# star-tracker-card.net
KiCad netlist of a schematic drawn in EAGLE
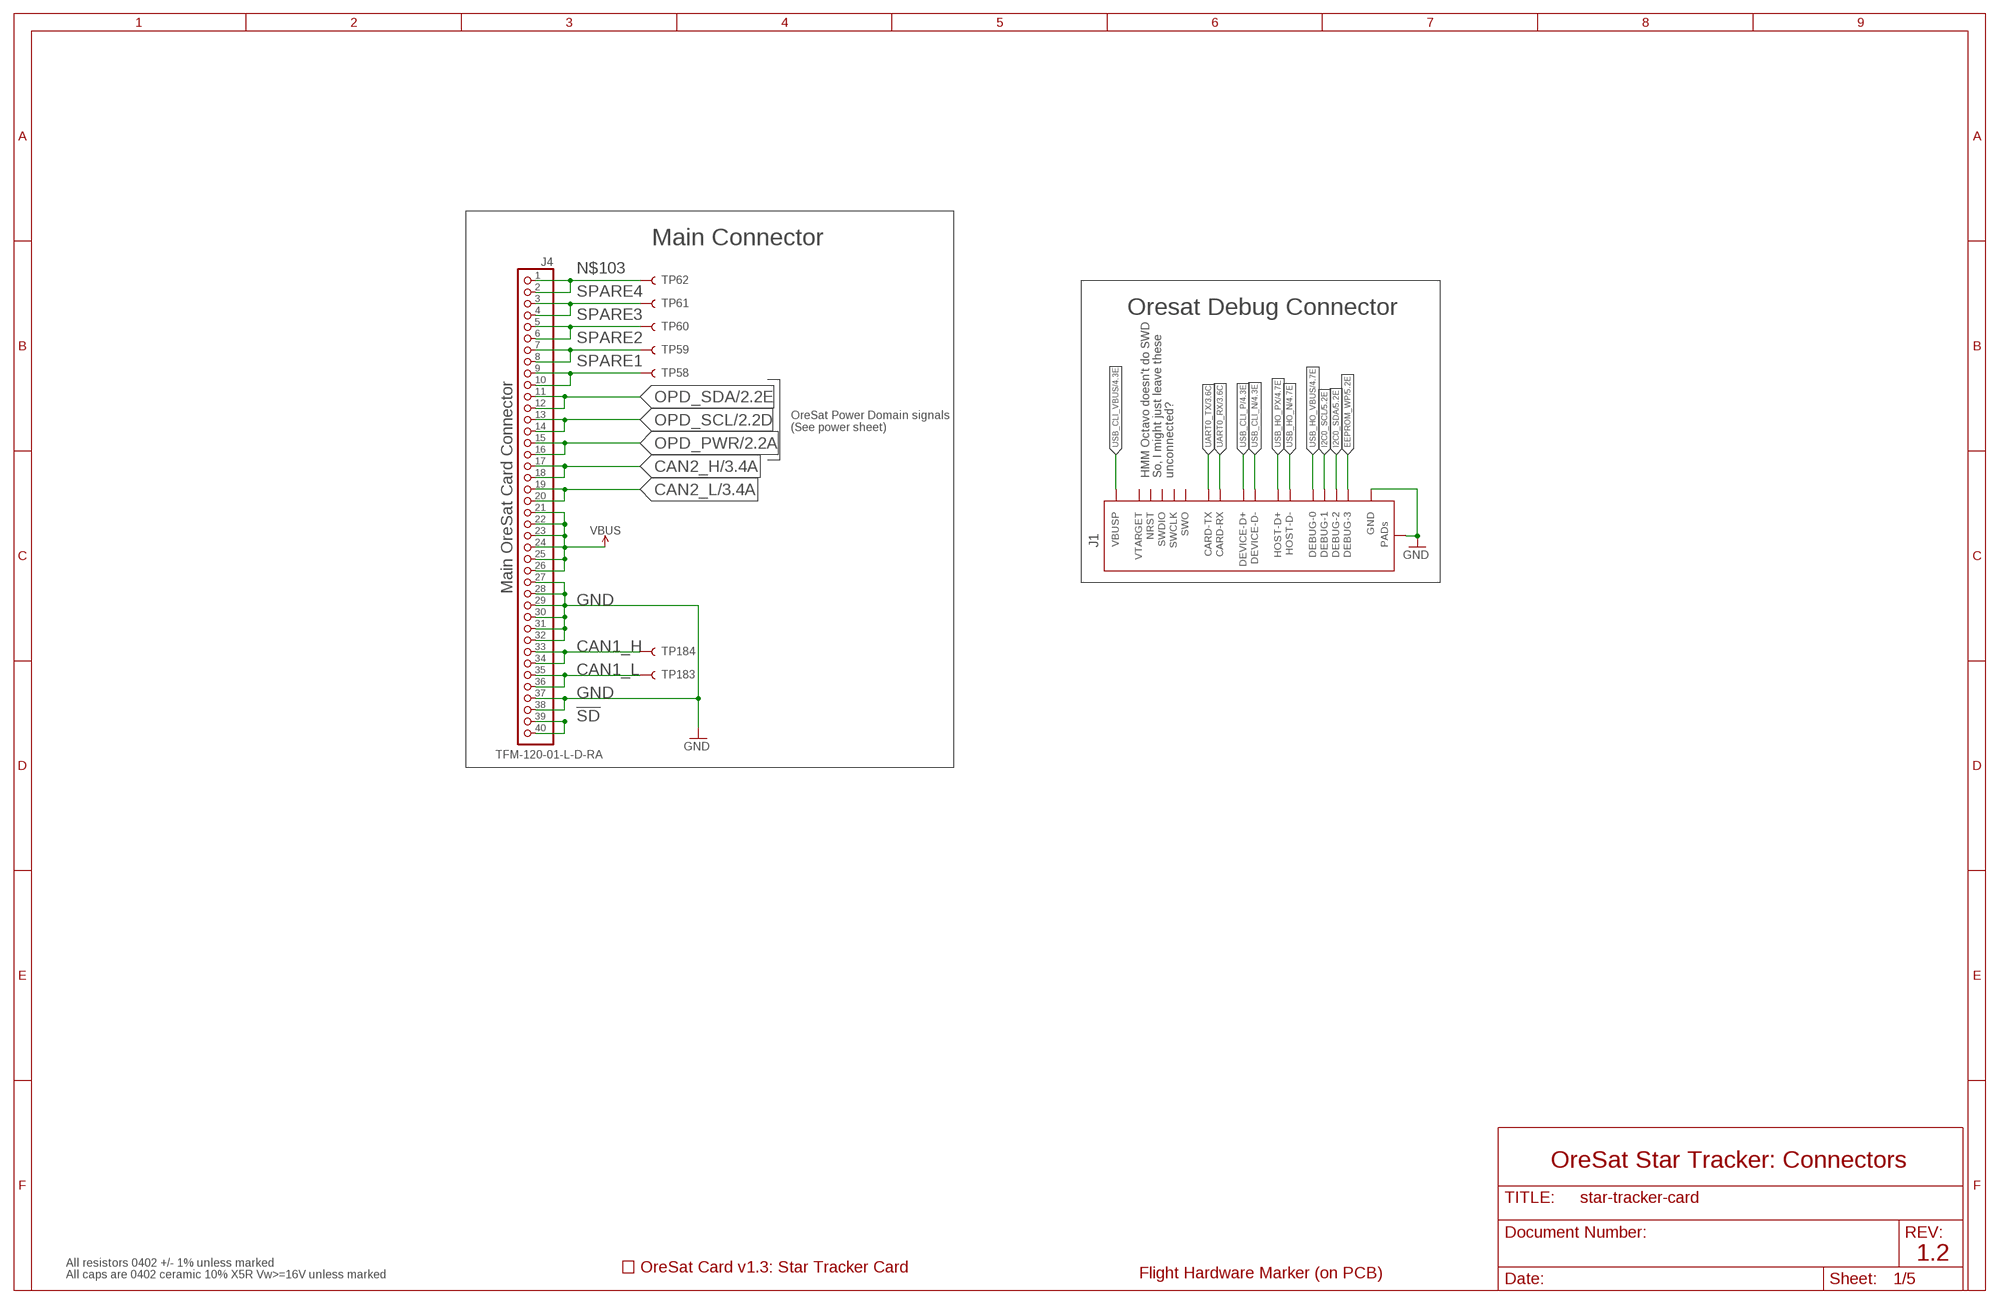
[diagram p0: schematic, sheet 1]
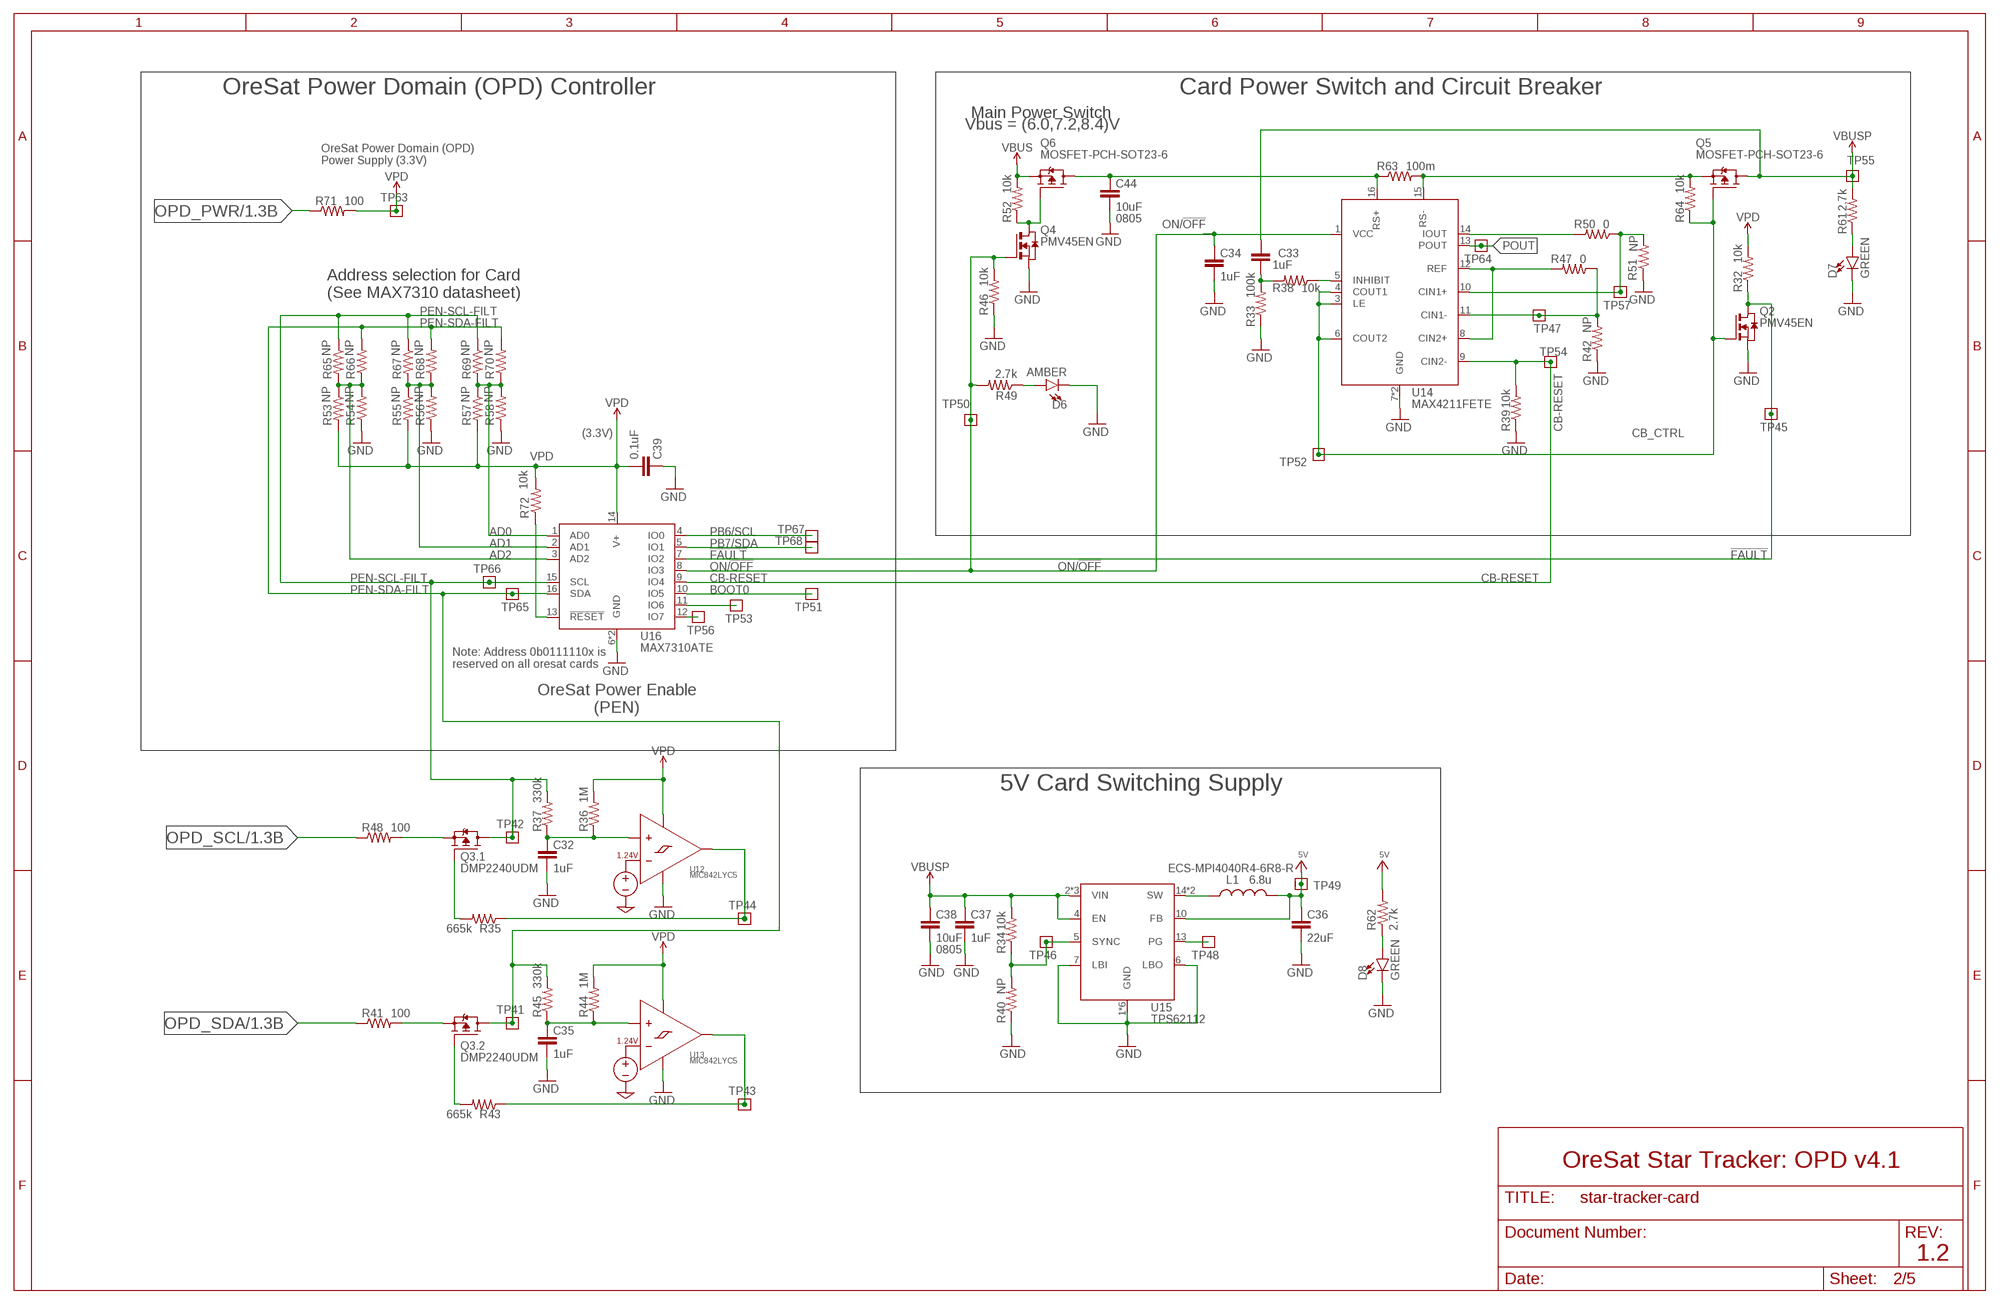
[diagram p1: schematic, sheet 2]
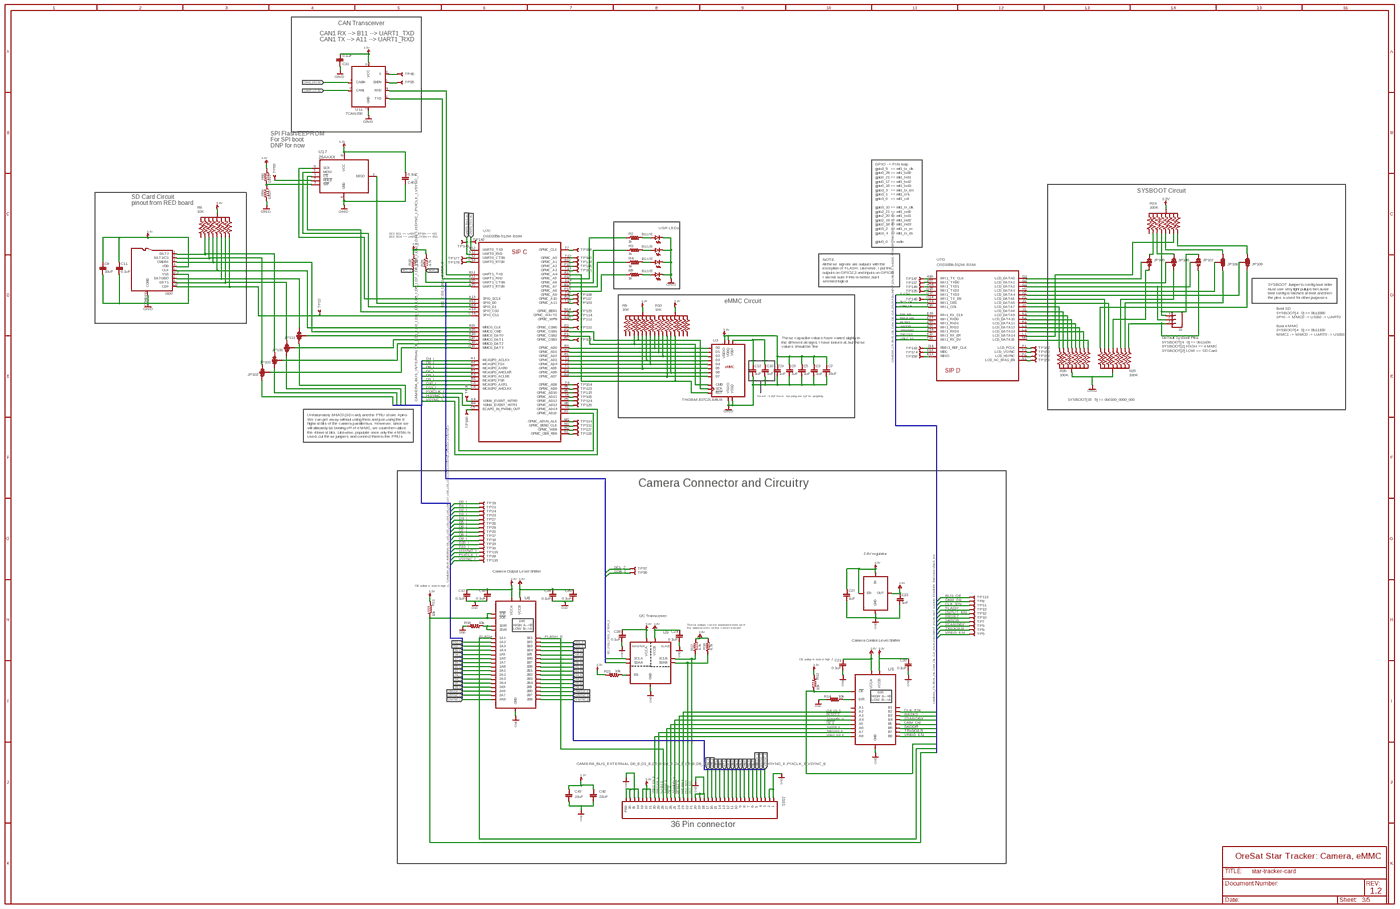
[diagram p2: schematic, sheet 3, overview]
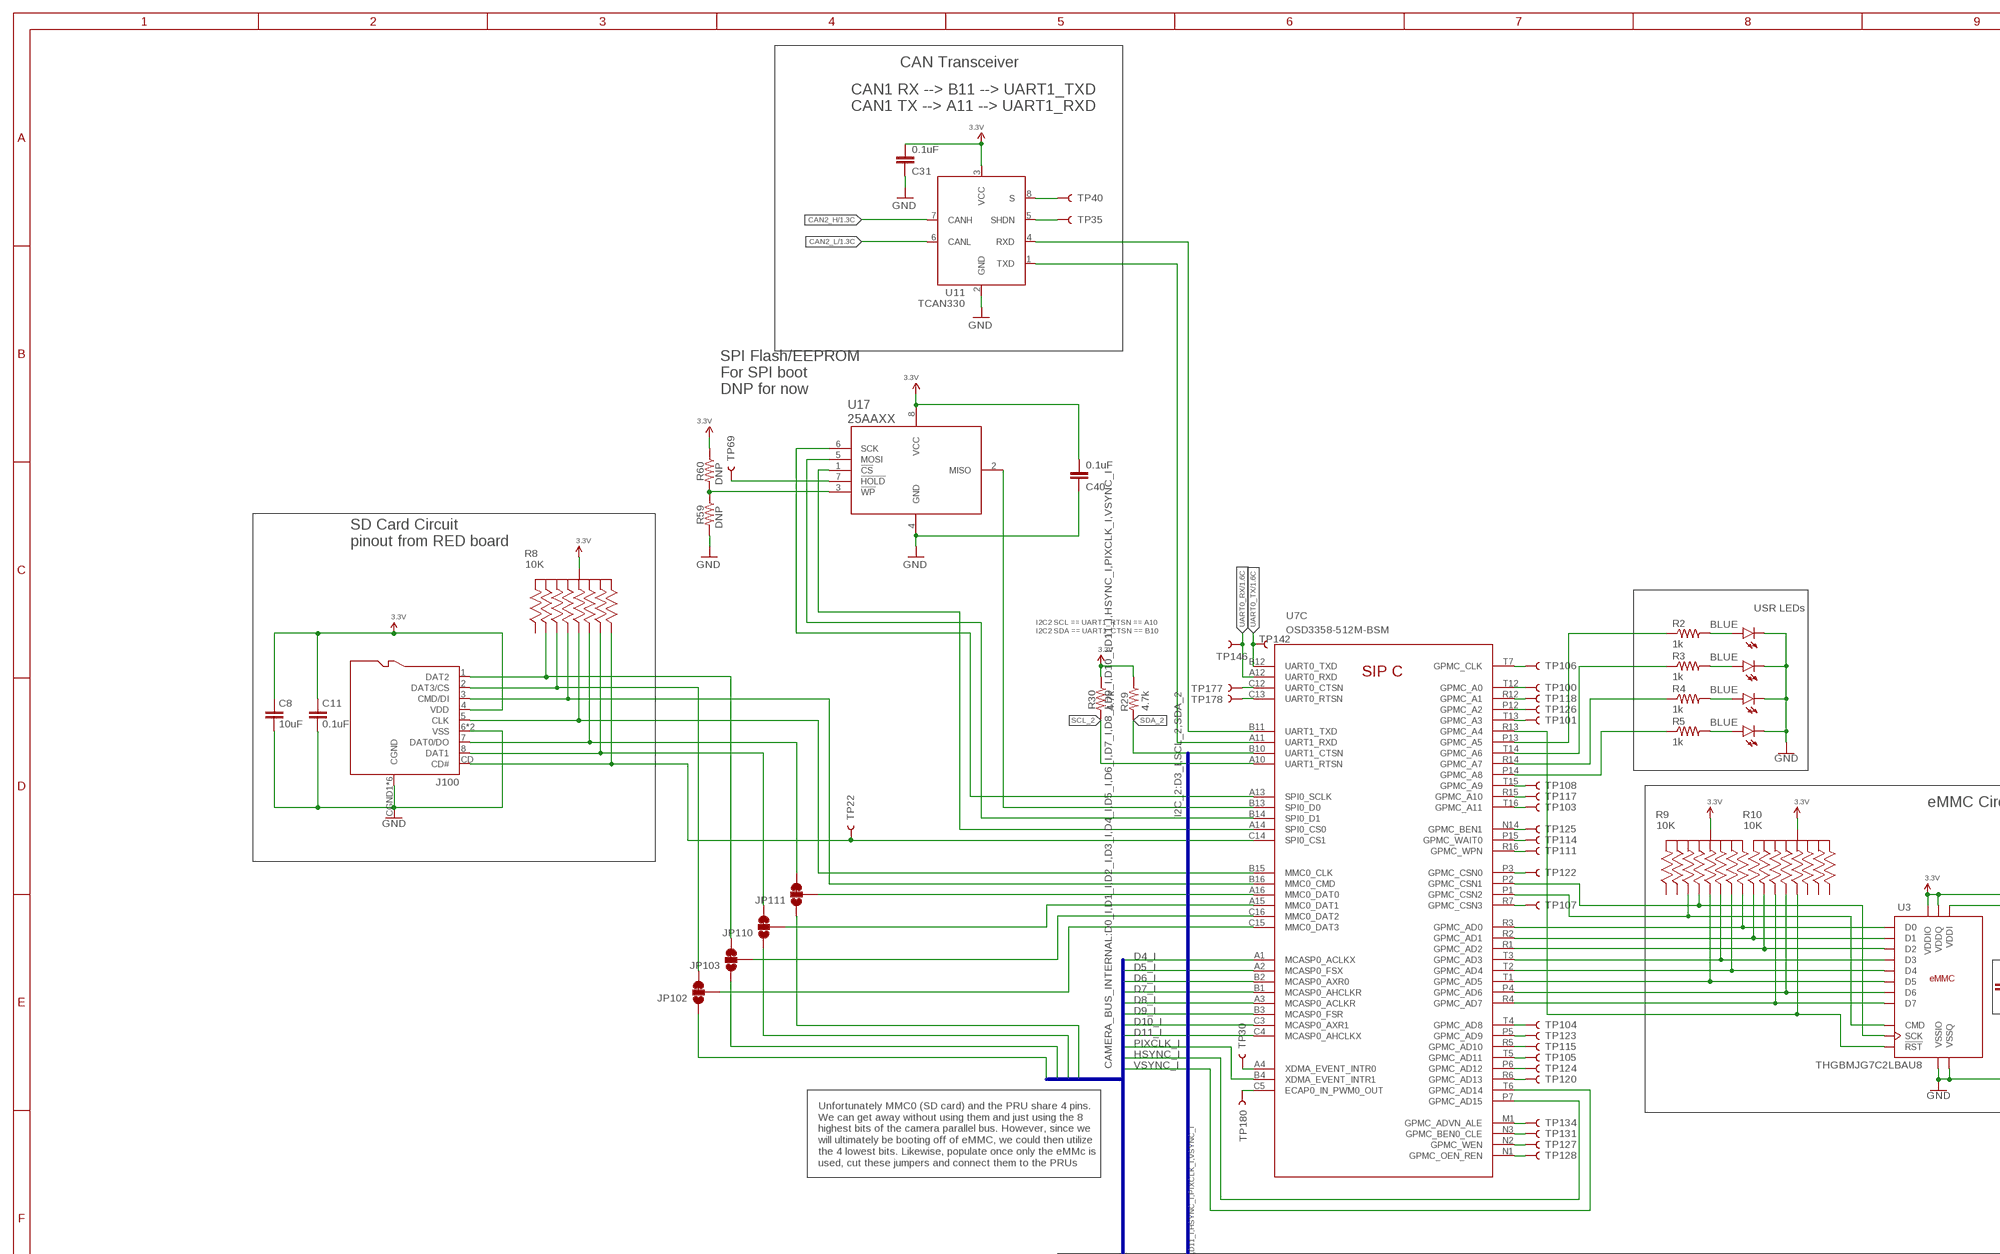
[diagram p3: schematic, sheet 3, part 1 of 4]
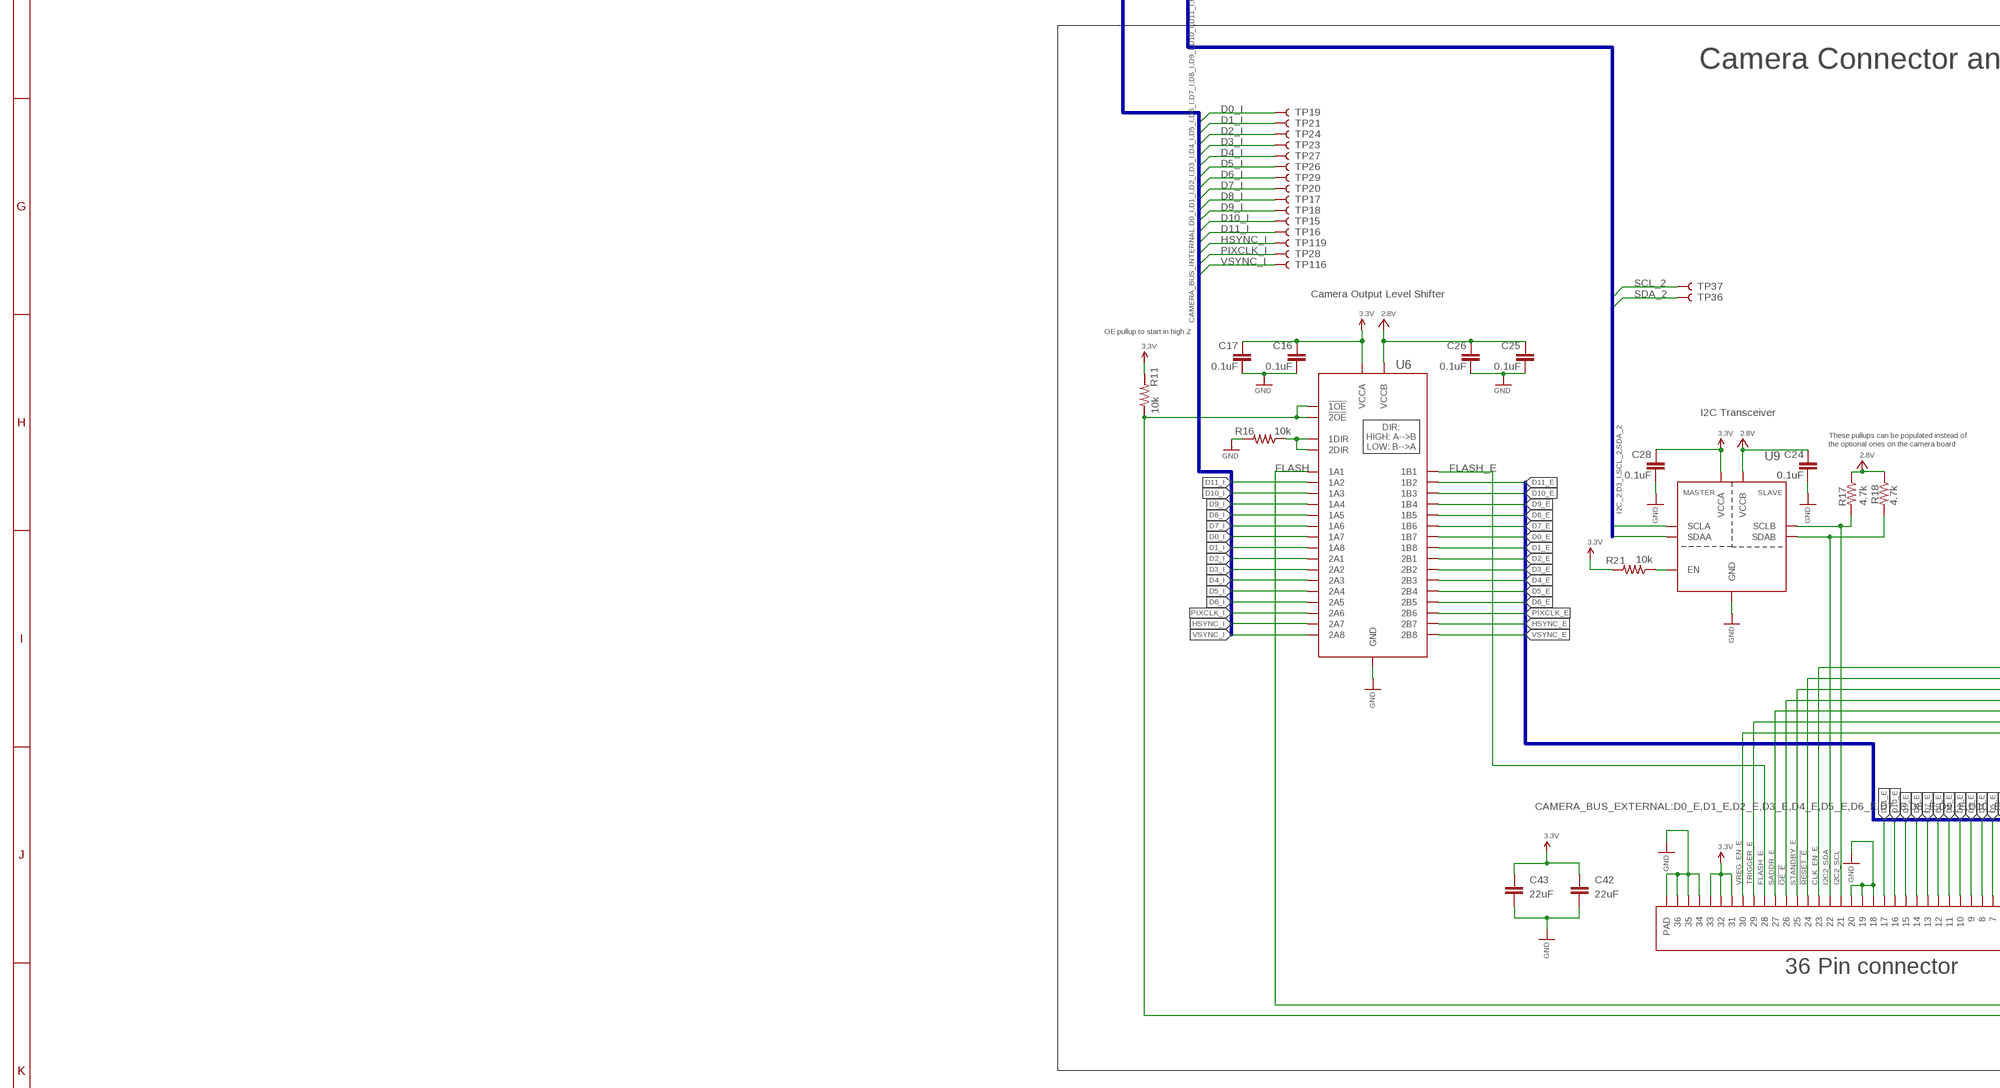
[diagram p4: schematic, sheet 3, part 2 of 4]
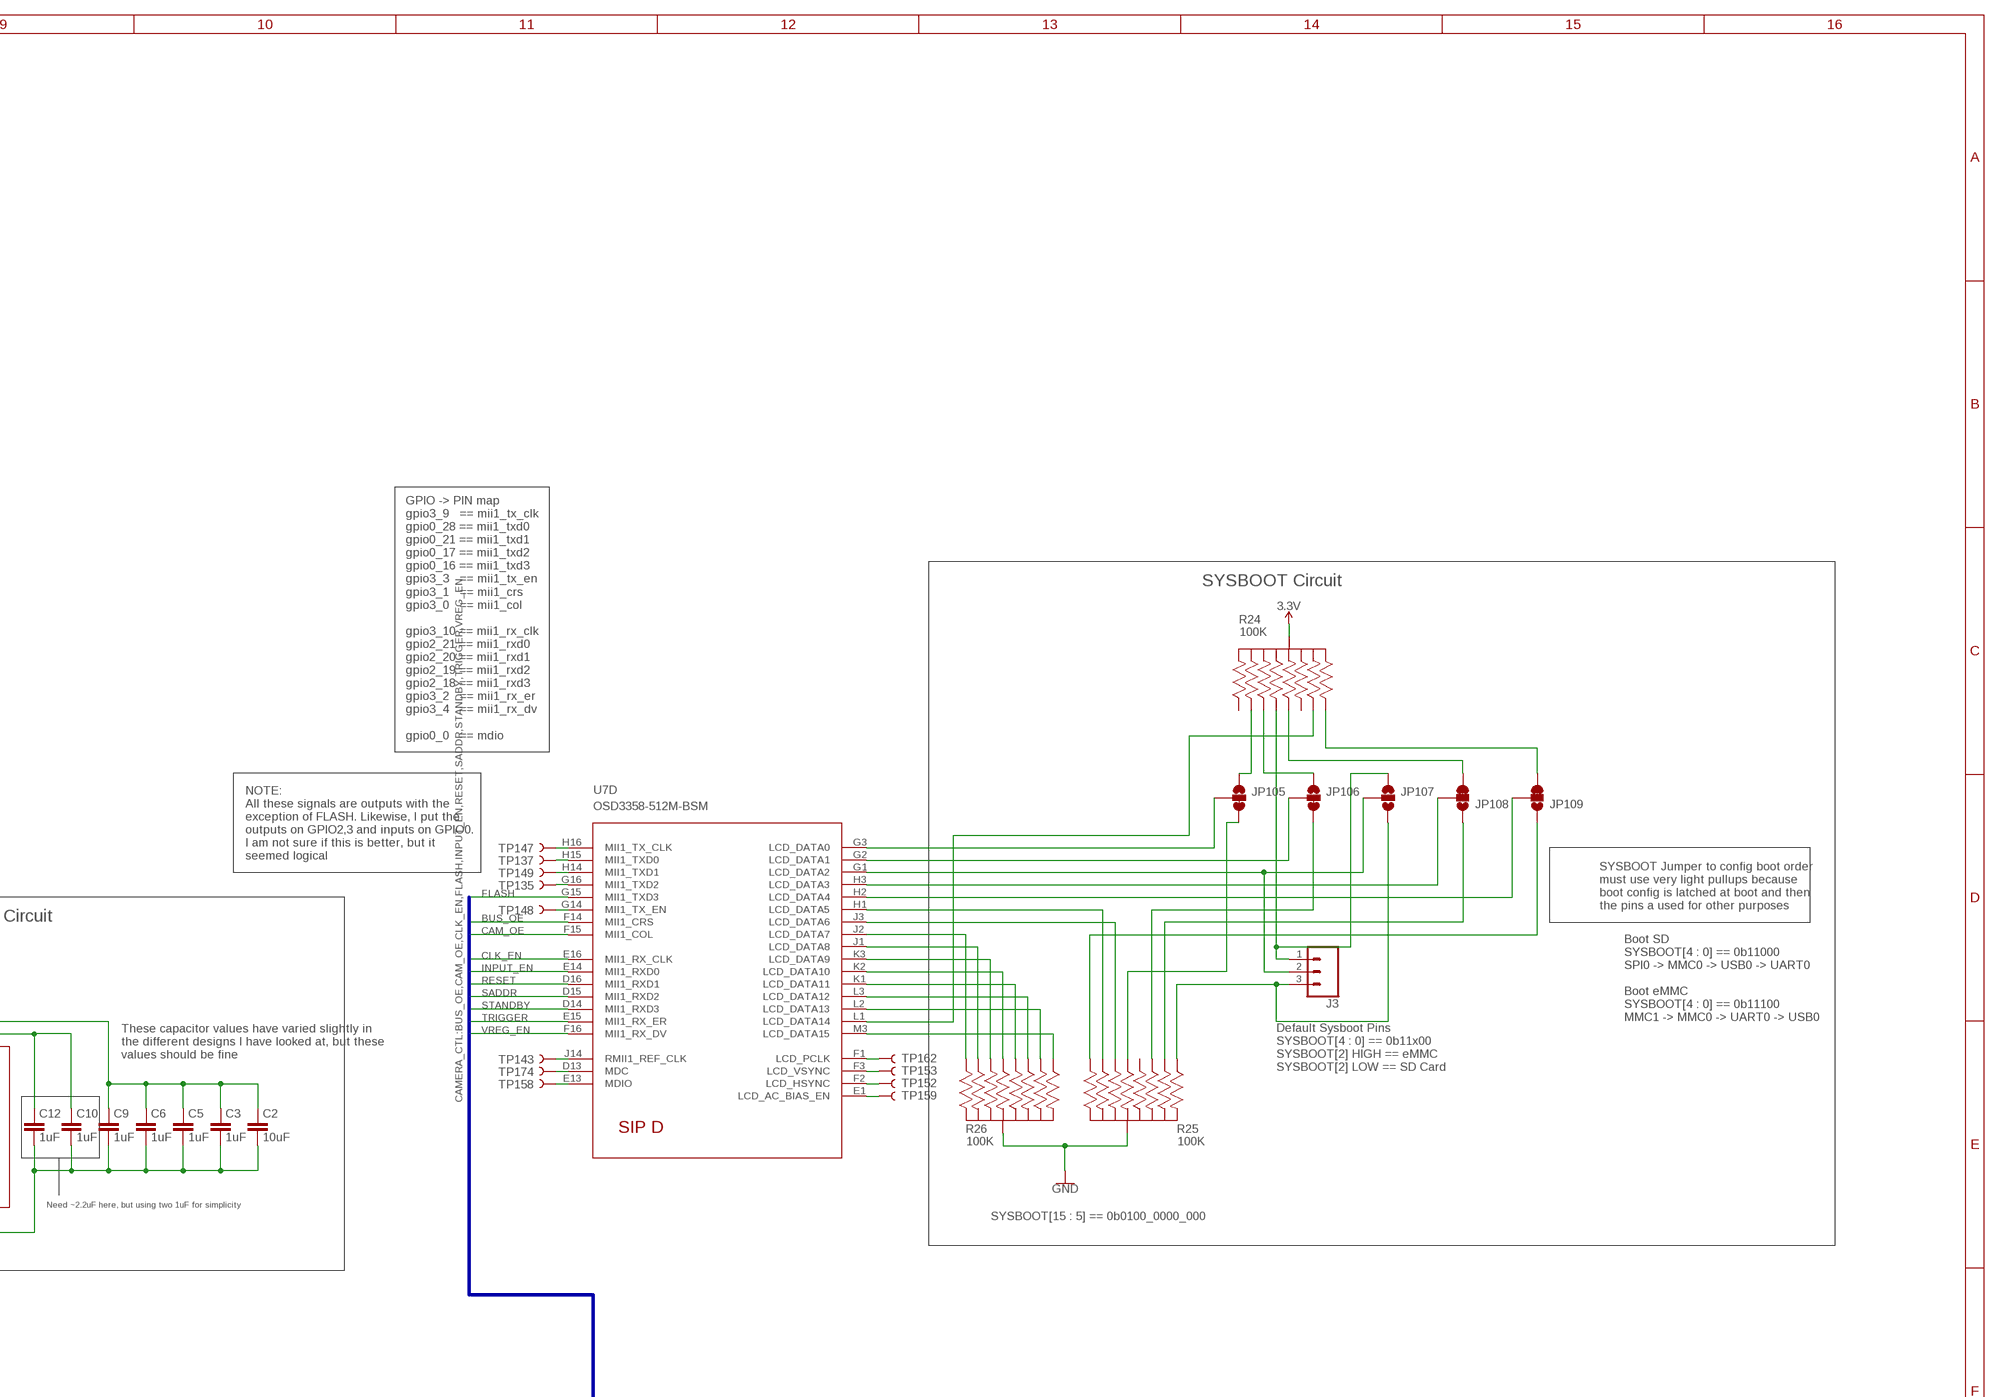
[diagram p5: schematic, sheet 3, part 3 of 4]
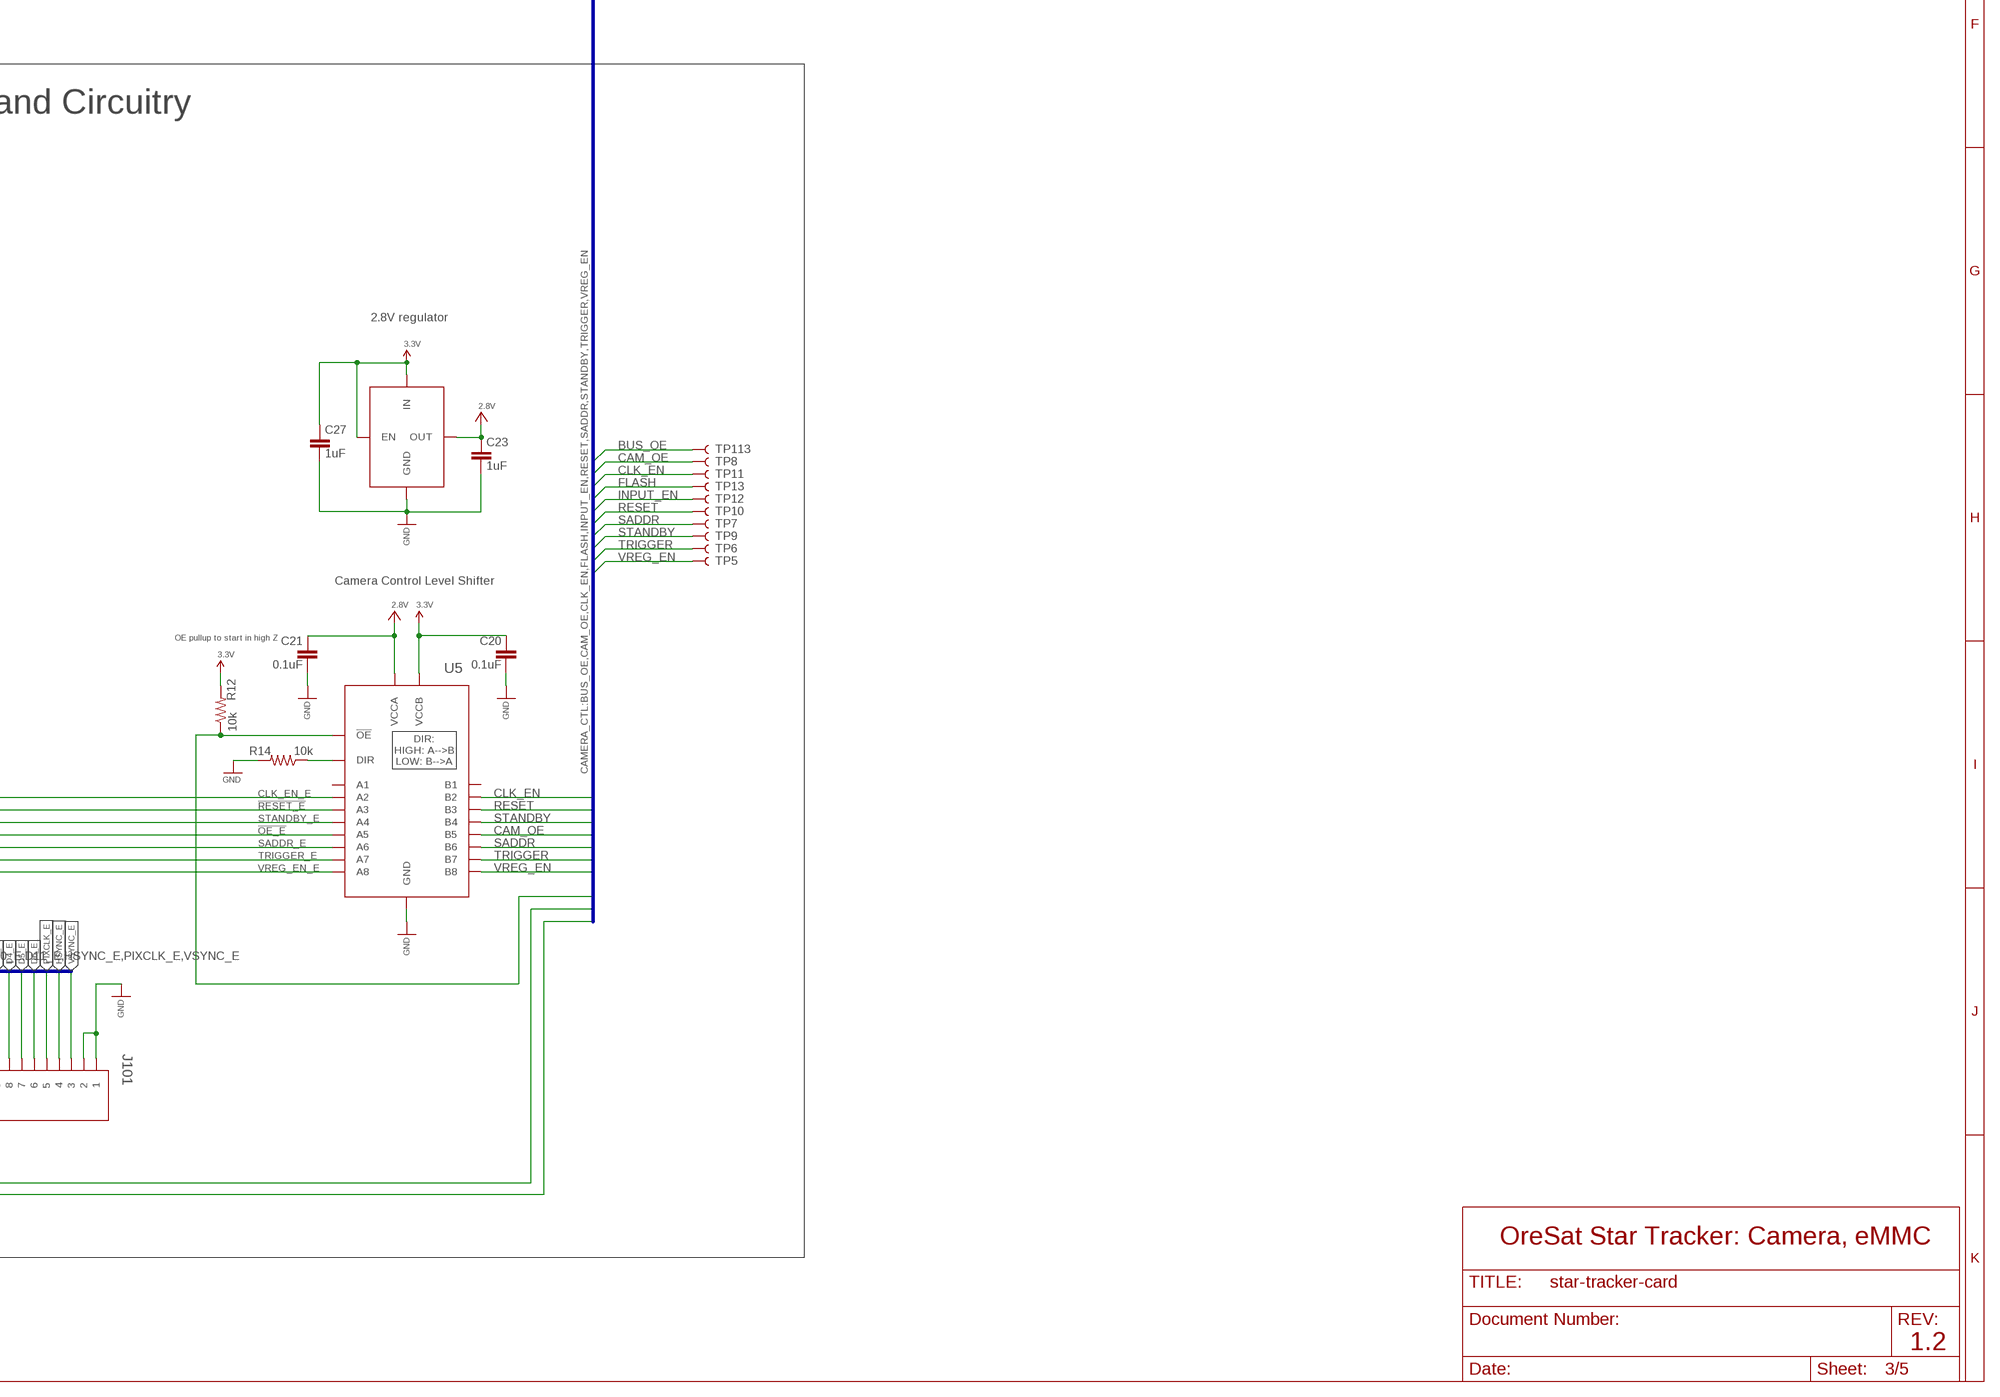
[diagram p6: schematic, sheet 3, part 4 of 4]
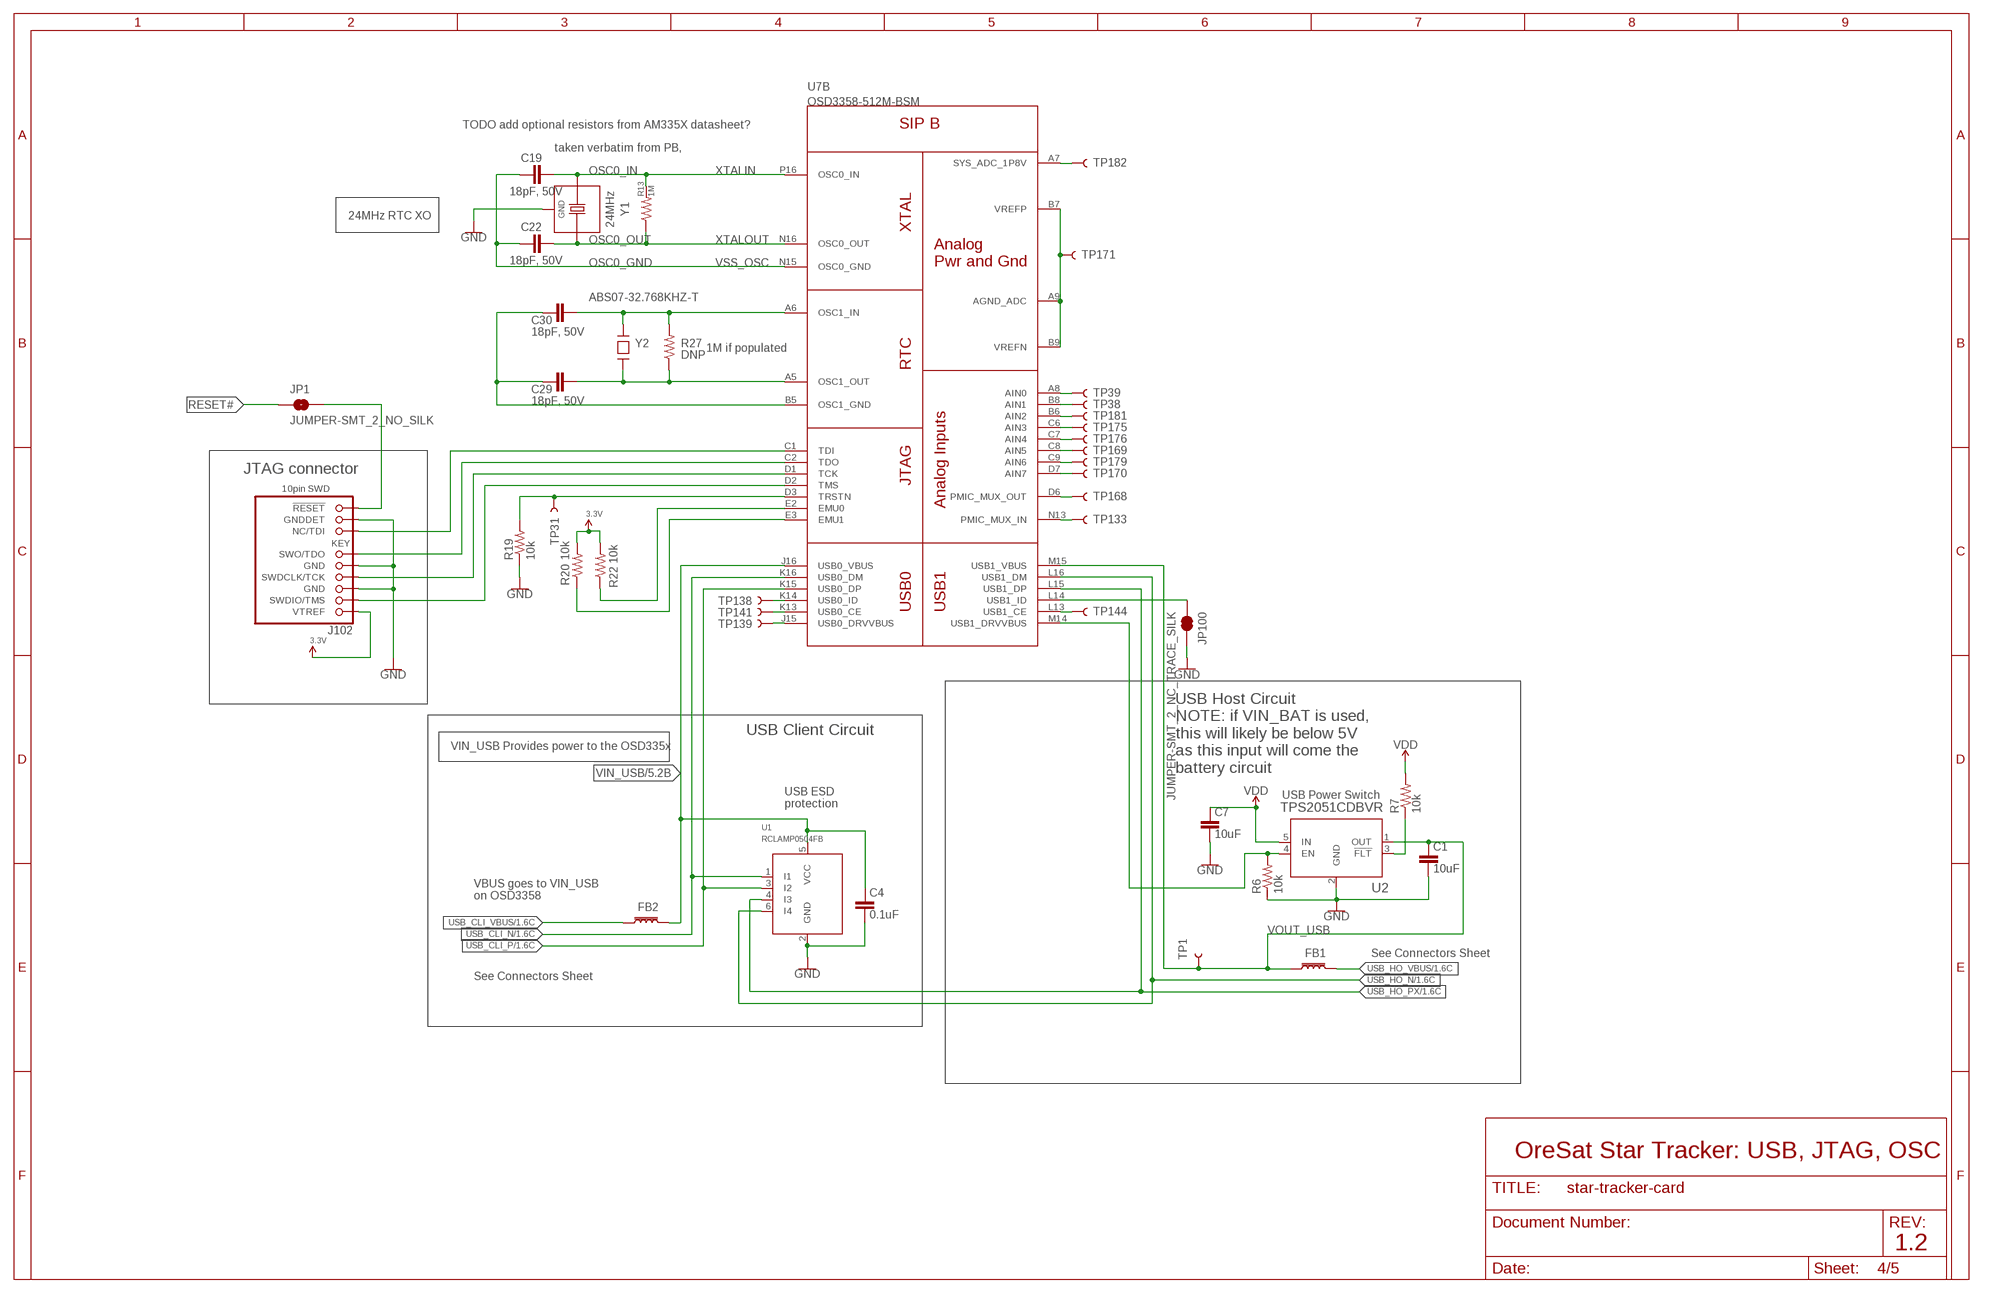
[diagram p7: schematic, sheet 4]
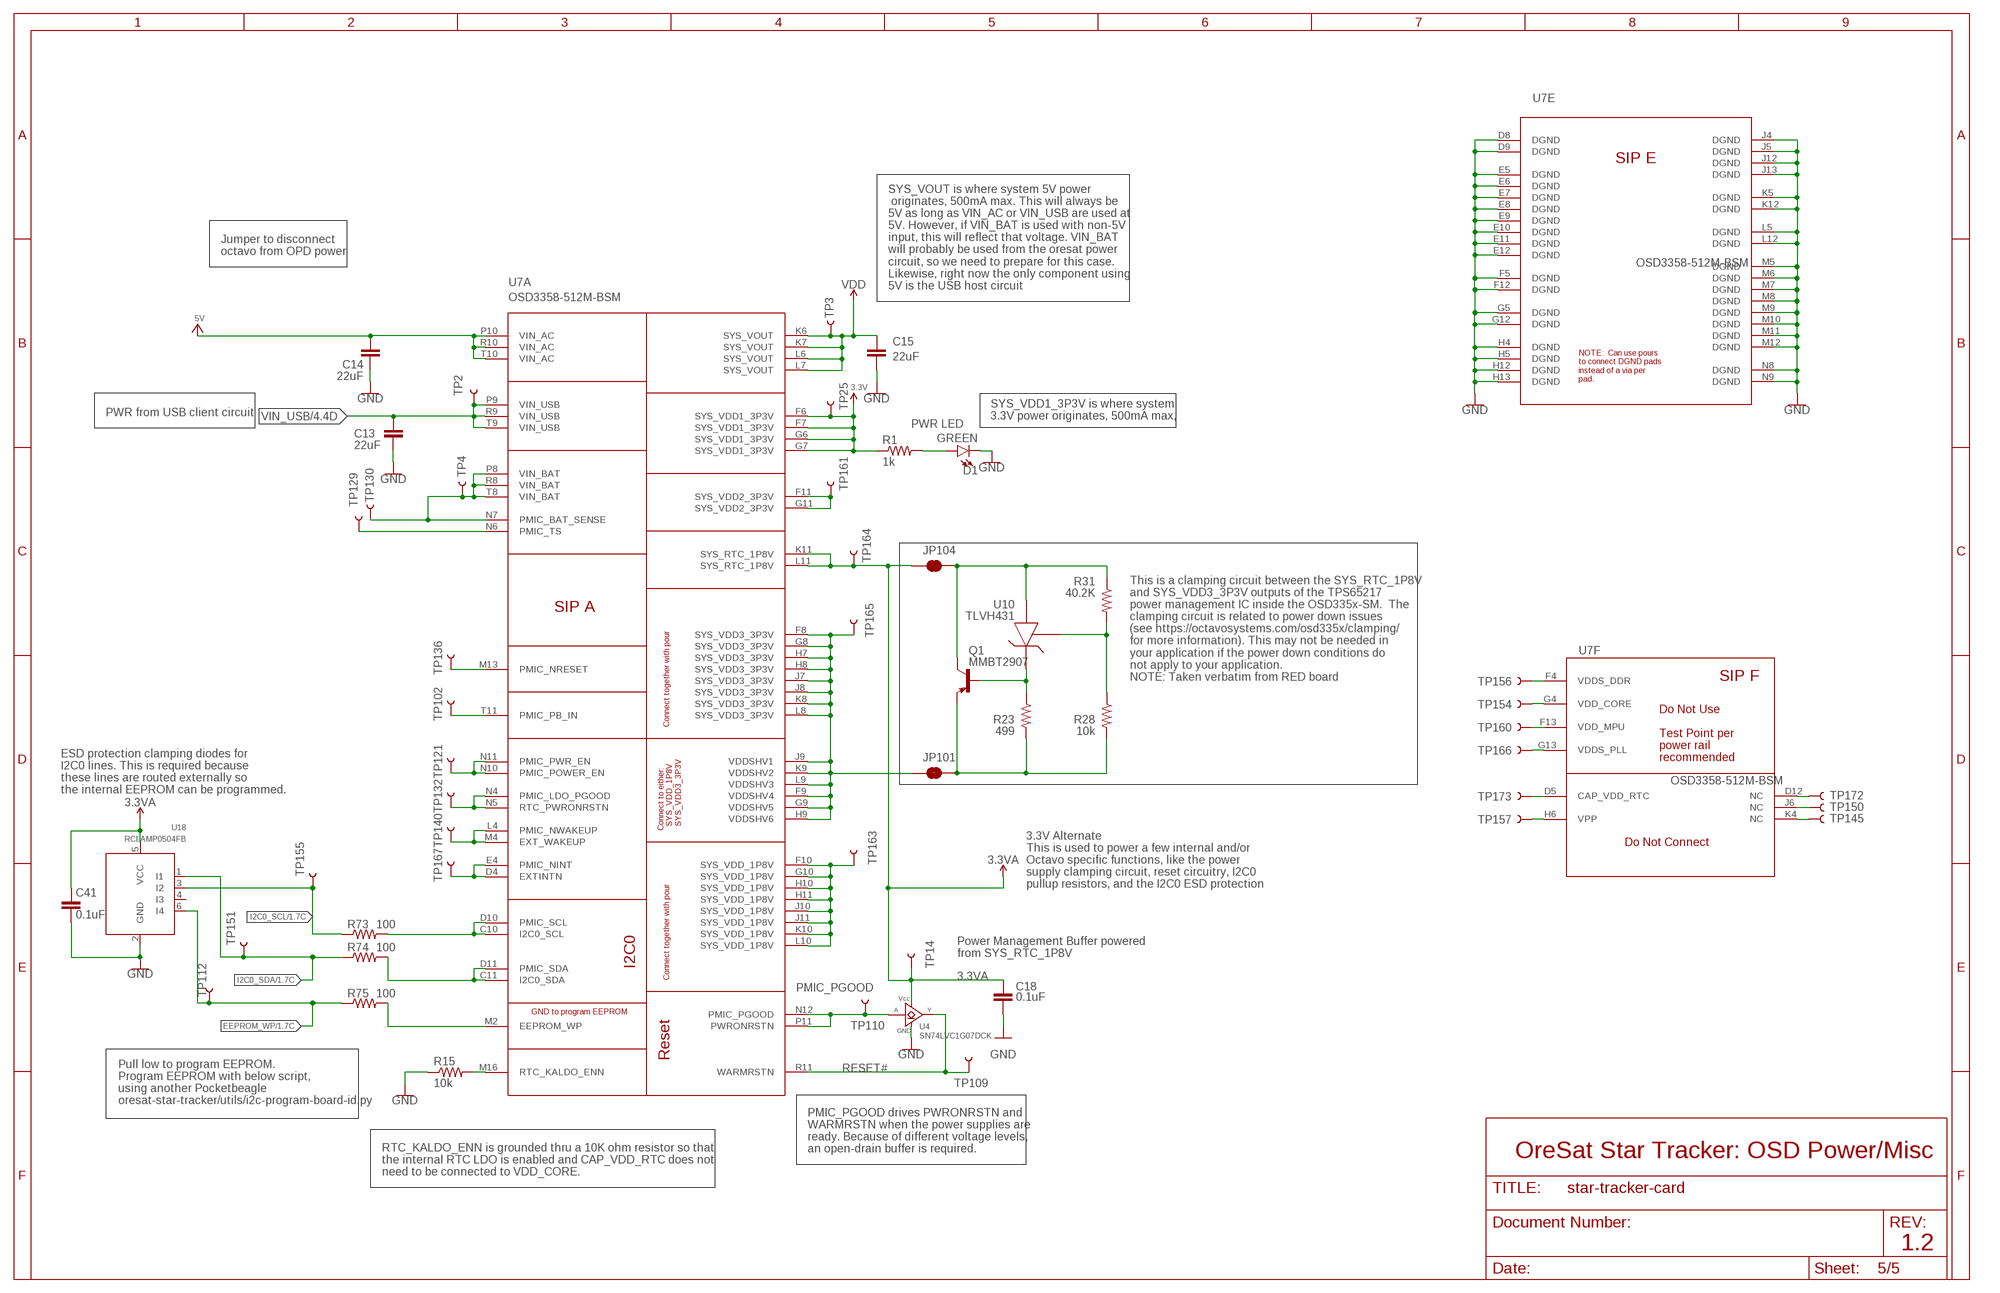
[diagram p8: schematic, sheet 5]

(export (version "E")
  (design (tool "Eeschema 10.0.6"))
  (components
    (comp (ref "C1")
      (value "10uF")
      (footprint "eagle-import:.0805-B")
      (libsource (lib "eagle-import") (part "C-EU0805-B"))
    )
    (comp (ref "C4")
      (value "0.1uF")
      (footprint "eagle-import:.0603-A")
      (libsource (lib "eagle-import") (part "C-EU0603-A"))
    )
    (comp (ref "C7")
      (value "10uF")
      (footprint "eagle-import:.0805-B")
      (libsource (lib "eagle-import") (part "C-EU0805-B"))
    )
    (comp (ref "C19")
      (value "18pF, 50V")
      (footprint "eagle-import:.0603-A")
      (libsource (lib "eagle-import") (part "C-EU0603-A"))
    )
    (comp (ref "C22")
      (value "18pF, 50V")
      (footprint "eagle-import:.0603-A")
      (libsource (lib "eagle-import") (part "C-EU0603-A"))
    )
    (comp (ref "C29")
      (value "18pF, 50V")
      (footprint "eagle-import:.0603-A")
      (libsource (lib "eagle-import") (part "C-EU0603-A"))
    )
    (comp (ref "C30")
      (value "18pF, 50V")
      (footprint "eagle-import:.0603-A")
      (libsource (lib "eagle-import") (part "C-EU0603-A"))
    )
    (comp (ref "FB1")
      (value "30Ω/1.8A")
      (footprint "eagle-import:0603")
      (fields (field (name "MPN") "BLM18KG300JH1D"))
      (libsource (lib "eagle-import") (part "FERRITE_BEAD-0603"))
    )
    (comp (ref "FB2")
      (value "30Ω/1.8A")
      (footprint "eagle-import:0603")
      (fields (field (name "MPN") "BLM18KG300JH1D"))
      (libsource (lib "eagle-import") (part "FERRITE_BEAD-0603"))
    )
    (comp (ref "J102")
      (value "FTSH-105-XX-X-DV-K")
      (footprint "eagle-import:CON10_2X5_DUK_FTSH")
      (libsource (lib "eagle-import") (part "FTSH-105-XX-X-DV-K"))
    )
    (comp (ref "JP1")
      (value "JUMPER-SMT_2_NO_SILK")
      (footprint "eagle-import:SMT-JUMPER_2_NO_SILK")
      (libsource (lib "eagle-import") (part "JUMPER-SMT_2_NO_SILK"))
    )
    (comp (ref "JP100")
      (value "JUMPER-SMT_2_NC_TRACE_SILK")
      (footprint "eagle-import:SMT-JUMPER_2_NC_TRACE_SILK")
      (libsource (lib "eagle-import") (part "JUMPER-SMT_2_NC_TRACE_SILK"))
    )
    (comp (ref "R6")
      (value "10k")
      (footprint "eagle-import:.0603-A")
      (libsource (lib "eagle-import") (part "R-US_0603-A"))
    )
    (comp (ref "R7")
      (value "10k")
      (footprint "eagle-import:.0603-A")
      (libsource (lib "eagle-import") (part "R-US_0603-A"))
    )
    (comp (ref "R13")
      (value "1M")
      (footprint "eagle-import:.0603-A")
      (libsource (lib "eagle-import") (part "R-US_0603-A"))
    )
    (comp (ref "R19")
      (value "10k")
      (footprint "eagle-import:.0603-A")
      (libsource (lib "eagle-import") (part "R-US_0603-A"))
    )
    (comp (ref "R20")
      (value "10k")
      (footprint "eagle-import:.0603-A")
      (libsource (lib "eagle-import") (part "R-US_0603-A"))
    )
    (comp (ref "R22")
      (value "10k")
      (footprint "eagle-import:.0603-A")
      (libsource (lib "eagle-import") (part "R-US_0603-A"))
    )
    (comp (ref "R27")
      (value "DNP")
      (footprint "eagle-import:.0603-A")
      (libsource (lib "eagle-import") (part "R-US_0603-A"))
    )
    (comp (ref "TP1")
      (value "TEST-POINT3X4")
      (footprint "eagle-import:PAD.03X.04")
      (libsource (lib "eagle-import") (part "TEST-POINT3X4"))
    )
    (comp (ref "TP31")
      (value "TEST-POINT3X4")
      (footprint "eagle-import:PAD.03X.04")
      (libsource (lib "eagle-import") (part "TEST-POINT3X4"))
    )
    (comp (ref "TP38")
      (value "TEST-POINT3X4")
      (footprint "eagle-import:PAD.03X.04")
      (libsource (lib "eagle-import") (part "TEST-POINT3X4"))
    )
    (comp (ref "TP39")
      (value "TEST-POINT3X4")
      (footprint "eagle-import:PAD.03X.04")
      (libsource (lib "eagle-import") (part "TEST-POINT3X4"))
    )
    (comp (ref "TP133")
      (value "TEST-POINT3X4")
      (footprint "eagle-import:PAD.03X.04")
      (libsource (lib "eagle-import") (part "TEST-POINT3X4"))
    )
    (comp (ref "TP138")
      (value "TEST-POINT3X4")
      (footprint "eagle-import:PAD.03X.04")
      (libsource (lib "eagle-import") (part "TEST-POINT3X4"))
    )
    (comp (ref "TP139")
      (value "TEST-POINT3X4")
      (footprint "eagle-import:PAD.03X.04")
      (libsource (lib "eagle-import") (part "TEST-POINT3X4"))
    )
    (comp (ref "TP141")
      (value "TEST-POINT3X4")
      (footprint "eagle-import:PAD.03X.04")
      (libsource (lib "eagle-import") (part "TEST-POINT3X4"))
    )
    (comp (ref "TP144")
      (value "TEST-POINT3X4")
      (footprint "eagle-import:PAD.03X.04")
      (libsource (lib "eagle-import") (part "TEST-POINT3X4"))
    )
    (comp (ref "TP168")
      (value "TEST-POINT3X4")
      (footprint "eagle-import:PAD.03X.04")
      (libsource (lib "eagle-import") (part "TEST-POINT3X4"))
    )
    (comp (ref "TP169")
      (value "TEST-POINT3X4")
      (footprint "eagle-import:PAD.03X.04")
      (libsource (lib "eagle-import") (part "TEST-POINT3X4"))
    )
    (comp (ref "TP170")
      (value "TEST-POINT3X4")
      (footprint "eagle-import:PAD.03X.04")
      (libsource (lib "eagle-import") (part "TEST-POINT3X4"))
    )
    (comp (ref "TP171")
      (value "TEST-POINT3X4")
      (footprint "eagle-import:PAD.03X.04")
      (libsource (lib "eagle-import") (part "TEST-POINT3X4"))
    )
    (comp (ref "TP175")
      (value "TEST-POINT3X4")
      (footprint "eagle-import:PAD.03X.04")
      (libsource (lib "eagle-import") (part "TEST-POINT3X4"))
    )
    (comp (ref "TP176")
      (value "TEST-POINT3X4")
      (footprint "eagle-import:PAD.03X.04")
      (libsource (lib "eagle-import") (part "TEST-POINT3X4"))
    )
    (comp (ref "TP179")
      (value "TEST-POINT3X4")
      (footprint "eagle-import:PAD.03X.04")
      (libsource (lib "eagle-import") (part "TEST-POINT3X4"))
    )
    (comp (ref "TP181")
      (value "TEST-POINT3X4")
      (footprint "eagle-import:PAD.03X.04")
      (libsource (lib "eagle-import") (part "TEST-POINT3X4"))
    )
    (comp (ref "TP182")
      (value "TEST-POINT3X4")
      (footprint "eagle-import:PAD.03X.04")
      (libsource (lib "eagle-import") (part "TEST-POINT3X4"))
    )
    (comp (ref "U1")
      (value "RCLAMP0504FB")
      (footprint "eagle-import:SC70-6")
      (fields (field (name "MPN") "RCLAMP0504FBTCT"))
      (libsource (lib "eagle-import") (part "RCLAMP0504FB"))
    )
    (comp (ref "U2")
      (value "TPS2051CDBVR")
      (footprint "eagle-import:DBV5")
      (fields (field (name "MFR") "Texas Instruments"))
      (libsource (lib "eagle-import") (part "TPS2051CDBVR"))
    )
    (comp (ref "U7")
      (value "OSD3358-512M-BSM")
      (footprint "eagle-import:OSD335X-BGA-256")
      (fields (field (name "MFR") "Octavo Systems"))
      (libsource (lib "eagle-import") (part "OSD3358-512M-BSM"))
    )
    (comp (ref "Y1")
      (value "24MHz")
      (footprint "eagle-import:5X3.2-4SMD")
      (fields (field (name "MPN") "ECS-240-12-30BQ-AEN-TR"))
      (libsource (lib "eagle-import") (part "ECS-240-12-30BQ-AEN-TR"))
    )
    (comp (ref "Y2")
      (value "ABS07-32.768KHZ-T")
      (footprint "eagle-import:CRYSTAL_3.2X1.5")
      (libsource (lib "eagle-import") (part "ABS07-32.768KHZ-T"))
    )
    (comp (ref "C13")
      (value "22uF")
      (footprint "eagle-import:C1210")
      (libsource (lib "eagle-import") (part "C-EUC1210"))
    )
    (comp (ref "C14")
      (value "22uF")
      (footprint "eagle-import:C1210")
      (libsource (lib "eagle-import") (part "C-EUC1210"))
    )
    (comp (ref "C15")
      (value "22uF")
      (footprint "eagle-import:C1210")
      (libsource (lib "eagle-import") (part "C-EUC1210"))
    )
    (comp (ref "C18")
      (value "0.1uF")
      (footprint "eagle-import:.0603-A")
      (libsource (lib "eagle-import") (part "C-EU0603-A"))
    )
    (comp (ref "C41")
      (value "0.1uF")
      (footprint "eagle-import:.0603-A")
      (libsource (lib "eagle-import") (part "C-EU0603-A"))
    )
    (comp (ref "D1")
      (value "GREEN")
      (footprint "eagle-import:LED-0603")
      (libsource (lib "eagle-import") (part "LED-GREEN0603"))
    )
    (comp (ref "JP101")
      (value "JUMPER-SMT_2_NC_TRACE_SILK")
      (footprint "eagle-import:SMT-JUMPER_2_NC_TRACE_SILK")
      (libsource (lib "eagle-import") (part "JUMPER-SMT_2_NC_TRACE_SILK"))
    )
    (comp (ref "JP104")
      (value "JUMPER-SMT_2_NC_TRACE_SILK")
      (footprint "eagle-import:SMT-JUMPER_2_NC_TRACE_SILK")
      (libsource (lib "eagle-import") (part "JUMPER-SMT_2_NC_TRACE_SILK"))
    )
    (comp (ref "Q1")
      (value "MMBT2907")
      (footprint "eagle-import:SOT23-BEC")
      (fields (field (name "MPN") "MMBT2907A-7-F"))
      (libsource (lib "eagle-import") (part "MMBT2907SMD"))
    )
    (comp (ref "R1")
      (value "1k")
      (footprint "eagle-import:.0603-A")
      (libsource (lib "eagle-import") (part "R-US_0603-A"))
    )
    (comp (ref "R15")
      (value "10k")
      (footprint "eagle-import:.0603-A")
      (libsource (lib "eagle-import") (part "R-US_0603-A"))
    )
    (comp (ref "R23")
      (value "499")
      (footprint "eagle-import:.0603-A")
      (libsource (lib "eagle-import") (part "R-US_0603-A"))
    )
    (comp (ref "R28")
      (value "10k")
      (footprint "eagle-import:.0603-A")
      (libsource (lib "eagle-import") (part "R-US_0603-A"))
    )
    (comp (ref "R31")
      (value "40.2K")
      (footprint "eagle-import:.0603-A")
      (libsource (lib "eagle-import") (part "R-US_0603-A"))
    )
    (comp (ref "R73")
      (value "100")
      (footprint "eagle-import:.0603-A")
      (libsource (lib "eagle-import") (part "R-US_0603-A"))
    )
    (comp (ref "R74")
      (value "100")
      (footprint "eagle-import:.0603-A")
      (libsource (lib "eagle-import") (part "R-US_0603-A"))
    )
    (comp (ref "R75")
      (value "100")
      (footprint "eagle-import:.0603-A")
      (libsource (lib "eagle-import") (part "R-US_0603-A"))
    )
    (comp (ref "TP2")
      (value "TEST-POINT3X4")
      (footprint "eagle-import:PAD.03X.04")
      (libsource (lib "eagle-import") (part "TEST-POINT3X4"))
    )
    (comp (ref "TP3")
      (value "TEST-POINT3X4")
      (footprint "eagle-import:PAD.03X.04")
      (libsource (lib "eagle-import") (part "TEST-POINT3X4"))
    )
    (comp (ref "TP4")
      (value "TEST-POINT3X4")
      (footprint "eagle-import:PAD.03X.04")
      (libsource (lib "eagle-import") (part "TEST-POINT3X4"))
    )
    (comp (ref "TP14")
      (value "TEST-POINT3X4")
      (footprint "eagle-import:PAD.03X.04")
      (libsource (lib "eagle-import") (part "TEST-POINT3X4"))
    )
    (comp (ref "TP25")
      (value "TEST-POINT3X4")
      (footprint "eagle-import:PAD.03X.04")
      (libsource (lib "eagle-import") (part "TEST-POINT3X4"))
    )
    (comp (ref "TP102")
      (value "TEST-POINT3X4")
      (footprint "eagle-import:PAD.03X.04")
      (libsource (lib "eagle-import") (part "TEST-POINT3X4"))
    )
    (comp (ref "TP109")
      (value "TEST-POINT3X4")
      (footprint "eagle-import:PAD.03X.04")
      (libsource (lib "eagle-import") (part "TEST-POINT3X4"))
    )
    (comp (ref "TP110")
      (value "TEST-POINT3X4")
      (footprint "eagle-import:PAD.03X.04")
      (libsource (lib "eagle-import") (part "TEST-POINT3X4"))
    )
    (comp (ref "TP112")
      (value "TEST-POINT3X4")
      (footprint "eagle-import:PAD.03X.04")
      (libsource (lib "eagle-import") (part "TEST-POINT3X4"))
    )
    (comp (ref "TP121")
      (value "TEST-POINT3X4")
      (footprint "eagle-import:PAD.03X.04")
      (libsource (lib "eagle-import") (part "TEST-POINT3X4"))
    )
    (comp (ref "TP129")
      (value "TEST-POINT3X4")
      (footprint "eagle-import:PAD.03X.04")
      (libsource (lib "eagle-import") (part "TEST-POINT3X4"))
    )
    (comp (ref "TP130")
      (value "TEST-POINT3X4")
      (footprint "eagle-import:PAD.03X.04")
      (libsource (lib "eagle-import") (part "TEST-POINT3X4"))
    )
    (comp (ref "TP132")
      (value "TEST-POINT3X4")
      (footprint "eagle-import:PAD.03X.04")
      (libsource (lib "eagle-import") (part "TEST-POINT3X4"))
    )
    (comp (ref "TP136")
      (value "TEST-POINT3X4")
      (footprint "eagle-import:PAD.03X.04")
      (libsource (lib "eagle-import") (part "TEST-POINT3X4"))
    )
    (comp (ref "TP140")
      (value "TEST-POINT3X4")
      (footprint "eagle-import:PAD.03X.04")
      (libsource (lib "eagle-import") (part "TEST-POINT3X4"))
    )
    (comp (ref "TP145")
      (value "TEST-POINT3X4")
      (footprint "eagle-import:PAD.03X.04")
      (libsource (lib "eagle-import") (part "TEST-POINT3X4"))
    )
    (comp (ref "TP150")
      (value "TEST-POINT3X4")
      (footprint "eagle-import:PAD.03X.04")
      (libsource (lib "eagle-import") (part "TEST-POINT3X4"))
    )
    (comp (ref "TP151")
      (value "TEST-POINT3X4")
      (footprint "eagle-import:PAD.03X.04")
      (libsource (lib "eagle-import") (part "TEST-POINT3X4"))
    )
    (comp (ref "TP154")
      (value "TEST-POINT3X4")
      (footprint "eagle-import:PAD.03X.04")
      (libsource (lib "eagle-import") (part "TEST-POINT3X4"))
    )
    (comp (ref "TP155")
      (value "TEST-POINT3X4")
      (footprint "eagle-import:PAD.03X.04")
      (libsource (lib "eagle-import") (part "TEST-POINT3X4"))
    )
    (comp (ref "TP156")
      (value "TEST-POINT3X4")
      (footprint "eagle-import:PAD.03X.04")
      (libsource (lib "eagle-import") (part "TEST-POINT3X4"))
    )
    (comp (ref "TP157")
      (value "TEST-POINT3X4")
      (footprint "eagle-import:PAD.03X.04")
      (libsource (lib "eagle-import") (part "TEST-POINT3X4"))
    )
    (comp (ref "TP160")
      (value "TEST-POINT3X4")
      (footprint "eagle-import:PAD.03X.04")
      (libsource (lib "eagle-import") (part "TEST-POINT3X4"))
    )
    (comp (ref "TP161")
      (value "TEST-POINT3X4")
      (footprint "eagle-import:PAD.03X.04")
      (libsource (lib "eagle-import") (part "TEST-POINT3X4"))
    )
    (comp (ref "TP163")
      (value "TEST-POINT3X4")
      (footprint "eagle-import:PAD.03X.04")
      (libsource (lib "eagle-import") (part "TEST-POINT3X4"))
    )
    (comp (ref "TP164")
      (value "TEST-POINT3X4")
      (footprint "eagle-import:PAD.03X.04")
      (libsource (lib "eagle-import") (part "TEST-POINT3X4"))
    )
    (comp (ref "TP165")
      (value "TEST-POINT3X4")
      (footprint "eagle-import:PAD.03X.04")
      (libsource (lib "eagle-import") (part "TEST-POINT3X4"))
    )
    (comp (ref "TP166")
      (value "TEST-POINT3X4")
      (footprint "eagle-import:PAD.03X.04")
      (libsource (lib "eagle-import") (part "TEST-POINT3X4"))
    )
    (comp (ref "TP167")
      (value "TEST-POINT3X4")
      (footprint "eagle-import:PAD.03X.04")
      (libsource (lib "eagle-import") (part "TEST-POINT3X4"))
    )
    (comp (ref "TP172")
      (value "TEST-POINT3X4")
      (footprint "eagle-import:PAD.03X.04")
      (libsource (lib "eagle-import") (part "TEST-POINT3X4"))
    )
    (comp (ref "TP173")
      (value "TEST-POINT3X4")
      (footprint "eagle-import:PAD.03X.04")
      (libsource (lib "eagle-import") (part "TEST-POINT3X4"))
    )
    (comp (ref "U4")
      (value "SN74LVC1G07DCK")
      (footprint "eagle-import:C70(TI-DCK)")
      (fields (field (name "MPN") "SN74LVC1G07DCKR"))
      (libsource (lib "eagle-import") (part "SN74LVC1G07DCK"))
    )
    (comp (ref "U10")
      (value "TLVH431")
      (footprint "eagle-import:SOT23-3")
      (fields (field (name "MPN") "TLVH431BQDBZRQ1"))
      (libsource (lib "eagle-import") (part "TLVH431"))
    )
    (comp (ref "U18")
      (value "RCLAMP0504FB")
      (footprint "eagle-import:SC70-6")
      (fields (field (name "MPN") "RCLAMP0504FBTCT"))
      (libsource (lib "eagle-import") (part "RCLAMP0504FB"))
    )
    (comp (ref "C2")
      (value "10uF")
      (footprint "eagle-import:.0805-B")
      (libsource (lib "eagle-import") (part "C-EU0805-B"))
    )
    (comp (ref "C3")
      (value "1uF")
      (footprint "eagle-import:.0603-A")
      (libsource (lib "eagle-import") (part "C-EU0603-A"))
    )
    (comp (ref "C5")
      (value "1uF")
      (footprint "eagle-import:.0603-A")
      (libsource (lib "eagle-import") (part "C-EU0603-A"))
    )
    (comp (ref "C6")
      (value "1uF")
      (footprint "eagle-import:.0603-A")
      (libsource (lib "eagle-import") (part "C-EU0603-A"))
    )
    (comp (ref "C8")
      (value "10uF")
      (footprint "eagle-import:.0805-B")
      (libsource (lib "eagle-import") (part "C-EU0805-B"))
    )
    (comp (ref "C9")
      (value "1uF")
      (footprint "eagle-import:.0603-A")
      (libsource (lib "eagle-import") (part "C-EU0603-A"))
    )
    (comp (ref "C10")
      (value "1uF")
      (footprint "eagle-import:.0603-A")
      (libsource (lib "eagle-import") (part "C-EU0603-A"))
    )
    (comp (ref "C11")
      (value "0.1uF")
      (footprint "eagle-import:.0603-A")
      (libsource (lib "eagle-import") (part "C-EU0603-A"))
    )
    (comp (ref "C12")
      (value "1uF")
      (footprint "eagle-import:.0603-A")
      (libsource (lib "eagle-import") (part "C-EU0603-A"))
    )
    (comp (ref "C16")
      (value "0.1uF")
      (footprint "eagle-import:.0603-A")
      (libsource (lib "eagle-import") (part "C-EU0603-A"))
    )
    (comp (ref "C17")
      (value "0.1uF")
      (footprint "eagle-import:.0603-A")
      (libsource (lib "eagle-import") (part "C-EU0603-A"))
    )
    (comp (ref "C20")
      (value "0.1uF")
      (footprint "eagle-import:.0603-A")
      (libsource (lib "eagle-import") (part "C-EU0603-A"))
    )
    (comp (ref "C21")
      (value "0.1uF")
      (footprint "eagle-import:.0603-A")
      (libsource (lib "eagle-import") (part "C-EU0603-A"))
    )
    (comp (ref "C23")
      (value "1uF")
      (footprint "eagle-import:.0603-A")
      (libsource (lib "eagle-import") (part "C-EU0603-A"))
    )
    (comp (ref "C24")
      (value "0.1uF")
      (footprint "eagle-import:.0603-A")
      (libsource (lib "eagle-import") (part "C-EU0603-A"))
    )
    (comp (ref "C25")
      (value "0.1uF")
      (footprint "eagle-import:.0603-A")
      (libsource (lib "eagle-import") (part "C-EU0603-A"))
    )
    (comp (ref "C26")
      (value "0.1uF")
      (footprint "eagle-import:.0603-A")
      (libsource (lib "eagle-import") (part "C-EU0603-A"))
    )
    (comp (ref "C27")
      (value "1uF")
      (footprint "eagle-import:.0603-A")
      (libsource (lib "eagle-import") (part "C-EU0603-A"))
    )
    (comp (ref "C28")
      (value "0.1uF")
      (footprint "eagle-import:.0603-A")
      (libsource (lib "eagle-import") (part "C-EU0603-A"))
    )
    (comp (ref "C31")
      (value "0.1uF")
      (footprint "eagle-import:.0603-A")
      (libsource (lib "eagle-import") (part "C-EU0603-A"))
    )
    (comp (ref "C40")
      (value "0.1uF")
      (footprint "eagle-import:.0603-A")
      (libsource (lib "eagle-import") (part "C-EU0603-A"))
    )
    (comp (ref "C42")
      (value "22uF")
      (footprint "eagle-import:C1210")
      (libsource (lib "eagle-import") (part "C-EUC1210"))
    )
    (comp (ref "C43")
      (value "22uF")
      (footprint "eagle-import:C1210")
      (libsource (lib "eagle-import") (part "C-EUC1210"))
    )
    (comp (ref "D2")
      (value "BLUE")
      (footprint "eagle-import:LED-0603")
      (libsource (lib "eagle-import") (part "LED-BLUE0603"))
    )
    (comp (ref "D3")
      (value "BLUE")
      (footprint "eagle-import:LED-0603")
      (libsource (lib "eagle-import") (part "LED-BLUE0603"))
    )
    (comp (ref "D4")
      (value "BLUE")
      (footprint "eagle-import:LED-0603")
      (libsource (lib "eagle-import") (part "LED-BLUE0603"))
    )
    (comp (ref "D5")
      (value "BLUE")
      (footprint "eagle-import:LED-0603")
      (libsource (lib "eagle-import") (part "LED-BLUE0603"))
    )
    (comp (ref "J3")
      (value "CONN_03LONGPADS")
      (footprint "eagle-import:1X03_LONGPADS")
      (libsource (lib "eagle-import") (part "CONN_03LONGPADS"))
    )
    (comp (ref "J100")
      (value "DM3BT-DSF-PEJS")
      (footprint "eagle-import:DM3BT-DSF-PEJS")
      (libsource (lib "eagle-import") (part "DM3BT-DSF-PEJS"))
    )
    (comp (ref "J101")
      (value "3-1734592-64-1734592-0")
      (footprint "eagle-import:TE_3-1734592-6")
      (fields (field (name "MPN") "3-1734592-6"))
      (libsource (lib "eagle-import") (part "3-1734592-64-1734592-0"))
    )
    (comp (ref "JP102")
      (value "JUMPER-SMT_3_1-NC_TRACE_SILK")
      (footprint "eagle-import:SMT-JUMPER_3_1-NC_TRACE_SILK")
      (libsource (lib "eagle-import") (part "JUMPER-SMT_3_1-NC_TRACE_SILK"))
    )
    (comp (ref "JP103")
      (value "JUMPER-SMT_3_1-NC_TRACE_SILK")
      (footprint "eagle-import:SMT-JUMPER_3_1-NC_TRACE_SILK")
      (libsource (lib "eagle-import") (part "JUMPER-SMT_3_1-NC_TRACE_SILK"))
    )
    (comp (ref "JP105")
      (value "JUMPER-SMT_3_1-NC_TRACE_SILK")
      (footprint "eagle-import:SMT-JUMPER_3_1-NC_TRACE_SILK")
      (libsource (lib "eagle-import") (part "JUMPER-SMT_3_1-NC_TRACE_SILK"))
    )
    (comp (ref "JP106")
      (value "JUMPER-SMT_3_1-NC_TRACE_SILK")
      (footprint "eagle-import:SMT-JUMPER_3_1-NC_TRACE_SILK")
      (libsource (lib "eagle-import") (part "JUMPER-SMT_3_1-NC_TRACE_SILK"))
    )
    (comp (ref "JP107")
      (value "JUMPER-SMT_3_NO_SILK")
      (footprint "eagle-import:SMT-JUMPER_3_NO_SILK")
      (libsource (lib "eagle-import") (part "JUMPER-SMT_3_NO_SILK"))
    )
    (comp (ref "JP108")
      (value "JUMPER-SMT_3_1-NC_TRACE_SILK")
      (footprint "eagle-import:SMT-JUMPER_3_1-NC_TRACE_SILK")
      (libsource (lib "eagle-import") (part "JUMPER-SMT_3_1-NC_TRACE_SILK"))
    )
    (comp (ref "JP109")
      (value "JUMPER-SMT_3_1-NC_TRACE_SILK")
      (footprint "eagle-import:SMT-JUMPER_3_1-NC_TRACE_SILK")
      (libsource (lib "eagle-import") (part "JUMPER-SMT_3_1-NC_TRACE_SILK"))
    )
    (comp (ref "JP110")
      (value "JUMPER-SMT_3_1-NC_TRACE_SILK")
      (footprint "eagle-import:SMT-JUMPER_3_1-NC_TRACE_SILK")
      (libsource (lib "eagle-import") (part "JUMPER-SMT_3_1-NC_TRACE_SILK"))
    )
    (comp (ref "JP111")
      (value "JUMPER-SMT_3_1-NC_TRACE_SILK")
      (footprint "eagle-import:SMT-JUMPER_3_1-NC_TRACE_SILK")
      (libsource (lib "eagle-import") (part "JUMPER-SMT_3_1-NC_TRACE_SILK"))
    )
    (comp (ref "R2")
      (value "1k")
      (footprint "eagle-import:.0603-A")
      (libsource (lib "eagle-import") (part "R-US_0603-A"))
    )
    (comp (ref "R3")
      (value "1k")
      (footprint "eagle-import:.0603-A")
      (libsource (lib "eagle-import") (part "R-US_0603-A"))
    )
    (comp (ref "R4")
      (value "1k")
      (footprint "eagle-import:.0603-A")
      (libsource (lib "eagle-import") (part "R-US_0603-A"))
    )
    (comp (ref "R5")
      (value "1k")
      (footprint "eagle-import:.0603-A")
      (libsource (lib "eagle-import") (part "R-US_0603-A"))
    )
    (comp (ref "R8")
      (value "10K")
      (footprint "eagle-import:ARRAY_EXBA-M")
      (fields
        (field (name "MFR") "Panasonic Electronic Components")
        (field (name "MPN") "EXB-A10PXXXJ")
        (field (name "MPN_1") "EXB-A10P103J")
      )
      (libsource (lib "eagle-import") (part "EXB-A10P391JC_ARRAY_EXBA-M"))
    )
    (comp (ref "R9")
      (value "10K")
      (footprint "eagle-import:ARRAY_EXBA-M")
      (fields
        (field (name "MFR") "Panasonic Electronic Components")
        (field (name "MPN") "EXB-A10PXXXJ")
        (field (name "MPN_1") "EXB-A10P103J")
      )
      (libsource (lib "eagle-import") (part "EXB-A10P391JC_ARRAY_EXBA-M"))
    )
    (comp (ref "R10")
      (value "10K")
      (footprint "eagle-import:ARRAY_EXBA-M")
      (fields
        (field (name "MFR") "Panasonic Electronic Components")
        (field (name "MPN") "EXB-A10PXXXJ")
        (field (name "DPN") "U7103CT-ND")
        (field (name "MPN_1") "EXB-A10P103J")
      )
      (libsource (lib "eagle-import") (part "EXB-A10P391JC_ARRAY_EXBA-M"))
    )
    (comp (ref "R11")
      (value "10k")
      (footprint "eagle-import:.0603-A")
      (libsource (lib "eagle-import") (part "R-US_0603-A"))
    )
    (comp (ref "R12")
      (value "10k")
      (footprint "eagle-import:.0603-A")
      (libsource (lib "eagle-import") (part "R-US_0603-A"))
    )
    (comp (ref "R14")
      (value "10k")
      (footprint "eagle-import:.0603-A")
      (libsource (lib "eagle-import") (part "R-US_0603-A"))
    )
    (comp (ref "R16")
      (value "10k")
      (footprint "eagle-import:.0603-A")
      (libsource (lib "eagle-import") (part "R-US_0603-A"))
    )
    (comp (ref "R17")
      (value "4.7k")
      (footprint "eagle-import:.0603-A")
      (libsource (lib "eagle-import") (part "R-US_0603-A"))
    )
    (comp (ref "R18")
      (value "4.7k")
      (footprint "eagle-import:.0603-A")
      (libsource (lib "eagle-import") (part "R-US_0603-A"))
    )
    (comp (ref "R21")
      (value "10k")
      (footprint "eagle-import:.0603-A")
      (libsource (lib "eagle-import") (part "R-US_0603-A"))
    )
    (comp (ref "R24")
      (value "100K")
      (footprint "eagle-import:ARRAY_EXBA-M")
      (fields
        (field (name "MFR") "Panasonic Electronic Components")
        (field (name "MPN") "EXB-A10PXXXJ")
        (field (name "MPN_1") "EXB-A10P104J")
      )
      (libsource (lib "eagle-import") (part "EXB-A10P391JC_ARRAY_EXBA-M"))
    )
    (comp (ref "R25")
      (value "100K")
      (footprint "eagle-import:ARRAY_EXBA-M")
      (fields
        (field (name "MFR") "Panasonic Electronic Components")
        (field (name "MPN") "EXB-A10PXXXJ")
        (field (name "MPN_1") "EXB-A10P104J")
      )
      (libsource (lib "eagle-import") (part "EXB-A10P391JC_ARRAY_EXBA-M"))
    )
    (comp (ref "R26")
      (value "100K")
      (footprint "eagle-import:ARRAY_EXBA-M")
      (fields
        (field (name "MFR") "Panasonic Electronic Components")
        (field (name "MPN") "EXB-A10PXXXJ")
        (field (name "MPN_1") "EXB-A10P104J")
      )
      (libsource (lib "eagle-import") (part "EXB-A10P391JC_ARRAY_EXBA-M"))
    )
    (comp (ref "R29")
      (value "4.7k")
      (footprint "eagle-import:.0603-A")
      (libsource (lib "eagle-import") (part "R-US_0603-A"))
    )
    (comp (ref "R30")
      (value "4.7k")
      (footprint "eagle-import:.0603-A")
      (libsource (lib "eagle-import") (part "R-US_0603-A"))
    )
    (comp (ref "R59")
      (value "DNP")
      (footprint "eagle-import:.0603-A")
      (libsource (lib "eagle-import") (part "R-US_0603-A"))
    )
    (comp (ref "R60")
      (value "DNP")
      (footprint "eagle-import:.0603-A")
      (libsource (lib "eagle-import") (part "R-US_0603-A"))
    )
    (comp (ref "TP5")
      (value "TEST-POINT3X4")
      (footprint "eagle-import:PAD.03X.04")
      (libsource (lib "eagle-import") (part "TEST-POINT3X4"))
    )
    (comp (ref "TP6")
      (value "TEST-POINT3X4")
      (footprint "eagle-import:PAD.03X.04")
      (libsource (lib "eagle-import") (part "TEST-POINT3X4"))
    )
    (comp (ref "TP7")
      (value "TEST-POINT3X4")
      (footprint "eagle-import:PAD.03X.04")
      (libsource (lib "eagle-import") (part "TEST-POINT3X4"))
    )
    (comp (ref "TP8")
      (value "TEST-POINT3X4")
      (footprint "eagle-import:PAD.03X.04")
      (libsource (lib "eagle-import") (part "TEST-POINT3X4"))
    )
    (comp (ref "TP9")
      (value "TEST-POINT3X4")
      (footprint "eagle-import:PAD.03X.04")
      (libsource (lib "eagle-import") (part "TEST-POINT3X4"))
    )
    (comp (ref "TP10")
      (value "TEST-POINT3X4")
      (footprint "eagle-import:PAD.03X.04")
      (libsource (lib "eagle-import") (part "TEST-POINT3X4"))
    )
    (comp (ref "TP11")
      (value "TEST-POINT3X4")
      (footprint "eagle-import:PAD.03X.04")
      (libsource (lib "eagle-import") (part "TEST-POINT3X4"))
    )
    (comp (ref "TP12")
      (value "TEST-POINT3X4")
      (footprint "eagle-import:PAD.03X.04")
      (libsource (lib "eagle-import") (part "TEST-POINT3X4"))
    )
    (comp (ref "TP13")
      (value "TEST-POINT3X4")
      (footprint "eagle-import:PAD.03X.04")
      (libsource (lib "eagle-import") (part "TEST-POINT3X4"))
    )
    (comp (ref "TP15")
      (value "TEST-POINT3X4")
      (footprint "eagle-import:PAD.03X.04")
      (libsource (lib "eagle-import") (part "TEST-POINT3X4"))
    )
    (comp (ref "TP16")
      (value "TEST-POINT3X4")
      (footprint "eagle-import:PAD.03X.04")
      (libsource (lib "eagle-import") (part "TEST-POINT3X4"))
    )
    (comp (ref "TP17")
      (value "TEST-POINT3X4")
      (footprint "eagle-import:PAD.03X.04")
      (libsource (lib "eagle-import") (part "TEST-POINT3X4"))
    )
    (comp (ref "TP18")
      (value "TEST-POINT3X4")
      (footprint "eagle-import:PAD.03X.04")
      (libsource (lib "eagle-import") (part "TEST-POINT3X4"))
    )
    (comp (ref "TP19")
      (value "TEST-POINT3X4")
      (footprint "eagle-import:PAD.03X.04")
      (libsource (lib "eagle-import") (part "TEST-POINT3X4"))
    )
    (comp (ref "TP20")
      (value "TEST-POINT3X4")
      (footprint "eagle-import:PAD.03X.04")
      (libsource (lib "eagle-import") (part "TEST-POINT3X4"))
    )
    (comp (ref "TP21")
      (value "TEST-POINT3X4")
      (footprint "eagle-import:PAD.03X.04")
      (libsource (lib "eagle-import") (part "TEST-POINT3X4"))
    )
    (comp (ref "TP22")
      (value "TEST-POINT3X4")
      (footprint "eagle-import:PAD.03X.04")
      (libsource (lib "eagle-import") (part "TEST-POINT3X4"))
    )
    (comp (ref "TP23")
      (value "TEST-POINT3X4")
      (footprint "eagle-import:PAD.03X.04")
      (libsource (lib "eagle-import") (part "TEST-POINT3X4"))
    )
    (comp (ref "TP24")
      (value "TEST-POINT3X4")
      (footprint "eagle-import:PAD.03X.04")
      (libsource (lib "eagle-import") (part "TEST-POINT3X4"))
    )
    (comp (ref "TP26")
      (value "TEST-POINT3X4")
      (footprint "eagle-import:PAD.03X.04")
      (libsource (lib "eagle-import") (part "TEST-POINT3X4"))
    )
    (comp (ref "TP27")
      (value "TEST-POINT3X4")
      (footprint "eagle-import:PAD.03X.04")
      (libsource (lib "eagle-import") (part "TEST-POINT3X4"))
    )
    (comp (ref "TP28")
      (value "TEST-POINT3X4")
      (footprint "eagle-import:PAD.03X.04")
      (libsource (lib "eagle-import") (part "TEST-POINT3X4"))
    )
    (comp (ref "TP29")
      (value "TEST-POINT3X4")
      (footprint "eagle-import:PAD.03X.04")
      (libsource (lib "eagle-import") (part "TEST-POINT3X4"))
    )
    (comp (ref "TP30")
      (value "TEST-POINT3X4")
      (footprint "eagle-import:PAD.03X.04")
      (libsource (lib "eagle-import") (part "TEST-POINT3X4"))
    )
    (comp (ref "TP35")
      (value "TEST-POINT3X4")
      (footprint "eagle-import:PAD.03X.04")
      (libsource (lib "eagle-import") (part "TEST-POINT3X4"))
    )
    (comp (ref "TP36")
      (value "TEST-POINT3X4")
      (footprint "eagle-import:PAD.03X.04")
      (libsource (lib "eagle-import") (part "TEST-POINT3X4"))
    )
    (comp (ref "TP37")
      (value "TEST-POINT3X4")
      (footprint "eagle-import:PAD.03X.04")
      (libsource (lib "eagle-import") (part "TEST-POINT3X4"))
    )
    (comp (ref "TP40")
      (value "TEST-POINT3X4")
      (footprint "eagle-import:PAD.03X.04")
      (libsource (lib "eagle-import") (part "TEST-POINT3X4"))
    )
    (comp (ref "TP69")
      (value "TEST-POINT3X4")
      (footprint "eagle-import:PAD.03X.04")
      (libsource (lib "eagle-import") (part "TEST-POINT3X4"))
    )
    (comp (ref "TP100")
      (value "TEST-POINT3X4")
      (footprint "eagle-import:PAD.03X.04")
      (libsource (lib "eagle-import") (part "TEST-POINT3X4"))
    )
    (comp (ref "TP101")
      (value "TEST-POINT3X4")
      (footprint "eagle-import:PAD.03X.04")
      (libsource (lib "eagle-import") (part "TEST-POINT3X4"))
    )
    (comp (ref "TP103")
      (value "TEST-POINT3X4")
      (footprint "eagle-import:PAD.03X.04")
      (libsource (lib "eagle-import") (part "TEST-POINT3X4"))
    )
    (comp (ref "TP104")
      (value "TEST-POINT3X4")
      (footprint "eagle-import:PAD.03X.04")
      (libsource (lib "eagle-import") (part "TEST-POINT3X4"))
    )
    (comp (ref "TP105")
      (value "TEST-POINT3X4")
      (footprint "eagle-import:PAD.03X.04")
      (libsource (lib "eagle-import") (part "TEST-POINT3X4"))
    )
    (comp (ref "TP106")
      (value "TEST-POINT3X4")
      (footprint "eagle-import:PAD.03X.04")
      (libsource (lib "eagle-import") (part "TEST-POINT3X4"))
    )
    (comp (ref "TP107")
      (value "TEST-POINT3X4")
      (footprint "eagle-import:PAD.03X.04")
      (libsource (lib "eagle-import") (part "TEST-POINT3X4"))
    )
    (comp (ref "TP108")
      (value "TEST-POINT3X4")
      (footprint "eagle-import:PAD.03X.04")
      (libsource (lib "eagle-import") (part "TEST-POINT3X4"))
    )
    (comp (ref "TP111")
      (value "TEST-POINT3X4")
      (footprint "eagle-import:PAD.03X.04")
      (libsource (lib "eagle-import") (part "TEST-POINT3X4"))
    )
    (comp (ref "TP113")
      (value "TEST-POINT3X4")
      (footprint "eagle-import:PAD.03X.04")
      (libsource (lib "eagle-import") (part "TEST-POINT3X4"))
    )
    (comp (ref "TP114")
      (value "TEST-POINT3X4")
      (footprint "eagle-import:PAD.03X.04")
      (libsource (lib "eagle-import") (part "TEST-POINT3X4"))
    )
    (comp (ref "TP115")
      (value "TEST-POINT3X4")
      (footprint "eagle-import:PAD.03X.04")
      (libsource (lib "eagle-import") (part "TEST-POINT3X4"))
    )
    (comp (ref "TP116")
      (value "TEST-POINT3X4")
      (footprint "eagle-import:PAD.03X.04")
      (libsource (lib "eagle-import") (part "TEST-POINT3X4"))
    )
    (comp (ref "TP117")
      (value "TEST-POINT3X4")
      (footprint "eagle-import:PAD.03X.04")
      (libsource (lib "eagle-import") (part "TEST-POINT3X4"))
    )
    (comp (ref "TP118")
      (value "TEST-POINT3X4")
      (footprint "eagle-import:PAD.03X.04")
      (libsource (lib "eagle-import") (part "TEST-POINT3X4"))
    )
    (comp (ref "TP119")
      (value "TEST-POINT3X4")
      (footprint "eagle-import:PAD.03X.04")
      (libsource (lib "eagle-import") (part "TEST-POINT3X4"))
    )
    (comp (ref "TP120")
      (value "TEST-POINT3X4")
      (footprint "eagle-import:PAD.03X.04")
      (libsource (lib "eagle-import") (part "TEST-POINT3X4"))
    )
    (comp (ref "TP122")
      (value "TEST-POINT3X4")
      (footprint "eagle-import:PAD.03X.04")
      (libsource (lib "eagle-import") (part "TEST-POINT3X4"))
    )
    (comp (ref "TP123")
      (value "TEST-POINT3X4")
      (footprint "eagle-import:PAD.03X.04")
      (libsource (lib "eagle-import") (part "TEST-POINT3X4"))
    )
    (comp (ref "TP124")
      (value "TEST-POINT3X4")
      (footprint "eagle-import:PAD.03X.04")
      (libsource (lib "eagle-import") (part "TEST-POINT3X4"))
    )
    (comp (ref "TP125")
      (value "TEST-POINT3X4")
      (footprint "eagle-import:PAD.03X.04")
      (libsource (lib "eagle-import") (part "TEST-POINT3X4"))
    )
    (comp (ref "TP126")
      (value "TEST-POINT3X4")
      (footprint "eagle-import:PAD.03X.04")
      (libsource (lib "eagle-import") (part "TEST-POINT3X4"))
    )
    (comp (ref "TP127")
      (value "TEST-POINT3X4")
      (footprint "eagle-import:PAD.03X.04")
      (libsource (lib "eagle-import") (part "TEST-POINT3X4"))
    )
    (comp (ref "TP128")
      (value "TEST-POINT3X4")
      (footprint "eagle-import:PAD.03X.04")
      (libsource (lib "eagle-import") (part "TEST-POINT3X4"))
    )
    (comp (ref "TP131")
      (value "TEST-POINT3X4")
      (footprint "eagle-import:PAD.03X.04")
      (libsource (lib "eagle-import") (part "TEST-POINT3X4"))
    )
    (comp (ref "TP134")
      (value "TEST-POINT3X4")
      (footprint "eagle-import:PAD.03X.04")
      (libsource (lib "eagle-import") (part "TEST-POINT3X4"))
    )
    (comp (ref "TP135")
      (value "TEST-POINT3X4")
      (footprint "eagle-import:PAD.03X.04")
      (libsource (lib "eagle-import") (part "TEST-POINT3X4"))
    )
    (comp (ref "TP137")
      (value "TEST-POINT3X4")
      (footprint "eagle-import:PAD.03X.04")
      (libsource (lib "eagle-import") (part "TEST-POINT3X4"))
    )
    (comp (ref "TP142")
      (value "TEST-POINT3X4")
      (footprint "eagle-import:PAD.03X.04")
      (libsource (lib "eagle-import") (part "TEST-POINT3X4"))
    )
    (comp (ref "TP143")
      (value "TEST-POINT3X4")
      (footprint "eagle-import:PAD.03X.04")
      (libsource (lib "eagle-import") (part "TEST-POINT3X4"))
    )
    (comp (ref "TP146")
      (value "TEST-POINT3X4")
      (footprint "eagle-import:PAD.03X.04")
      (libsource (lib "eagle-import") (part "TEST-POINT3X4"))
    )
    (comp (ref "TP147")
      (value "TEST-POINT3X4")
      (footprint "eagle-import:PAD.03X.04")
      (libsource (lib "eagle-import") (part "TEST-POINT3X4"))
    )
    (comp (ref "TP148")
      (value "TEST-POINT3X4")
      (footprint "eagle-import:PAD.03X.04")
      (libsource (lib "eagle-import") (part "TEST-POINT3X4"))
    )
    (comp (ref "TP149")
      (value "TEST-POINT3X4")
      (footprint "eagle-import:PAD.03X.04")
      (libsource (lib "eagle-import") (part "TEST-POINT3X4"))
    )
    (comp (ref "TP152")
      (value "TEST-POINT3X4")
      (footprint "eagle-import:PAD.03X.04")
      (libsource (lib "eagle-import") (part "TEST-POINT3X4"))
    )
    (comp (ref "TP153")
      (value "TEST-POINT3X4")
      (footprint "eagle-import:PAD.03X.04")
      (libsource (lib "eagle-import") (part "TEST-POINT3X4"))
    )
    (comp (ref "TP158")
      (value "TEST-POINT3X4")
      (footprint "eagle-import:PAD.03X.04")
      (libsource (lib "eagle-import") (part "TEST-POINT3X4"))
    )
    (comp (ref "TP159")
      (value "TEST-POINT3X4")
      (footprint "eagle-import:PAD.03X.04")
      (libsource (lib "eagle-import") (part "TEST-POINT3X4"))
    )
    (comp (ref "TP162")
      (value "TEST-POINT3X4")
      (footprint "eagle-import:PAD.03X.04")
      (libsource (lib "eagle-import") (part "TEST-POINT3X4"))
    )
    (comp (ref "TP174")
      (value "TEST-POINT3X4")
      (footprint "eagle-import:PAD.03X.04")
      (libsource (lib "eagle-import") (part "TEST-POINT3X4"))
    )
    (comp (ref "TP177")
      (value "TEST-POINT3X4")
      (footprint "eagle-import:PAD.03X.04")
      (libsource (lib "eagle-import") (part "TEST-POINT3X4"))
    )
    (comp (ref "TP178")
      (value "TEST-POINT3X4")
      (footprint "eagle-import:PAD.03X.04")
      (libsource (lib "eagle-import") (part "TEST-POINT3X4"))
    )
    (comp (ref "TP180")
      (value "TEST-POINT3X4")
      (footprint "eagle-import:PAD.03X.04")
      (libsource (lib "eagle-import") (part "TEST-POINT3X4"))
    )
    (comp (ref "U3")
      (value "THGBMJG7C2LBAU8")
      (footprint "eagle-import:BGA-153(11.5X13)(EMMC-BA)")
      (libsource (lib "eagle-import") (part "EMMC+RESET+5.1-COMPATIBLE-BA"))
    )
    (comp (ref "U5")
      (value "SN74LVC8T245MPWREPPW24-M")
      (footprint "eagle-import:PW24-M")
      (fields (field (name "MPN") " ‎SN74LVC8T245MPWREP‎"))
      (libsource (lib "eagle-import") (part "SN74LVC8T245MPWREPPW24-M"))
    )
    (comp (ref "U6")
      (value "CLVCH16T245MDGGREP")
      (footprint "eagle-import:DGG48-M")
      (libsource (lib "eagle-import") (part "CLVCH16T245MDGGREP"))
    )
    (comp (ref "U8")
      (value "TLV70028QDDCRQ1")
      (footprint "eagle-import:SOT23-5")
      (fields (field (name "MPN") "TLV70028DDCR"))
      (libsource (lib "eagle-import") (part "TLV70028QDDCRQ1"))
    )
    (comp (ref "U9")
      (value "TCA9509DGKRDGK8-M")
      (footprint "eagle-import:DGK8-M")
      (fields (field (name "MFR") "Texas Instruments") (field (name "MPN") "TCA9509DGKR"))
      (libsource (lib "eagle-import") (part "TCA9509DGKRDGK8-M"))
    )
    (comp (ref "U11")
      (value "TCAN330")
      (footprint "eagle-import:SOT23-8_TI-DCN")
      (fields (field (name "MPN") "TCAN330GDCNT"))
      (libsource (lib "eagle-import") (part "TCAN330"))
    )
    (comp (ref "U17")
      (value "25AAXX")
      (footprint "eagle-import:SOIC8")
      (fields (field (name "MPN") "25AA02E48T-I/SN"))
      (libsource (lib "eagle-import") (part "25AAXX"))
    )
    (comp (ref "C32")
      (value "1uF")
      (footprint "eagle-import:.0805-B-NOSILK")
      (libsource (lib "eagle-import") (part "C-EU0805-B-NOSILK"))
    )
    (comp (ref "C33")
      (value "1uF")
      (footprint "eagle-import:.0603-A")
      (fields (field (name "MFR") "Samsung") (field (name "MPN") "CL05B104KO5NNNC"))
      (libsource (lib "eagle-import") (part "C-EU0603-A"))
    )
    (comp (ref "C34")
      (value "1uF")
      (footprint "eagle-import:.0603-A")
      (libsource (lib "eagle-import") (part "C-EU0603-A"))
    )
    (comp (ref "C35")
      (value "1uF")
      (footprint "eagle-import:.0805-B-NOSILK")
      (libsource (lib "eagle-import") (part "C-EU0805-B-NOSILK"))
    )
    (comp (ref "C36")
      (value "22uF")
      (footprint "eagle-import:C1210")
      (libsource (lib "eagle-import") (part "C-EUC1210"))
    )
    (comp (ref "C37")
      (value "1uF")
      (footprint "eagle-import:.0603-A")
      (libsource (lib "eagle-import") (part "C-EU0603-A"))
    )
    (comp (ref "C38")
      (value "10uF")
      (footprint "eagle-import:.0805-B")
      (libsource (lib "eagle-import") (part "C-EU0805-B"))
    )
    (comp (ref "C39")
      (value "0.1uF")
      (footprint "eagle-import:.0603-A")
      (libsource (lib "eagle-import") (part "C-EU0603-A"))
    )
    (comp (ref "C44")
      (value "10uF")
      (footprint "eagle-import:.0805-B")
      (libsource (lib "eagle-import") (part "C-EU0805-B"))
    )
    (comp (ref "D6")
      (value "AMBER")
      (footprint "eagle-import:LED-0603")
      (libsource (lib "eagle-import") (part "SparkFun-LED_529_LED-GREEN0603"))
    )
    (comp (ref "D7")
      (value "GREEN")
      (footprint "eagle-import:LED-0603")
      (libsource (lib "eagle-import") (part "LED-GREEN0603"))
    )
    (comp (ref "D8")
      (value "GREEN")
      (footprint "eagle-import:LED-0603")
      (libsource (lib "eagle-import") (part "LED-GREEN0603"))
    )
    (comp (ref "L1")
      (value "6.8u")
      (footprint "eagle-import:ECS-MPI4040")
      (fields (field (name "MPN") "ECS-MPI4040R4-6R8-R"))
      (libsource (lib "eagle-import") (part "L-ECS-MPI4040"))
    )
    (comp (ref "Q2")
      (value "PMV45EN")
      (footprint "eagle-import:SOT23")
      (fields (field (name "MPN") "PMV45EN2R"))
      (libsource (lib "eagle-import") (part "PMV45EN"))
    )
    (comp (ref "Q3")
      (value "DMP2240UDM")
      (footprint "eagle-import:SOT23-6")
      (fields (field (name "MPN") "DMP2240UDM-7"))
      (libsource (lib "eagle-import") (part "Q-MOSFET-PCH-dual-SOT23-6_MOSFET-PCH-SOT23-6"))
    )
    (comp (ref "Q4")
      (value "PMV45EN")
      (footprint "eagle-import:SOT23")
      (fields (field (name "MPN") "PMV45EN2R"))
      (libsource (lib "eagle-import") (part "PMV45EN"))
    )
    (comp (ref "Q5")
      (value "MOSFET-PCH-SOT23-6")
      (footprint "eagle-import:SOT23-6")
      (fields (field (name "MPN") "DMP3050LVT-7") (field (name "MPN_1") "DMP3050LVT-7"))
      (libsource (lib "eagle-import") (part "MOSFET-PCH-SOT23-6"))
    )
    (comp (ref "Q6")
      (value "MOSFET-PCH-SOT23-6")
      (footprint "eagle-import:SOT23-6")
      (fields (field (name "MPN") "DMP3050LVT-7") (field (name "MPN_1") "DMP3050LVT-7"))
      (libsource (lib "eagle-import") (part "MOSFET-PCH-SOT23-6"))
    )
    (comp (ref "R32")
      (value "10k")
      (footprint "eagle-import:.0603-A")
      (libsource (lib "eagle-import") (part "R-US_0603-A"))
    )
    (comp (ref "R33")
      (value "100k")
      (footprint "eagle-import:.0603-A")
      (fields (field (name "MFR") "Samsung") (field (name "MPN") "RC1005F6653CS"))
      (libsource (lib "eagle-import") (part "R-US_0603-A"))
    )
    (comp (ref "R34")
      (value "10k")
      (footprint "eagle-import:.0603-A")
      (libsource (lib "eagle-import") (part "R-US_0603-A"))
    )
    (comp (ref "R35")
      (value "665k")
      (footprint "eagle-import:.0603-A")
      (libsource (lib "eagle-import") (part "R-US_0603-A"))
    )
    (comp (ref "R36")
      (value "1M")
      (footprint "eagle-import:.0603-A")
      (libsource (lib "eagle-import") (part "R-US_0603-A"))
    )
    (comp (ref "R37")
      (value "330k")
      (footprint "eagle-import:.0603-A")
      (libsource (lib "eagle-import") (part "R-US_0603-A"))
    )
    (comp (ref "R38")
      (value "10k")
      (footprint "eagle-import:.0603-A")
      (fields (field (name "MFR") "Samsung") (field (name "MPN") "RC1005F6653CS"))
      (libsource (lib "eagle-import") (part "R-US_0603-A"))
    )
    (comp (ref "R39")
      (value "10k")
      (footprint "eagle-import:.0603-A")
      (libsource (lib "eagle-import") (part "R-US_0603-A"))
    )
    (comp (ref "R40")
      (value "NP")
      (footprint "eagle-import:.0603-A")
      (fields (field (name "MFR") "Samsung") (field (name "MPN") "RC1005F6653CS"))
      (libsource (lib "eagle-import") (part "R-US_0603-A"))
    )
    (comp (ref "R41")
      (value "100")
      (footprint "eagle-import:.0603-A")
      (libsource (lib "eagle-import") (part "R-US_0603-A"))
    )
    (comp (ref "R42")
      (value "NP")
      (footprint "eagle-import:.0603-A")
      (fields (field (name "MFR") "Samsung") (field (name "MPN") "RC1005F6653CS"))
      (libsource (lib "eagle-import") (part "R-US_0603-A"))
    )
    (comp (ref "R43")
      (value "665k")
      (footprint "eagle-import:.0603-A")
      (libsource (lib "eagle-import") (part "R-US_0603-A"))
    )
    (comp (ref "R44")
      (value "1M")
      (footprint "eagle-import:.0603-A")
      (libsource (lib "eagle-import") (part "R-US_0603-A"))
    )
    (comp (ref "R45")
      (value "330k")
      (footprint "eagle-import:.0603-A")
      (libsource (lib "eagle-import") (part "R-US_0603-A"))
    )
    (comp (ref "R46")
      (value "10k")
      (footprint "eagle-import:.0603-A")
      (libsource (lib "eagle-import") (part "R-US_0603-A"))
    )
    (comp (ref "R47")
      (value "0")
      (footprint "eagle-import:.0603-A")
      (libsource (lib "eagle-import") (part "R-US_0603-A"))
    )
    (comp (ref "R48")
      (value "100")
      (footprint "eagle-import:.0603-A")
      (libsource (lib "eagle-import") (part "R-US_0603-A"))
    )
    (comp (ref "R49")
      (value "2.7k")
      (footprint "eagle-import:.0603-A")
      (libsource (lib "eagle-import") (part "R-US_0603-A"))
    )
    (comp (ref "R50")
      (value "0")
      (footprint "eagle-import:.0603-A")
      (libsource (lib "eagle-import") (part "R-US_0603-A"))
    )
    (comp (ref "R51")
      (value "NP")
      (footprint "eagle-import:.0603-A")
      (fields (field (name "MFR") "Samsung") (field (name "MPN") "RC1005F6653CS"))
      (libsource (lib "eagle-import") (part "R-US_0603-A"))
    )
    (comp (ref "R52")
      (value "10k")
      (footprint "eagle-import:.0603-A")
      (libsource (lib "eagle-import") (part "R-US_0603-A"))
    )
    (comp (ref "R53")
      (value "NP")
      (footprint "eagle-import:.0603-A")
      (fields (field (name "MFR") "Samsung") (field (name "MPN") "RC1005F6653CS"))
      (libsource (lib "eagle-import") (part "R-US_0603-A"))
    )
    (comp (ref "R54")
      (value "NP")
      (footprint "eagle-import:.0603-A")
      (fields (field (name "MFR") "Samsung") (field (name "MPN") "RC1005F6653CS"))
      (libsource (lib "eagle-import") (part "R-US_0603-A"))
    )
    (comp (ref "R55")
      (value "NP")
      (footprint "eagle-import:.0603-A")
      (fields (field (name "MFR") "Samsung") (field (name "MPN") "RC1005F6653CS"))
      (libsource (lib "eagle-import") (part "R-US_0603-A"))
    )
    (comp (ref "R56")
      (value "NP")
      (footprint "eagle-import:.0603-A")
      (fields (field (name "MFR") "Samsung") (field (name "MPN") "RC1005F6653CS"))
      (libsource (lib "eagle-import") (part "R-US_0603-A"))
    )
    (comp (ref "R57")
      (value "NP")
      (footprint "eagle-import:.0603-A")
      (fields (field (name "MFR") "Samsung") (field (name "MPN") "RC1005F6653CS"))
      (libsource (lib "eagle-import") (part "R-US_0603-A"))
    )
    (comp (ref "R58")
      (value "NP")
      (footprint "eagle-import:.0603-A")
      (fields (field (name "MFR") "Samsung") (field (name "MPN") "RC1005F6653CS"))
      (libsource (lib "eagle-import") (part "R-US_0603-A"))
    )
    (comp (ref "R61")
      (value "2.7k")
      (footprint "eagle-import:.0603-A")
      (libsource (lib "eagle-import") (part "R-US_0603-A"))
    )
    (comp (ref "R62")
      (value "2.7k")
      (footprint "eagle-import:.0603-A")
      (libsource (lib "eagle-import") (part "R-US_0603-A"))
    )
    (comp (ref "R63")
      (value "100m")
      (footprint "eagle-import:R1206")
      (libsource (lib "eagle-import") (part "rcl_334_R-US_R1206"))
    )
    (comp (ref "R64")
      (value "10k")
      (footprint "eagle-import:.0603-A")
      (libsource (lib "eagle-import") (part "R-US_0603-A"))
    )
    (comp (ref "R65")
      (value "NP")
      (footprint "eagle-import:.0603-A")
      (fields (field (name "MFR") "Samsung") (field (name "MPN") "RC1005F6653CS"))
      (libsource (lib "eagle-import") (part "R-US_0603-A"))
    )
    (comp (ref "R66")
      (value "NP")
      (footprint "eagle-import:.0603-A")
      (fields (field (name "MFR") "Samsung") (field (name "MPN") "RC1005F6653CS"))
      (libsource (lib "eagle-import") (part "R-US_0603-A"))
    )
    (comp (ref "R67")
      (value "NP")
      (footprint "eagle-import:.0603-A")
      (fields (field (name "MFR") "Samsung") (field (name "MPN") "RC1005F6653CS"))
      (libsource (lib "eagle-import") (part "R-US_0603-A"))
    )
    (comp (ref "R68")
      (value "NP")
      (footprint "eagle-import:.0603-A")
      (fields (field (name "MFR") "Samsung") (field (name "MPN") "RC1005F6653CS"))
      (libsource (lib "eagle-import") (part "R-US_0603-A"))
    )
    (comp (ref "R69")
      (value "NP")
      (footprint "eagle-import:.0603-A")
      (fields (field (name "MFR") "Samsung") (field (name "MPN") "RC1005F6653CS"))
      (libsource (lib "eagle-import") (part "R-US_0603-A"))
    )
    (comp (ref "R70")
      (value "NP")
      (footprint "eagle-import:.0603-A")
      (fields (field (name "MFR") "Samsung") (field (name "MPN") "RC1005F6653CS"))
      (libsource (lib "eagle-import") (part "R-US_0603-A"))
    )
    (comp (ref "R71")
      (value "100")
      (footprint "eagle-import:.0603-A")
      (libsource (lib "eagle-import") (part "R-US_0603-A"))
    )
    (comp (ref "R72")
      (value "10k")
      (footprint "eagle-import:.0603-A")
      (libsource (lib "eagle-import") (part "R-US_0603-A"))
    )
    (comp (ref "TP41")
      (value "TEST-POINT")
      (footprint "eagle-import:2MM-TEST-POINT")
      (libsource (lib "eagle-import") (part "TEST-POINT"))
    )
    (comp (ref "TP42")
      (value "TEST-POINT")
      (footprint "eagle-import:2MM-TEST-POINT")
      (libsource (lib "eagle-import") (part "TEST-POINT"))
    )
    (comp (ref "TP43")
      (value "TEST-POINT")
      (footprint "eagle-import:2MM-TEST-POINT")
      (libsource (lib "eagle-import") (part "TEST-POINT"))
    )
    (comp (ref "TP44")
      (value "TEST-POINT")
      (footprint "eagle-import:2MM-TEST-POINT")
      (libsource (lib "eagle-import") (part "TEST-POINT"))
    )
    (comp (ref "TP45")
      (value "TEST-POINT")
      (footprint "eagle-import:2MM-TEST-POINT")
      (libsource (lib "eagle-import") (part "TEST-POINT"))
    )
    (comp (ref "TP46")
      (value "TEST-POINT")
      (footprint "eagle-import:2MM-TEST-POINT")
      (libsource (lib "eagle-import") (part "TEST-POINT"))
    )
    (comp (ref "TP47")
      (value "TEST-POINT")
      (footprint "eagle-import:2MM-TEST-POINT")
      (libsource (lib "eagle-import") (part "TEST-POINT"))
    )
    (comp (ref "TP48")
      (value "TEST-POINT")
      (footprint "eagle-import:2MM-TEST-POINT")
      (libsource (lib "eagle-import") (part "TEST-POINT"))
    )
    (comp (ref "TP49")
      (value "TEST-POINT")
      (footprint "eagle-import:2MM-TEST-POINT")
      (libsource (lib "eagle-import") (part "TEST-POINT"))
    )
    (comp (ref "TP50")
      (value "TEST-POINT")
      (footprint "eagle-import:2MM-TEST-POINT")
      (libsource (lib "eagle-import") (part "TEST-POINT"))
    )
    (comp (ref "TP51")
      (value "TEST-POINT")
      (footprint "eagle-import:2MM-TEST-POINT")
      (libsource (lib "eagle-import") (part "TEST-POINT"))
    )
    (comp (ref "TP52")
      (value "TEST-POINT")
      (footprint "eagle-import:2MM-TEST-POINT")
      (libsource (lib "eagle-import") (part "TEST-POINT"))
    )
    (comp (ref "TP53")
      (value "TEST-POINT")
      (footprint "eagle-import:2MM-TEST-POINT")
      (libsource (lib "eagle-import") (part "TEST-POINT"))
    )
    (comp (ref "TP54")
      (value "TEST-POINT")
      (footprint "eagle-import:2MM-TEST-POINT")
      (libsource (lib "eagle-import") (part "TEST-POINT"))
    )
    (comp (ref "TP55")
      (value "TEST-POINT")
      (footprint "eagle-import:2MM-TEST-POINT")
      (libsource (lib "eagle-import") (part "TEST-POINT"))
    )
    (comp (ref "TP56")
      (value "TEST-POINT")
      (footprint "eagle-import:2MM-TEST-POINT")
      (libsource (lib "eagle-import") (part "TEST-POINT"))
    )
    (comp (ref "TP57")
      (value "TEST-POINT")
      (footprint "eagle-import:2MM-TEST-POINT")
      (libsource (lib "eagle-import") (part "TEST-POINT"))
    )
    (comp (ref "TP63")
      (value "TEST-POINT")
      (footprint "eagle-import:2MM-TEST-POINT")
      (libsource (lib "eagle-import") (part "TEST-POINT"))
    )
    (comp (ref "TP64")
      (value "TEST-POINT")
      (footprint "eagle-import:2MM-TEST-POINT")
      (libsource (lib "eagle-import") (part "TEST-POINT"))
    )
    (comp (ref "TP65")
      (value "TEST-POINT")
      (footprint "eagle-import:2MM-TEST-POINT")
      (libsource (lib "eagle-import") (part "TEST-POINT"))
    )
    (comp (ref "TP66")
      (value "TEST-POINT")
      (footprint "eagle-import:2MM-TEST-POINT")
      (libsource (lib "eagle-import") (part "TEST-POINT"))
    )
    (comp (ref "TP67")
      (value "TEST-POINT")
      (footprint "eagle-import:2MM-TEST-POINT")
      (libsource (lib "eagle-import") (part "TEST-POINT"))
    )
    (comp (ref "TP68")
      (value "TEST-POINT")
      (footprint "eagle-import:2MM-TEST-POINT")
      (libsource (lib "eagle-import") (part "TEST-POINT"))
    )
    (comp (ref "U12")
      (value "MIC842LYC5")
      (footprint "eagle-import:SC70-5")
      (libsource (lib "eagle-import") (part "MIC842LYC5"))
    )
    (comp (ref "U13")
      (value "MIC842LYC5")
      (footprint "eagle-import:SC70-5")
      (libsource (lib "eagle-import") (part "MIC842LYC5"))
    )
    (comp (ref "U14")
      (value "MAX4211FETE")
      (footprint "eagle-import:QFN65P400X400X80-17T210")
      (fields (field (name "MPN") "MAX4211FETE+"))
      (libsource (lib "eagle-import") (part "MAX4211"))
    )
    (comp (ref "U15")
      (value "TPS62112")
      (footprint "eagle-import:S-PVQFN-16")
      (fields (field (name "MPN") "TPS62112RSAR"))
      (libsource (lib "eagle-import") (part "TPS6211X"))
    )
    (comp (ref "U16")
      (value "MAX7310ATE")
      (footprint "eagle-import:QFN65P400X400X80-17T210")
      (fields
        (field (name "MPN") "MAX7310ATE+")
        (field (name "MFR") "Maxim")
        (field (name "MPN_1") "MAX7310ATE")
      )
      (libsource (lib "eagle-import") (part "MAX7310"))
    )
    (comp (ref "J1")
      (value "ORESAT-DEBUG-CONNECTOR-CARD")
      (footprint "eagle-import:TE_2-1734592-0")
      (fields (field (name "MPN") "2-1734592-0"))
      (libsource (lib "eagle-import") (part "ORESAT-DEBUG-CONNECTOR-CARD"))
    )
    (comp (ref "J4")
      (value "TFM-120-01-L-D-RA")
      (footprint "eagle-import:J-SAMTEC-TFM-120-X1-XXX-D-RA")
      (libsource (lib "eagle-import") (part "J-SAMTEC-TFM-120-X1-XXX-D-RA"))
    )
    (comp (ref "PCB1")
      (value "ORESAT-CARD-V1.3-STAR-TRACKER")
      (footprint "eagle-import:ORESAT-CARD-V1.3-STAR-TRACKER")
      (libsource (lib "eagle-import") (part "ORESAT-CARD-V1.3-STAR-TRACKER"))
    )
    (comp (ref "TP58")
      (value "TEST-POINT3X4")
      (footprint "eagle-import:PAD.03X.04")
      (libsource (lib "eagle-import") (part "TEST-POINT3X4"))
    )
    (comp (ref "TP59")
      (value "TEST-POINT3X4")
      (footprint "eagle-import:PAD.03X.04")
      (libsource (lib "eagle-import") (part "TEST-POINT3X4"))
    )
    (comp (ref "TP60")
      (value "TEST-POINT3X4")
      (footprint "eagle-import:PAD.03X.04")
      (libsource (lib "eagle-import") (part "TEST-POINT3X4"))
    )
    (comp (ref "TP61")
      (value "TEST-POINT3X4")
      (footprint "eagle-import:PAD.03X.04")
      (libsource (lib "eagle-import") (part "TEST-POINT3X4"))
    )
    (comp (ref "TP62")
      (value "TEST-POINT3X4")
      (footprint "eagle-import:PAD.03X.04")
      (libsource (lib "eagle-import") (part "TEST-POINT3X4"))
    )
    (comp (ref "TP183")
      (value "TEST-POINT3X4")
      (footprint "eagle-import:PAD.03X.04")
      (libsource (lib "eagle-import") (part "TEST-POINT3X4"))
    )
    (comp (ref "TP184")
      (value "TEST-POINT3X4")
      (footprint "eagle-import:PAD.03X.04")
      (libsource (lib "eagle-import") (part "TEST-POINT3X4"))
    )
    (comp (ref "U$1")
      (value "FLIGHMARKERNEW")
      (footprint "eagle-import:FLIGHTMARKER_NEW_BOARDS")
      (libsource (lib "eagle-import") (part "FLIGHMARKERNEW"))
    )
  )
  (nets
    (net (code "7") (name "2.8V") (class "Default")
      (node (ref "C21") (pin "1") (pinfunction "1_1") (pintype "passive"))
      (node (ref "C23") (pin "1") (pinfunction "1_1") (pintype "passive"))
      (node (ref "C24") (pin "1") (pinfunction "1_1") (pintype "passive"))
      (node (ref "C25") (pin "1") (pinfunction "1_1") (pintype "passive"))
      (node (ref "C26") (pin "1") (pinfunction "1_1") (pintype "passive"))
      (node (ref "R17") (pin "1") (pinfunction "1_1") (pintype "passive"))
      (node (ref "R18") (pin "1") (pinfunction "1_1") (pintype "passive"))
      (node (ref "U5") (pin "1") (pinfunction "VCCA_1") (pintype "power_in"))
      (node (ref "U6") (pin "18") (pinfunction "VCCB_18") (pintype "power_in"))
      (node (ref "U6") (pin "7") (pinfunction "VCCB_7") (pintype "power_in"))
      (node (ref "U8") (pin "5") (pinfunction "OUT_5") (pintype "power_in"))
      (node (ref "U9") (pin "8") (pinfunction "VCCB_8") (pintype "power_in"))
    )
    (net (code "8") (name "3.3V") (class "Default")
      (node (ref "C11") (pin "1") (pinfunction "1_1") (pintype "passive"))
      (node (ref "C16") (pin "1") (pinfunction "1_1") (pintype "passive"))
      (node (ref "C17") (pin "1") (pinfunction "1_1") (pintype "passive"))
      (node (ref "C2") (pin "1") (pinfunction "1_1") (pintype "passive"))
      (node (ref "C20") (pin "1") (pinfunction "1_1") (pintype "passive"))
      (node (ref "C27") (pin "1") (pinfunction "1_1") (pintype "passive"))
      (node (ref "C28") (pin "1") (pinfunction "1_1") (pintype "passive"))
      (node (ref "C3") (pin "1") (pinfunction "1_1") (pintype "passive"))
      (node (ref "C31") (pin "2") (pinfunction "2_2") (pintype "passive"))
      (node (ref "C40") (pin "2") (pinfunction "2_2") (pintype "passive"))
      (node (ref "C42") (pin "1") (pinfunction "1_1") (pintype "passive"))
      (node (ref "C43") (pin "1") (pinfunction "1_1") (pintype "passive"))
      (node (ref "C5") (pin "1") (pinfunction "1_1") (pintype "passive"))
      (node (ref "C6") (pin "1") (pinfunction "1_1") (pintype "passive"))
      (node (ref "C8") (pin "1") (pinfunction "1_1") (pintype "passive"))
      (node (ref "C9") (pin "1") (pinfunction "1_1") (pintype "passive"))
      (node (ref "J100") (pin "4") (pinfunction "VDD_4") (pintype "bidirectional"))
      (node (ref "J101") (pin "31") (pinfunction "31_31") (pintype "passive"))
      (node (ref "J101") (pin "32") (pinfunction "32_32") (pintype "passive"))
      (node (ref "J101") (pin "33") (pinfunction "33_33") (pintype "passive"))
      (node (ref "J102") (pin "1") (pinfunction "VTREF_1") (pintype "passive"))
      (node (ref "R1") (pin "1") (pinfunction "1_1") (pintype "passive"))
      (node (ref "R10") (pin "10") (pinfunction "55_10") (pintype "passive"))
      (node (ref "R10") (pin "5") (pinfunction "55_5") (pintype "passive"))
      (node (ref "R11") (pin "2") (pinfunction "2_2") (pintype "passive"))
      (node (ref "R12") (pin "2") (pinfunction "2_2") (pintype "passive"))
      (node (ref "R20") (pin "2") (pinfunction "2_2") (pintype "passive"))
      (node (ref "R21") (pin "2") (pinfunction "2_2") (pintype "passive"))
      (node (ref "R22") (pin "2") (pinfunction "2_2") (pintype "passive"))
      (node (ref "R24") (pin "10") (pinfunction "55_10") (pintype "passive"))
      (node (ref "R24") (pin "5") (pinfunction "55_5") (pintype "passive"))
      (node (ref "R29") (pin "1") (pinfunction "1_1") (pintype "passive"))
      (node (ref "R30") (pin "1") (pinfunction "1_1") (pintype "passive"))
      (node (ref "R60") (pin "1") (pinfunction "1_1") (pintype "passive"))
      (node (ref "R8") (pin "10") (pinfunction "55_10") (pintype "passive"))
      (node (ref "R8") (pin "5") (pinfunction "55_5") (pintype "passive"))
      (node (ref "R9") (pin "10") (pinfunction "55_10") (pintype "passive"))
      (node (ref "R9") (pin "5") (pinfunction "55_5") (pintype "passive"))
      (node (ref "TP25") (pin "P$1") (pinfunction "1_P$1") (pintype "bidirectional"))
      (node (ref "U11") (pin "3") (pinfunction "VCC_3") (pintype "power_in"))
      (node (ref "U17") (pin "8") (pinfunction "VCC_8") (pintype "power_in"))
      (node (ref "U3") (pin "C6") (pinfunction "VDDQ_C6") (pintype "power_in"))
      (node (ref "U3") (pin "E6") (pinfunction "VDDIO_E6") (pintype "power_in"))
      (node (ref "U3") (pin "F5") (pinfunction "VDDIO_F5") (pintype "power_in"))
      (node (ref "U3") (pin "J10") (pinfunction "VDDIO_J10") (pintype "power_in"))
      (node (ref "U3") (pin "K9") (pinfunction "VDDIO_K9") (pintype "power_in"))
      (node (ref "U3") (pin "M4") (pinfunction "VDDQ_M4") (pintype "power_in"))
      (node (ref "U3") (pin "N4") (pinfunction "VDDQ_N4") (pintype "power_in"))
      (node (ref "U3") (pin "P3") (pinfunction "VDDQ_P3") (pintype "power_in"))
      (node (ref "U3") (pin "P5") (pinfunction "VDDQ_P5") (pintype "power_in"))
      (node (ref "U5") (pin "23") (pinfunction "VCCB_23") (pintype "power_in"))
      (node (ref "U5") (pin "24") (pinfunction "VCCB_24") (pintype "power_in"))
      (node (ref "U6") (pin "31") (pinfunction "VCCA_31") (pintype "power_in"))
      (node (ref "U6") (pin "42") (pinfunction "VCCA_42") (pintype "power_in"))
      (node (ref "U7") (pin "F6") (pinfunction "SYS_VDD1_3P3V_F6") (pintype "power_in"))
      (node (ref "U7") (pin "F7") (pinfunction "SYS_VDD1_3P3V_F7") (pintype "power_in"))
      (node (ref "U7") (pin "G6") (pinfunction "SYS_VDD1_3P3V_G6") (pintype "power_in"))
      (node (ref "U7") (pin "G7") (pinfunction "SYS_VDD1_3P3V_G7") (pintype "power_in"))
      (node (ref "U8") (pin "1") (pinfunction "IN_1") (pintype "power_in"))
      (node (ref "U8") (pin "3") (pinfunction "EN_3") (pintype "input"))
      (node (ref "U9") (pin "1") (pinfunction "VCCA_1") (pintype "power_in"))
    )
    (net (code "9") (name "3.3VA") (class "Default")
      (node (ref "C18") (pin "1") (pinfunction "1_1") (pintype "passive"))
      (node (ref "C41") (pin "1") (pinfunction "1_1") (pintype "passive"))
      (node (ref "JP104") (pin "1") (pinfunction "1_1") (pintype "passive"))
      (node (ref "TP14") (pin "P$1") (pinfunction "1_P$1") (pintype "bidirectional"))
      (node (ref "TP164") (pin "P$1") (pinfunction "1_P$1") (pintype "bidirectional"))
      (node (ref "U18") (pin "5") (pinfunction "VCC_5") (pintype "power_in"))
      (node (ref "U4") (pin "5") (pinfunction "VCC_5") (pintype "bidirectional"))
      (node (ref "U7") (pin "K11") (pinfunction "SYS_RTC_1P8V_K11") (pintype "power_in"))
      (node (ref "U7") (pin "L11") (pinfunction "SYS_RTC_1P8V_L11") (pintype "power_in"))
    )
    (net (code "10") (name "5V") (class "Default")
      (node (ref "C14") (pin "1") (pinfunction "1_1") (pintype "passive"))
      (node (ref "C36") (pin "1") (pinfunction "1_1") (pintype "passive"))
      (node (ref "L1") (pin "2") (pinfunction "2_2") (pintype "passive"))
      (node (ref "R62") (pin "2") (pinfunction "2_2") (pintype "passive"))
      (node (ref "TP49") (pin "1") (pinfunction "1_1") (pintype "passive"))
      (node (ref "U15") (pin "10") (pinfunction "FB_10") (pintype "input"))
      (node (ref "U7") (pin "P10") (pinfunction "VIN_AC_P10") (pintype "power_in"))
      (node (ref "U7") (pin "R10") (pinfunction "VIN_AC_R10") (pintype "power_in"))
      (node (ref "U7") (pin "T10") (pinfunction "VIN_AC_T10") (pintype "power_in"))
    )
    (net (code "11") (name "AD0") (class "Default")
      (node (ref "R57") (pin "1") (pinfunction "1_1") (pintype "passive"))
      (node (ref "R58") (pin "2") (pinfunction "2_2") (pintype "passive"))
      (node (ref "R69") (pin "2") (pinfunction "2_2") (pintype "passive"))
      (node (ref "R70") (pin "1") (pinfunction "1_1") (pintype "passive"))
      (node (ref "U16") (pin "1") (pinfunction "AD0_1") (pintype "input"))
    )
    (net (code "12") (name "AD1") (class "Default")
      (node (ref "R55") (pin "1") (pinfunction "1_1") (pintype "passive"))
      (node (ref "R56") (pin "2") (pinfunction "2_2") (pintype "passive"))
      (node (ref "R67") (pin "2") (pinfunction "2_2") (pintype "passive"))
      (node (ref "R68") (pin "1") (pinfunction "1_1") (pintype "passive"))
      (node (ref "U16") (pin "2") (pinfunction "AD1_2") (pintype "input"))
    )
    (net (code "13") (name "AD2") (class "Default")
      (node (ref "R53") (pin "1") (pinfunction "1_1") (pintype "passive"))
      (node (ref "R54") (pin "2") (pinfunction "2_2") (pintype "passive"))
      (node (ref "R65") (pin "2") (pinfunction "2_2") (pintype "passive"))
      (node (ref "R66") (pin "1") (pinfunction "1_1") (pintype "passive"))
      (node (ref "U16") (pin "3") (pinfunction "AD2_3") (pintype "input"))
    )
    (net (code "14") (name "BOOT0") (class "Default")
      (node (ref "TP51") (pin "1") (pinfunction "1_1") (pintype "passive"))
      (node (ref "U16") (pin "10") (pinfunction "IO5_10") (pintype "bidirectional"))
    )
    (net (code "15") (name "BUS_OE") (class "Default")
      (node (ref "R11") (pin "1") (pinfunction "1_1") (pintype "passive"))
      (node (ref "TP113") (pin "P$1") (pinfunction "1_P$1") (pintype "bidirectional"))
      (node (ref "U6") (pin "25") (pinfunction "~{2OE}_25") (pintype "input"))
      (node (ref "U6") (pin "48") (pinfunction "~{1OE}_48") (pintype "input"))
      (node (ref "U7") (pin "F14") (pinfunction "MII1_CRS_F14") (pintype "bidirectional"))
    )
    (net (code "16") (name "CAM_OE") (class "Default")
      (node (ref "TP8") (pin "P$1") (pinfunction "1_P$1") (pintype "bidirectional"))
      (node (ref "U5") (pin "17") (pinfunction "B5_17") (pintype "bidirectional"))
      (node (ref "U7") (pin "F15") (pinfunction "MII1_COL_F15") (pintype "bidirectional"))
    )
    (net (code "17") (name "CAN1_H") (class "Default")
      (node (ref "J4") (pin "33") (pinfunction "33_33") (pintype "passive"))
      (node (ref "J4") (pin "34") (pinfunction "34_34") (pintype "passive"))
      (node (ref "TP184") (pin "P$1") (pinfunction "1_P$1") (pintype "bidirectional"))
    )
    (net (code "18") (name "CAN1_L") (class "Default")
      (node (ref "J4") (pin "35") (pinfunction "35_35") (pintype "passive"))
      (node (ref "J4") (pin "36") (pinfunction "36_36") (pintype "passive"))
      (node (ref "TP183") (pin "P$1") (pinfunction "1_P$1") (pintype "bidirectional"))
    )
    (net (code "19") (name "CAN2_H") (class "Default")
      (node (ref "J4") (pin "17") (pinfunction "17_17") (pintype "passive"))
      (node (ref "J4") (pin "18") (pinfunction "18_18") (pintype "passive"))
      (node (ref "U11") (pin "7") (pinfunction "CANH_7") (pintype "bidirectional"))
    )
    (net (code "20") (name "CAN2_L") (class "Default")
      (node (ref "J4") (pin "19") (pinfunction "19_19") (pintype "passive"))
      (node (ref "J4") (pin "20") (pinfunction "20_20") (pintype "passive"))
      (node (ref "U11") (pin "6") (pinfunction "CANL_6") (pintype "bidirectional"))
    )
    (net (code "21") (name "CB-RESET") (class "Default")
      (node (ref "R39") (pin "2") (pinfunction "2_2") (pintype "passive"))
      (node (ref "TP54") (pin "1") (pinfunction "1_1") (pintype "passive"))
      (node (ref "U14") (pin "9") (pinfunction "CIN2-_9") (pintype "input"))
      (node (ref "U16") (pin "9") (pinfunction "IO4_9") (pintype "bidirectional"))
    )
    (net (code "22") (name "CB_CTRL") (class "Default")
      (node (ref "Q2") (pin "1") (pinfunction "G_1") (pintype "passive"))
      (node (ref "Q5") (pin "3") (pinfunction "G_3") (pintype "passive"))
      (node (ref "R64") (pin "1") (pinfunction "1_1") (pintype "passive"))
      (node (ref "TP52") (pin "1") (pinfunction "1_1") (pintype "passive"))
      (node (ref "U14") (pin "3") (pinfunction "LE_3") (pintype "input"))
      (node (ref "U14") (pin "4") (pinfunction "COUT1_4") (pintype "open_collector"))
      (node (ref "U14") (pin "6") (pinfunction "COUT2_6") (pintype "open_collector"))
    )
    (net (code "23") (name "CLK_EN") (class "Default")
      (node (ref "TP11") (pin "P$1") (pinfunction "1_P$1") (pintype "bidirectional"))
      (node (ref "U5") (pin "20") (pinfunction "B2_20") (pintype "bidirectional"))
      (node (ref "U7") (pin "E16") (pinfunction "MII1_RX_CLK_E16") (pintype "bidirectional"))
    )
    (net (code "24") (name "CLK_EN_E") (class "Default")
      (node (ref "J101") (pin "23") (pinfunction "23_23") (pintype "passive"))
      (node (ref "U5") (pin "4") (pinfunction "A2_4") (pintype "bidirectional"))
    )
    (net (code "25") (name "D0_E") (class "Default")
      (node (ref "J101") (pin "12") (pinfunction "12_12") (pintype "passive"))
      (node (ref "U6") (pin "11") (pinfunction "1B7_11") (pintype "bidirectional"))
    )
    (net (code "26") (name "D0_I") (class "Default")
      (node (ref "JP102") (pin "1") (pinfunction "1_1") (pintype "passive"))
      (node (ref "TP19") (pin "P$1") (pinfunction "1_P$1") (pintype "bidirectional"))
      (node (ref "U6") (pin "38") (pinfunction "1A7_38") (pintype "bidirectional"))
    )
    (net (code "27") (name "D1_E") (class "Default")
      (node (ref "J101") (pin "11") (pinfunction "11_11") (pintype "passive"))
      (node (ref "U6") (pin "12") (pinfunction "1B8_12") (pintype "bidirectional"))
    )
    (net (code "28") (name "D1_I") (class "Default")
      (node (ref "JP103") (pin "1") (pinfunction "1_1") (pintype "passive"))
      (node (ref "TP21") (pin "P$1") (pinfunction "1_P$1") (pintype "bidirectional"))
      (node (ref "U6") (pin "37") (pinfunction "1A8_37") (pintype "bidirectional"))
    )
    (net (code "29") (name "D2_E") (class "Default")
      (node (ref "J101") (pin "10") (pinfunction "10_10") (pintype "passive"))
      (node (ref "U6") (pin "13") (pinfunction "2B1_13") (pintype "bidirectional"))
    )
    (net (code "30") (name "D2_I") (class "Default")
      (node (ref "JP110") (pin "1") (pinfunction "1_1") (pintype "passive"))
      (node (ref "TP24") (pin "P$1") (pinfunction "1_P$1") (pintype "bidirectional"))
      (node (ref "U6") (pin "36") (pinfunction "2A1_36") (pintype "bidirectional"))
    )
    (net (code "31") (name "D3_E") (class "Default")
      (node (ref "J101") (pin "9") (pinfunction "9_9") (pintype "passive"))
      (node (ref "U6") (pin "14") (pinfunction "2B2_14") (pintype "bidirectional"))
    )
    (net (code "32") (name "D3_I") (class "Default")
      (node (ref "JP111") (pin "1") (pinfunction "1_1") (pintype "passive"))
      (node (ref "TP23") (pin "P$1") (pinfunction "1_P$1") (pintype "bidirectional"))
      (node (ref "U6") (pin "35") (pinfunction "2A2_35") (pintype "bidirectional"))
    )
    (net (code "33") (name "D4_E") (class "Default")
      (node (ref "J101") (pin "8") (pinfunction "8_8") (pintype "passive"))
      (node (ref "U6") (pin "16") (pinfunction "2B3_16") (pintype "bidirectional"))
    )
    (net (code "34") (name "D4_I") (class "Default")
      (node (ref "TP27") (pin "P$1") (pinfunction "1_P$1") (pintype "bidirectional"))
      (node (ref "U6") (pin "33") (pinfunction "2A3_33") (pintype "bidirectional"))
      (node (ref "U7") (pin "A1") (pinfunction "MCASP0_ACLKX_A1") (pintype "bidirectional"))
    )
    (net (code "35") (name "D5_E") (class "Default")
      (node (ref "J101") (pin "7") (pinfunction "7_7") (pintype "passive"))
      (node (ref "U6") (pin "17") (pinfunction "2B4_17") (pintype "bidirectional"))
    )
    (net (code "36") (name "D5_I") (class "Default")
      (node (ref "TP26") (pin "P$1") (pinfunction "1_P$1") (pintype "bidirectional"))
      (node (ref "U6") (pin "32") (pinfunction "2A4_32") (pintype "bidirectional"))
      (node (ref "U7") (pin "A2") (pinfunction "MCASP0_FSX_A2") (pintype "bidirectional"))
    )
    (net (code "37") (name "D6_E") (class "Default")
      (node (ref "J101") (pin "6") (pinfunction "6_6") (pintype "passive"))
      (node (ref "U6") (pin "19") (pinfunction "2B5_19") (pintype "bidirectional"))
    )
    (net (code "38") (name "D6_I") (class "Default")
      (node (ref "TP29") (pin "P$1") (pinfunction "1_P$1") (pintype "bidirectional"))
      (node (ref "U6") (pin "30") (pinfunction "2A5_30") (pintype "bidirectional"))
      (node (ref "U7") (pin "B2") (pinfunction "MCASP0_AXR0_B2") (pintype "bidirectional"))
    )
    (net (code "39") (name "D7_E") (class "Default")
      (node (ref "J101") (pin "13") (pinfunction "13_13") (pintype "passive"))
      (node (ref "U6") (pin "9") (pinfunction "1B6_9") (pintype "bidirectional"))
    )
    (net (code "40") (name "D7_I") (class "Default")
      (node (ref "TP20") (pin "P$1") (pinfunction "1_P$1") (pintype "bidirectional"))
      (node (ref "U6") (pin "40") (pinfunction "1A6_40") (pintype "bidirectional"))
      (node (ref "U7") (pin "B1") (pinfunction "MCASP0_AHCLKR_B1") (pintype "bidirectional"))
    )
    (net (code "41") (name "D8_E") (class "Default")
      (node (ref "J101") (pin "14") (pinfunction "14_14") (pintype "passive"))
      (node (ref "U6") (pin "8") (pinfunction "1B5_8") (pintype "bidirectional"))
    )
    (net (code "42") (name "D8_I") (class "Default")
      (node (ref "TP17") (pin "P$1") (pinfunction "1_P$1") (pintype "bidirectional"))
      (node (ref "U6") (pin "41") (pinfunction "1A5_41") (pintype "bidirectional"))
      (node (ref "U7") (pin "A3") (pinfunction "MCASP0_ACLKR_A3") (pintype "bidirectional"))
    )
    (net (code "43") (name "D9_E") (class "Default")
      (node (ref "J101") (pin "15") (pinfunction "15_15") (pintype "passive"))
      (node (ref "U6") (pin "6") (pinfunction "1B4_6") (pintype "bidirectional"))
    )
    (net (code "44") (name "D9_I") (class "Default")
      (node (ref "TP18") (pin "P$1") (pinfunction "1_P$1") (pintype "bidirectional"))
      (node (ref "U6") (pin "43") (pinfunction "1A4_43") (pintype "bidirectional"))
      (node (ref "U7") (pin "B3") (pinfunction "MCASP0_FSR_B3") (pintype "bidirectional"))
    )
    (net (code "45") (name "D10_E") (class "Default")
      (node (ref "J101") (pin "16") (pinfunction "16_16") (pintype "passive"))
      (node (ref "U6") (pin "5") (pinfunction "1B3_5") (pintype "bidirectional"))
    )
    (net (code "46") (name "D10_I") (class "Default")
      (node (ref "TP15") (pin "P$1") (pinfunction "1_P$1") (pintype "bidirectional"))
      (node (ref "U6") (pin "44") (pinfunction "1A3_44") (pintype "bidirectional"))
      (node (ref "U7") (pin "C3") (pinfunction "MCASP0_AXR1_C3") (pintype "bidirectional"))
    )
    (net (code "47") (name "D11_E") (class "Default")
      (node (ref "J101") (pin "17") (pinfunction "17_17") (pintype "passive"))
      (node (ref "U6") (pin "3") (pinfunction "1B2_3") (pintype "bidirectional"))
    )
    (net (code "48") (name "D11_I") (class "Default")
      (node (ref "TP16") (pin "P$1") (pinfunction "1_P$1") (pintype "bidirectional"))
      (node (ref "U6") (pin "46") (pinfunction "1A2_46") (pintype "bidirectional"))
      (node (ref "U7") (pin "C4") (pinfunction "MCASP0_AHCLKX_C4") (pintype "bidirectional"))
    )
    (net (code "49") (name "EEPROM_WP") (class "Default")
      (node (ref "J1") (pin "20") (pinfunction "DEBUG-3_20") (pintype "passive"))
      (node (ref "R75") (pin "1") (pinfunction "1_1") (pintype "passive"))
      (node (ref "TP112") (pin "P$1") (pinfunction "1_P$1") (pintype "bidirectional"))
      (node (ref "U18") (pin "6") (pinfunction "I4_6") (pintype "bidirectional"))
    )
    (net (code "50") (name "FLASH") (class "Default")
      (node (ref "TP13") (pin "P$1") (pinfunction "1_P$1") (pintype "bidirectional"))
      (node (ref "U6") (pin "47") (pinfunction "1A1_47") (pintype "bidirectional"))
      (node (ref "U7") (pin "G15") (pinfunction "MII1_TXD3_G15") (pintype "bidirectional"))
    )
    (net (code "51") (name "FLASH_E") (class "Default")
      (node (ref "J101") (pin "28") (pinfunction "28_28") (pintype "passive"))
      (node (ref "U6") (pin "2") (pinfunction "1B1_2") (pintype "bidirectional"))
    )
    (net (code "52") (name "GND") (class "Default")
      (node (ref "C1") (pin "2") (pinfunction "2_2") (pintype "passive"))
      (node (ref "C10") (pin "2") (pinfunction "2_2") (pintype "passive"))
      (node (ref "C11") (pin "2") (pinfunction "2_2") (pintype "passive"))
      (node (ref "C12") (pin "2") (pinfunction "2_2") (pintype "passive"))
      (node (ref "C13") (pin "2") (pinfunction "2_2") (pintype "passive"))
      (node (ref "C14") (pin "2") (pinfunction "2_2") (pintype "passive"))
      (node (ref "C15") (pin "2") (pinfunction "2_2") (pintype "passive"))
      (node (ref "C16") (pin "2") (pinfunction "2_2") (pintype "passive"))
      (node (ref "C17") (pin "2") (pinfunction "2_2") (pintype "passive"))
      (node (ref "C18") (pin "2") (pinfunction "2_2") (pintype "passive"))
      (node (ref "C2") (pin "2") (pinfunction "2_2") (pintype "passive"))
      (node (ref "C20") (pin "2") (pinfunction "2_2") (pintype "passive"))
      (node (ref "C21") (pin "2") (pinfunction "2_2") (pintype "passive"))
      (node (ref "C23") (pin "2") (pinfunction "2_2") (pintype "passive"))
      (node (ref "C24") (pin "2") (pinfunction "2_2") (pintype "passive"))
      (node (ref "C25") (pin "2") (pinfunction "2_2") (pintype "passive"))
      (node (ref "C26") (pin "2") (pinfunction "2_2") (pintype "passive"))
      (node (ref "C27") (pin "2") (pinfunction "2_2") (pintype "passive"))
      (node (ref "C28") (pin "2") (pinfunction "2_2") (pintype "passive"))
      (node (ref "C3") (pin "2") (pinfunction "2_2") (pintype "passive"))
      (node (ref "C31") (pin "1") (pinfunction "1_1") (pintype "passive"))
      (node (ref "C32") (pin "2") (pinfunction "2_2") (pintype "passive"))
      (node (ref "C34") (pin "2") (pinfunction "2_2") (pintype "passive"))
      (node (ref "C35") (pin "2") (pinfunction "2_2") (pintype "passive"))
      (node (ref "C36") (pin "2") (pinfunction "2_2") (pintype "passive"))
      (node (ref "C37") (pin "2") (pinfunction "2_2") (pintype "passive"))
      (node (ref "C38") (pin "2") (pinfunction "2_2") (pintype "passive"))
      (node (ref "C39") (pin "1") (pinfunction "1_1") (pintype "passive"))
      (node (ref "C4") (pin "2") (pinfunction "2_2") (pintype "passive"))
      (node (ref "C40") (pin "1") (pinfunction "1_1") (pintype "passive"))
      (node (ref "C41") (pin "2") (pinfunction "2_2") (pintype "passive"))
      (node (ref "C42") (pin "2") (pinfunction "2_2") (pintype "passive"))
      (node (ref "C43") (pin "2") (pinfunction "2_2") (pintype "passive"))
      (node (ref "C44") (pin "2") (pinfunction "2_2") (pintype "passive"))
      (node (ref "C5") (pin "2") (pinfunction "2_2") (pintype "passive"))
      (node (ref "C6") (pin "2") (pinfunction "2_2") (pintype "passive"))
      (node (ref "C7") (pin "2") (pinfunction "2_2") (pintype "passive"))
      (node (ref "C8") (pin "2") (pinfunction "2_2") (pintype "passive"))
      (node (ref "C9") (pin "2") (pinfunction "2_2") (pintype "passive"))
      (node (ref "D1") (pin "C") (pinfunction "C_C") (pintype "passive"))
      (node (ref "D2") (pin "C") (pinfunction "C_C") (pintype "passive"))
      (node (ref "D3") (pin "C") (pinfunction "C_C") (pintype "passive"))
      (node (ref "D4") (pin "C") (pinfunction "C_C") (pintype "passive"))
      (node (ref "D5") (pin "C") (pinfunction "C_C") (pintype "passive"))
      (node (ref "D6") (pin "C") (pinfunction "C_C") (pintype "passive"))
      (node (ref "D7") (pin "C") (pinfunction "C_C") (pintype "passive"))
      (node (ref "D8") (pin "C") (pinfunction "C_C") (pintype "passive"))
      (node (ref "J1") (pin "3") (pinfunction "GND_3") (pintype "passive"))
      (node (ref "J1") (pin "6") (pinfunction "GND_6") (pintype "passive"))
      (node (ref "J1") (pin "9") (pinfunction "GND_9") (pintype "passive"))
      (node (ref "J1") (pin "PAD1") (pinfunction "PAD_PAD1") (pintype "bidirectional"))
      (node (ref "J1") (pin "PAD2") (pinfunction "PAD_PAD2") (pintype "bidirectional"))
      (node (ref "J100") (pin "6") (pinfunction "VSS_6") (pintype "bidirectional"))
      (node (ref "J100") (pin "CGND1") (pinfunction "CGND_CGND1") (pintype "bidirectional"))
      (node (ref "J100") (pin "CGND2") (pinfunction "CGND_CGND2") (pintype "bidirectional"))
      (node (ref "J100") (pin "CGND3") (pinfunction "CGND_CGND3") (pintype "bidirectional"))
      (node (ref "J100") (pin "CGND4") (pinfunction "CGND_CGND4") (pintype "bidirectional"))
      (node (ref "J100") (pin "CGND5") (pinfunction "CGND_CGND5") (pintype "bidirectional"))
      (node (ref "J100") (pin "CGND6") (pinfunction "CGND_CGND6") (pintype "bidirectional"))
      (node (ref "J100") (pin "GND") (pinfunction "VSS_GND") (pintype "bidirectional"))
      (node (ref "J101") (pin "1") (pinfunction "1_1") (pintype "passive"))
      (node (ref "J101") (pin "18") (pinfunction "18_18") (pintype "passive"))
      (node (ref "J101") (pin "19") (pinfunction "19_19") (pintype "passive"))
      (node (ref "J101") (pin "2") (pinfunction "2_2") (pintype "passive"))
      (node (ref "J101") (pin "20") (pinfunction "20_20") (pintype "passive"))
      (node (ref "J101") (pin "34") (pinfunction "34_34") (pintype "passive"))
      (node (ref "J101") (pin "35") (pinfunction "35_35") (pintype "passive"))
      (node (ref "J101") (pin "36") (pinfunction "36_36") (pintype "passive"))
      (node (ref "J101") (pin "S1") (pinfunction "PAD_S1") (pintype "bidirectional"))
      (node (ref "J101") (pin "S2") (pinfunction "PAD_S2") (pintype "bidirectional"))
      (node (ref "J102") (pin "3") (pinfunction "GND_3") (pintype "passive"))
      (node (ref "J102") (pin "5") (pinfunction "GND_5") (pintype "passive"))
      (node (ref "J102") (pin "9") (pinfunction "GNDDET_9") (pintype "passive"))
      (node (ref "J4") (pin "27") (pinfunction "27_27") (pintype "passive"))
      (node (ref "J4") (pin "28") (pinfunction "28_28") (pintype "passive"))
      (node (ref "J4") (pin "29") (pinfunction "29_29") (pintype "passive"))
      (node (ref "J4") (pin "30") (pinfunction "30_30") (pintype "passive"))
      (node (ref "J4") (pin "31") (pinfunction "31_31") (pintype "passive"))
      (node (ref "J4") (pin "32") (pinfunction "32_32") (pintype "passive"))
      (node (ref "J4") (pin "37") (pinfunction "37_37") (pintype "passive"))
      (node (ref "J4") (pin "38") (pinfunction "38_38") (pintype "passive"))
      (node (ref "JP100") (pin "2") (pinfunction "2_2") (pintype "passive"))
      (node (ref "Q2") (pin "2") (pinfunction "S_2") (pintype "passive"))
      (node (ref "Q4") (pin "2") (pinfunction "S_2") (pintype "passive"))
      (node (ref "R14") (pin "2") (pinfunction "2_2") (pintype "passive"))
      (node (ref "R15") (pin "1") (pinfunction "1_1") (pintype "passive"))
      (node (ref "R16") (pin "2") (pinfunction "2_2") (pintype "passive"))
      (node (ref "R19") (pin "1") (pinfunction "1_1") (pintype "passive"))
      (node (ref "R25") (pin "10") (pinfunction "55_10") (pintype "passive"))
      (node (ref "R25") (pin "5") (pinfunction "55_5") (pintype "passive"))
      (node (ref "R26") (pin "10") (pinfunction "55_10") (pintype "passive"))
      (node (ref "R26") (pin "5") (pinfunction "55_5") (pintype "passive"))
      (node (ref "R33") (pin "1") (pinfunction "1_1") (pintype "passive"))
      (node (ref "R39") (pin "1") (pinfunction "1_1") (pintype "passive"))
      (node (ref "R40") (pin "1") (pinfunction "1_1") (pintype "passive"))
      (node (ref "R42") (pin "1") (pinfunction "1_1") (pintype "passive"))
      (node (ref "R46") (pin "1") (pinfunction "1_1") (pintype "passive"))
      (node (ref "R51") (pin "1") (pinfunction "1_1") (pintype "passive"))
      (node (ref "R54") (pin "1") (pinfunction "1_1") (pintype "passive"))
      (node (ref "R56") (pin "1") (pinfunction "1_1") (pintype "passive"))
      (node (ref "R58") (pin "1") (pinfunction "1_1") (pintype "passive"))
      (node (ref "R59") (pin "2") (pinfunction "2_2") (pintype "passive"))
      (node (ref "R6") (pin "1") (pinfunction "1_1") (pintype "passive"))
      (node (ref "U1") (pin "2") (pinfunction "GND_2") (pintype "power_in"))
      (node (ref "U11") (pin "2") (pinfunction "GND_2") (pintype "power_in"))
      (node (ref "U12") (pin "2") (pinfunction "GND_2") (pintype "power_in"))
      (node (ref "U13") (pin "2") (pinfunction "GND_2") (pintype "power_in"))
      (node (ref "U14") (pin "7") (pinfunction "GND_7") (pintype "power_in"))
      (node (ref "U14") (pin "EPAD") (pinfunction "GND_EPAD") (pintype "power_in"))
      (node (ref "U15") (pin "1") (pinfunction "GND_1") (pintype "power_in"))
      (node (ref "U15") (pin "11") (pinfunction "GND_11") (pintype "power_in"))
      (node (ref "U15") (pin "12") (pinfunction "GND_12") (pintype "power_in"))
      (node (ref "U15") (pin "16") (pinfunction "GND_16") (pintype "power_in"))
      (node (ref "U15") (pin "6") (pinfunction "LBO_6") (pintype "open_collector"))
      (node (ref "U15") (pin "7") (pinfunction "LBI_7") (pintype "input"))
      (node (ref "U15") (pin "9") (pinfunction "GND_9") (pintype "power_in"))
      (node (ref "U15") (pin "PAD") (pinfunction "GND_PAD") (pintype "power_in"))
      (node (ref "U16") (pin "6") (pinfunction "GND_6") (pintype "power_in"))
      (node (ref "U16") (pin "EPAD") (pinfunction "GND_EPAD") (pintype "power_in"))
      (node (ref "U17") (pin "4") (pinfunction "GND_4") (pintype "power_in"))
      (node (ref "U18") (pin "2") (pinfunction "GND_2") (pintype "power_in"))
      (node (ref "U2") (pin "2") (pinfunction "GND_2") (pintype "power_in"))
      (node (ref "U3") (pin "C4") (pinfunction "VSSQ_C4") (pintype "power_in"))
      (node (ref "U3") (pin "E7") (pinfunction "VSSIO_E7") (pintype "power_in"))
      (node (ref "U3") (pin "G5") (pinfunction "VSSIO_G5") (pintype "power_in"))
      (node (ref "U3") (pin "H10") (pinfunction "VSSIO_H10") (pintype "power_in"))
      (node (ref "U3") (pin "J5") (pinfunction "VSSIO_J5") (pintype "power_in"))
      (node (ref "U3") (pin "K8") (pinfunction "VSSIO_K8") (pintype "power_in"))
      (node (ref "U3") (pin "N2") (pinfunction "VSSQ_N2") (pintype "power_in"))
      (node (ref "U3") (pin "N5") (pinfunction "VSSQ_N5") (pintype "power_in"))
      (node (ref "U3") (pin "P4") (pinfunction "VSSQ_P4") (pintype "power_in"))
      (node (ref "U3") (pin "P6") (pinfunction "VSSQ_P6") (pintype "power_in"))
      (node (ref "U4") (pin "3") (pinfunction "GND_3") (pintype "bidirectional"))
      (node (ref "U5") (pin "11") (pinfunction "GND_11") (pintype "power_in"))
      (node (ref "U5") (pin "12") (pinfunction "GND_12") (pintype "power_in"))
      (node (ref "U5") (pin "13") (pinfunction "GND_13") (pintype "power_in"))
      (node (ref "U6") (pin "10") (pinfunction "GND_10") (pintype "power_in"))
      (node (ref "U6") (pin "15") (pinfunction "GND_15") (pintype "power_in"))
      (node (ref "U6") (pin "21") (pinfunction "GND_21") (pintype "power_in"))
      (node (ref "U6") (pin "28") (pinfunction "GND_28") (pintype "power_in"))
      (node (ref "U6") (pin "34") (pinfunction "GND_34") (pintype "power_in"))
      (node (ref "U6") (pin "39") (pinfunction "GND_39") (pintype "power_in"))
      (node (ref "U6") (pin "4") (pinfunction "GND_4") (pintype "power_in"))
      (node (ref "U6") (pin "45") (pinfunction "GND_45") (pintype "power_in"))
      (node (ref "U7") (pin "D8") (pinfunction "DGND_D8") (pintype "bidirectional"))
      (node (ref "U7") (pin "D9") (pinfunction "DGND_D9") (pintype "bidirectional"))
      (node (ref "U7") (pin "E10") (pinfunction "DGND_E10") (pintype "bidirectional"))
      (node (ref "U7") (pin "E11") (pinfunction "DGND_E11") (pintype "bidirectional"))
      (node (ref "U7") (pin "E12") (pinfunction "DGND_E12") (pintype "bidirectional"))
      (node (ref "U7") (pin "E5") (pinfunction "DGND_E5") (pintype "bidirectional"))
      (node (ref "U7") (pin "E6") (pinfunction "DGND_E6") (pintype "bidirectional"))
      (node (ref "U7") (pin "E7") (pinfunction "DGND_E7") (pintype "bidirectional"))
      (node (ref "U7") (pin "E8") (pinfunction "DGND_E8") (pintype "bidirectional"))
      (node (ref "U7") (pin "E9") (pinfunction "DGND_E9") (pintype "bidirectional"))
      (node (ref "U7") (pin "F12") (pinfunction "DGND_F12") (pintype "bidirectional"))
      (node (ref "U7") (pin "F5") (pinfunction "DGND_F5") (pintype "bidirectional"))
      (node (ref "U7") (pin "G12") (pinfunction "DGND_G12") (pintype "bidirectional"))
      (node (ref "U7") (pin "G5") (pinfunction "DGND_G5") (pintype "bidirectional"))
      (node (ref "U7") (pin "H12") (pinfunction "DGND_H12") (pintype "bidirectional"))
      (node (ref "U7") (pin "H13") (pinfunction "DGND_H13") (pintype "bidirectional"))
      (node (ref "U7") (pin "H4") (pinfunction "DGND_H4") (pintype "bidirectional"))
      (node (ref "U7") (pin "H5") (pinfunction "DGND_H5") (pintype "bidirectional"))
      (node (ref "U7") (pin "J12") (pinfunction "DGND_J12") (pintype "bidirectional"))
      (node (ref "U7") (pin "J13") (pinfunction "DGND_J13") (pintype "bidirectional"))
      (node (ref "U7") (pin "J4") (pinfunction "DGND_J4") (pintype "bidirectional"))
      (node (ref "U7") (pin "J5") (pinfunction "DGND_J5") (pintype "bidirectional"))
      (node (ref "U7") (pin "K12") (pinfunction "DGND_K12") (pintype "bidirectional"))
      (node (ref "U7") (pin "K5") (pinfunction "DGND_K5") (pintype "bidirectional"))
      (node (ref "U7") (pin "L12") (pinfunction "DGND_L12") (pintype "bidirectional"))
      (node (ref "U7") (pin "L5") (pinfunction "DGND_L5") (pintype "bidirectional"))
      (node (ref "U7") (pin "M10") (pinfunction "DGND_M10") (pintype "bidirectional"))
      (node (ref "U7") (pin "M11") (pinfunction "DGND_M11") (pintype "bidirectional"))
      (node (ref "U7") (pin "M12") (pinfunction "DGND_M12") (pintype "bidirectional"))
      (node (ref "U7") (pin "M5") (pinfunction "DGND_M5") (pintype "bidirectional"))
      (node (ref "U7") (pin "M6") (pinfunction "DGND_M6") (pintype "bidirectional"))
      (node (ref "U7") (pin "M7") (pinfunction "DGND_M7") (pintype "bidirectional"))
      (node (ref "U7") (pin "M8") (pinfunction "DGND_M8") (pintype "bidirectional"))
      (node (ref "U7") (pin "M9") (pinfunction "DGND_M9") (pintype "bidirectional"))
      (node (ref "U7") (pin "N8") (pinfunction "DGND_N8") (pintype "bidirectional"))
      (node (ref "U7") (pin "N9") (pinfunction "DGND_N9") (pintype "bidirectional"))
      (node (ref "U8") (pin "2") (pinfunction "GND_2") (pintype "power_in"))
      (node (ref "U9") (pin "4") (pinfunction "GND_4") (pintype "power_in"))
      (node (ref "Y1") (pin "2") (pinfunction "GND_2") (pintype "power_in"))
      (node (ref "Y1") (pin "4") (pinfunction "GND_4") (pintype "power_in"))
    )
    (net (code "53") (name "HSYNC_E") (class "Default")
      (node (ref "J101") (pin "4") (pinfunction "4_4") (pintype "passive"))
      (node (ref "U6") (pin "22") (pinfunction "2B7_22") (pintype "bidirectional"))
    )
    (net (code "54") (name "HSYNC_I") (class "Default")
      (node (ref "TP119") (pin "P$1") (pinfunction "1_P$1") (pintype "bidirectional"))
      (node (ref "U6") (pin "27") (pinfunction "2A7_27") (pintype "bidirectional"))
      (node (ref "U7") (pin "P7") (pinfunction "GPMC_AD15_P7") (pintype "bidirectional"))
    )
    (net (code "55") (name "I2C0_SCL") (class "Default")
      (node (ref "J1") (pin "18") (pinfunction "DEBUG-1_18") (pintype "passive"))
      (node (ref "R73") (pin "1") (pinfunction "1_1") (pintype "passive"))
      (node (ref "TP155") (pin "P$1") (pinfunction "1_P$1") (pintype "bidirectional"))
      (node (ref "U18") (pin "3") (pinfunction "I2_3") (pintype "bidirectional"))
    )
    (net (code "56") (name "I2C0_SDA") (class "Default")
      (node (ref "J1") (pin "19") (pinfunction "DEBUG-2_19") (pintype "passive"))
      (node (ref "R74") (pin "1") (pinfunction "1_1") (pintype "passive"))
      (node (ref "TP151") (pin "P$1") (pinfunction "1_P$1") (pintype "bidirectional"))
      (node (ref "U18") (pin "1") (pinfunction "I1_1") (pintype "bidirectional"))
    )
    (net (code "57") (name "I2C2_SCL") (class "Default")
      (node (ref "J101") (pin "21") (pinfunction "21_21") (pintype "passive"))
      (node (ref "R17") (pin "2") (pinfunction "2_2") (pintype "passive"))
      (node (ref "U9") (pin "7") (pinfunction "SCLB_7") (pintype "bidirectional"))
    )
    (net (code "58") (name "I2C2_SDA") (class "Default")
      (node (ref "J101") (pin "22") (pinfunction "22_22") (pintype "passive"))
      (node (ref "R18") (pin "2") (pinfunction "2_2") (pintype "passive"))
      (node (ref "U9") (pin "6") (pinfunction "SDAB_6") (pintype "bidirectional"))
    )
    (net (code "59") (name "INPUT_EN") (class "Default")
      (node (ref "R12") (pin "1") (pinfunction "1_1") (pintype "passive"))
      (node (ref "TP12") (pin "P$1") (pinfunction "1_P$1") (pintype "bidirectional"))
      (node (ref "U5") (pin "22") (pinfunction "~{OE}_22") (pintype "input"))
      (node (ref "U7") (pin "E14") (pinfunction "MII1_RXD0_E14") (pintype "bidirectional"))
    )
    (net (code "60") (name "N$103") (class "Default")
      (node (ref "J4") (pin "1") (pinfunction "1_1") (pintype "passive"))
      (node (ref "J4") (pin "2") (pinfunction "2_2") (pintype "passive"))
      (node (ref "TP62") (pin "P$1") (pinfunction "1_P$1") (pintype "bidirectional"))
    )
    (net (code "61") (name "Net-(C33-Pad1)") (class "Default")
      (node (ref "C33") (pin "1") (pinfunction "1_1") (pintype "passive"))
      (node (ref "R33") (pin "2") (pinfunction "2_2") (pintype "passive"))
      (node (ref "R38") (pin "2") (pinfunction "2_2") (pintype "passive"))
    )
    (net (code "62") (name "Net-(D1-PadA)") (class "Default")
      (node (ref "D1") (pin "A") (pinfunction "A_A") (pintype "passive"))
      (node (ref "R1") (pin "2") (pinfunction "2_2") (pintype "passive"))
    )
    (net (code "63") (name "Net-(D2-PadA)") (class "Default")
      (node (ref "D2") (pin "A") (pinfunction "A_A") (pintype "passive"))
      (node (ref "R2") (pin "2") (pinfunction "2_2") (pintype "passive"))
    )
    (net (code "64") (name "Net-(D3-PadA)") (class "Default")
      (node (ref "D3") (pin "A") (pinfunction "A_A") (pintype "passive"))
      (node (ref "R3") (pin "2") (pinfunction "2_2") (pintype "passive"))
    )
    (net (code "65") (name "Net-(D4-PadA)") (class "Default")
      (node (ref "D4") (pin "A") (pinfunction "A_A") (pintype "passive"))
      (node (ref "R4") (pin "2") (pinfunction "2_2") (pintype "passive"))
    )
    (net (code "66") (name "Net-(D5-PadA)") (class "Default")
      (node (ref "D5") (pin "A") (pinfunction "A_A") (pintype "passive"))
      (node (ref "R5") (pin "2") (pinfunction "2_2") (pintype "passive"))
    )
    (net (code "67") (name "Net-(D6-PadA)") (class "Default")
      (node (ref "D6") (pin "A") (pinfunction "A_A") (pintype "passive"))
      (node (ref "R49") (pin "1") (pinfunction "1_1") (pintype "passive"))
    )
    (net (code "68") (name "Net-(D7-PadA)") (class "Default")
      (node (ref "D7") (pin "A") (pinfunction "A_A") (pintype "passive"))
      (node (ref "R61") (pin "1") (pinfunction "1_1") (pintype "passive"))
    )
    (net (code "69") (name "Net-(D8-PadA)") (class "Default")
      (node (ref "D8") (pin "A") (pinfunction "A_A") (pintype "passive"))
      (node (ref "R62") (pin "1") (pinfunction "1_1") (pintype "passive"))
    )
    (net (code "70") (name "Net-(J100-CD#)") (class "Default")
      (node (ref "J100") (pin "CD") (pinfunction "CD#_CD") (pintype "bidirectional"))
      (node (ref "R8") (pin "6") (pinfunction "66_6") (pintype "passive"))
      (node (ref "TP22") (pin "P$1") (pinfunction "1_P$1") (pintype "bidirectional"))
      (node (ref "U7") (pin "C14") (pinfunction "SPI0_CS1_C14") (pintype "bidirectional"))
    )
    (net (code "71") (name "Net-(J100-CLK)") (class "Default")
      (node (ref "J100") (pin "5") (pinfunction "CLK_5") (pintype "bidirectional"))
      (node (ref "R8") (pin "3") (pinfunction "33_3") (pintype "passive"))
      (node (ref "U7") (pin "B15") (pinfunction "MMC0_CLK_B15") (pintype "bidirectional"))
    )
    (net (code "72") (name "Net-(J100-CMD{slash}DI)") (class "Default")
      (node (ref "J100") (pin "3") (pinfunction "CMD/DI_3") (pintype "bidirectional"))
      (node (ref "R8") (pin "8") (pinfunction "88_8") (pintype "passive"))
      (node (ref "U7") (pin "B16") (pinfunction "MMC0_CMD_B16") (pintype "bidirectional"))
    )
    (net (code "73") (name "Net-(J100-DAT0{slash}DO)") (class "Default")
      (node (ref "J100") (pin "7") (pinfunction "DAT0/DO_7") (pintype "bidirectional"))
      (node (ref "JP111") (pin "3") (pinfunction "3_3") (pintype "passive"))
      (node (ref "R8") (pin "7") (pinfunction "77_7") (pintype "passive"))
    )
    (net (code "74") (name "Net-(J100-DAT1)") (class "Default")
      (node (ref "J100") (pin "8") (pinfunction "DAT1_8") (pintype "bidirectional"))
      (node (ref "JP110") (pin "3") (pinfunction "3_3") (pintype "passive"))
      (node (ref "R8") (pin "4") (pinfunction "44_4") (pintype "passive"))
    )
    (net (code "75") (name "Net-(J100-DAT2)") (class "Default")
      (node (ref "J100") (pin "1") (pinfunction "DAT2_1") (pintype "bidirectional"))
      (node (ref "JP103") (pin "3") (pinfunction "3_3") (pintype "passive"))
      (node (ref "R8") (pin "9") (pinfunction "99_9") (pintype "passive"))
    )
    (net (code "76") (name "Net-(J100-DAT3{slash}CS)") (class "Default")
      (node (ref "J100") (pin "2") (pinfunction "DAT3/CS_2") (pintype "bidirectional"))
      (node (ref "JP102") (pin "3") (pinfunction "3_3") (pintype "passive"))
      (node (ref "R8") (pin "2") (pinfunction "22_2") (pintype "passive"))
    )
    (net (code "77") (name "Net-(J102-NC{slash}TDI)") (class "Default")
      (node (ref "J102") (pin "8") (pinfunction "NC/TDI_8") (pintype "passive"))
      (node (ref "U7") (pin "C1") (pinfunction "TDI_C1") (pintype "bidirectional"))
    )
    (net (code "78") (name "Net-(J102-SWDCLK{slash}TCK)") (class "Default")
      (node (ref "J102") (pin "4") (pinfunction "SWDCLK/TCK_4") (pintype "passive"))
      (node (ref "U7") (pin "D1") (pinfunction "TCK_D1") (pintype "bidirectional"))
    )
    (net (code "79") (name "Net-(J102-SWDIO{slash}TMS)") (class "Default")
      (node (ref "J102") (pin "2") (pinfunction "SWDIO/TMS_2") (pintype "passive"))
      (node (ref "U7") (pin "D2") (pinfunction "TMS_D2") (pintype "bidirectional"))
    )
    (net (code "80") (name "Net-(J102-SWO{slash}TDO)") (class "Default")
      (node (ref "J102") (pin "6") (pinfunction "SWO/TDO_6") (pintype "passive"))
      (node (ref "U7") (pin "C2") (pinfunction "TDO_C2") (pintype "bidirectional"))
    )
    (net (code "81") (name "Net-(J102-~{RESET})") (class "Default")
      (node (ref "J102") (pin "10") (pinfunction "~{RESET}_10") (pintype "passive"))
      (node (ref "JP1") (pin "2") (pinfunction "2_2") (pintype "passive"))
    )
    (net (code "82") (name "Net-(JP101-Pad2)") (class "Default")
      (node (ref "JP101") (pin "2") (pinfunction "2_2") (pintype "passive"))
      (node (ref "Q1") (pin "E") (pinfunction "E_E") (pintype "passive"))
      (node (ref "R23") (pin "2") (pinfunction "2_2") (pintype "passive"))
      (node (ref "R28") (pin "2") (pinfunction "2_2") (pintype "passive"))
    )
    (net (code "83") (name "Net-(L1-Pad1)") (class "Default")
      (node (ref "L1") (pin "1") (pinfunction "1_1") (pintype "passive"))
      (node (ref "U15") (pin "14") (pinfunction "SW_14") (pintype "output"))
      (node (ref "U15") (pin "15") (pinfunction "SW_15") (pintype "output"))
    )
    (net (code "84") (name "Net-(Q3A-G)") (class "Default")
      (node (ref "Q3") (pin "1") (pinfunction "G_1") (pintype "passive"))
      (node (ref "R35") (pin "2") (pinfunction "2_2") (pintype "passive"))
    )
    (net (code "85") (name "Net-(Q3A-S)") (class "Default")
      (node (ref "Q3") (pin "5") (pinfunction "S_5") (pintype "passive"))
      (node (ref "R48") (pin "2") (pinfunction "2_2") (pintype "passive"))
    )
    (net (code "86") (name "Net-(Q3B-G)") (class "Default")
      (node (ref "Q3") (pin "3") (pinfunction "G_3") (pintype "passive"))
      (node (ref "R43") (pin "2") (pinfunction "2_2") (pintype "passive"))
    )
    (net (code "87") (name "Net-(Q3B-S)") (class "Default")
      (node (ref "Q3") (pin "2") (pinfunction "S_2") (pintype "passive"))
      (node (ref "R41") (pin "2") (pinfunction "2_2") (pintype "passive"))
    )
    (net (code "88") (name "Net-(Q4-D)") (class "Default")
      (node (ref "Q4") (pin "3") (pinfunction "D_3") (pintype "passive"))
      (node (ref "Q6") (pin "3") (pinfunction "G_3") (pintype "passive"))
      (node (ref "R52") (pin "1") (pinfunction "1_1") (pintype "passive"))
    )
    (net (code "89") (name "Net-(Q5-S)") (class "Default")
      (node (ref "Q5") (pin "4") (pinfunction "S_4") (pintype "passive"))
      (node (ref "R63") (pin "2") (pinfunction "2_2") (pintype "passive"))
      (node (ref "R64") (pin "2") (pinfunction "2_2") (pintype "passive"))
      (node (ref "U14") (pin "15") (pinfunction "RS-_15") (pintype "passive"))
    )
    (net (code "90") (name "Net-(R9-22)") (class "Default")
      (node (ref "R9") (pin "2") (pinfunction "22_2") (pintype "passive"))
      (node (ref "U3") (pin "M5") (pinfunction "CMD_M5") (pintype "input"))
      (node (ref "U7") (pin "P1") (pinfunction "GPMC_CSN2_P1") (pintype "bidirectional"))
    )
    (net (code "91") (name "Net-(R9-33)") (class "Default")
      (node (ref "R9") (pin "3") (pinfunction "33_3") (pintype "passive"))
      (node (ref "U3") (pin "B4") (pinfunction "D5_B4") (pintype "input"))
      (node (ref "U7") (pin "T1") (pinfunction "GPMC_AD5_T1") (pintype "bidirectional"))
    )
    (net (code "92") (name "Net-(R9-44)") (class "Default")
      (node (ref "R9") (pin "4") (pinfunction "44_4") (pintype "passive"))
      (node (ref "U3") (pin "B3") (pinfunction "D4_B3") (pintype "input"))
      (node (ref "U7") (pin "T2") (pinfunction "GPMC_AD4_T2") (pintype "bidirectional"))
    )
    (net (code "93") (name "Net-(R9-66)") (class "Default")
      (node (ref "R9") (pin "6") (pinfunction "66_6") (pintype "passive"))
      (node (ref "U3") (pin "A3") (pinfunction "D0_A3") (pintype "input"))
      (node (ref "U7") (pin "R3") (pinfunction "GPMC_AD0_R3") (pintype "bidirectional"))
    )
    (net (code "94") (name "Net-(R9-77)") (class "Default")
      (node (ref "R9") (pin "7") (pinfunction "77_7") (pintype "passive"))
      (node (ref "U3") (pin "B2") (pinfunction "D3_B2") (pintype "input"))
      (node (ref "U7") (pin "T3") (pinfunction "GPMC_AD3_T3") (pintype "bidirectional"))
    )
    (net (code "95") (name "Net-(R9-88)") (class "Default")
      (node (ref "R9") (pin "8") (pinfunction "88_8") (pintype "passive"))
      (node (ref "U3") (pin "M6") (pinfunction "SCK_M6") (pintype "input"))
      (node (ref "U7") (pin "P2") (pinfunction "GPMC_CSN1_P2") (pintype "bidirectional"))
    )
    (net (code "96") (name "Net-(R10-11)") (class "Default")
      (node (ref "R10") (pin "1") (pinfunction "11_1") (pintype "passive"))
      (node (ref "U3") (pin "A4") (pinfunction "D1_A4") (pintype "input"))
      (node (ref "U7") (pin "R2") (pinfunction "GPMC_AD1_R2") (pintype "bidirectional"))
    )
    (net (code "97") (name "Net-(R10-22)") (class "Default")
      (node (ref "R10") (pin "2") (pinfunction "22_2") (pintype "passive"))
      (node (ref "U3") (pin "B6") (pinfunction "D7_B6") (pintype "input"))
      (node (ref "U7") (pin "R4") (pinfunction "GPMC_AD7_R4") (pintype "bidirectional"))
    )
    (net (code "98") (name "Net-(R10-33)") (class "Default")
      (node (ref "R10") (pin "3") (pinfunction "33_3") (pintype "passive"))
      (node (ref "U3") (pin "K5") (pinfunction "~{RST}_K5") (pintype "input"))
      (node (ref "U7") (pin "R13") (pinfunction "GPMC_A4_R13") (pintype "bidirectional"))
    )
    (net (code "99") (name "Net-(R10-88)") (class "Default")
      (node (ref "R10") (pin "8") (pinfunction "88_8") (pintype "passive"))
      (node (ref "U3") (pin "B5") (pinfunction "D6_B5") (pintype "bidirectional"))
      (node (ref "U7") (pin "P4") (pinfunction "GPMC_AD6_P4") (pintype "bidirectional"))
    )
    (net (code "100") (name "Net-(R10-99)") (class "Default")
      (node (ref "R10") (pin "9") (pinfunction "99_9") (pintype "passive"))
      (node (ref "U3") (pin "A5") (pinfunction "D2_A5") (pintype "input"))
      (node (ref "U7") (pin "R1") (pinfunction "GPMC_AD2_R1") (pintype "bidirectional"))
    )
    (net (code "101") (name "Net-(R24-22)") (class "Default")
      (node (ref "JP106") (pin "1") (pinfunction "1_1") (pintype "passive"))
      (node (ref "R24") (pin "2") (pinfunction "22_2") (pintype "passive"))
    )
    (net (code "102") (name "Net-(R24-33)") (class "Default")
      (node (ref "JP108") (pin "3") (pinfunction "3_3") (pintype "passive"))
      (node (ref "R24") (pin "3") (pinfunction "33_3") (pintype "passive"))
    )
    (net (code "103") (name "Net-(R24-44)") (class "Default")
      (node (ref "R24") (pin "4") (pinfunction "44_4") (pintype "passive"))
      (node (ref "U7") (pin "L1") (pinfunction "LCD_DATA14_L1") (pintype "bidirectional"))
    )
    (net (code "104") (name "Net-(R24-66)") (class "Default")
      (node (ref "JP109") (pin "3") (pinfunction "3_3") (pintype "passive"))
      (node (ref "R24") (pin "6") (pinfunction "66_6") (pintype "passive"))
    )
    (net (code "105") (name "Net-(R24-88)") (class "Default")
      (node (ref "J3") (pin "1") (pinfunction "1_1") (pintype "passive"))
      (node (ref "JP107") (pin "1") (pinfunction "1_1") (pintype "passive"))
      (node (ref "R24") (pin "8") (pinfunction "88_8") (pintype "passive"))
    )
    (net (code "106") (name "Net-(R24-99)") (class "Default")
      (node (ref "JP105") (pin "1") (pinfunction "1_1") (pintype "passive"))
      (node (ref "R24") (pin "9") (pinfunction "99_9") (pintype "passive"))
    )
    (net (code "107") (name "Net-(R25-11)") (class "Default")
      (node (ref "J3") (pin "3") (pinfunction "3_3") (pintype "passive"))
      (node (ref "JP107") (pin "3") (pinfunction "3_3") (pintype "passive"))
      (node (ref "R25") (pin "1") (pinfunction "11_1") (pintype "passive"))
    )
    (net (code "108") (name "Net-(R25-22)") (class "Default")
      (node (ref "JP106") (pin "3") (pinfunction "3_3") (pintype "passive"))
      (node (ref "R25") (pin "2") (pinfunction "22_2") (pintype "passive"))
    )
    (net (code "109") (name "Net-(R25-33)") (class "Default")
      (node (ref "JP105") (pin "3") (pinfunction "3_3") (pintype "passive"))
      (node (ref "R25") (pin "3") (pinfunction "33_3") (pintype "passive"))
    )
    (net (code "110") (name "Net-(R25-44)") (class "Default")
      (node (ref "R25") (pin "4") (pinfunction "44_4") (pintype "passive"))
      (node (ref "U7") (pin "H1") (pinfunction "LCD_DATA5_H1") (pintype "bidirectional"))
    )
    (net (code "111") (name "Net-(R25-66)") (class "Default")
      (node (ref "JP109") (pin "1") (pinfunction "1_1") (pintype "passive"))
      (node (ref "R25") (pin "6") (pinfunction "66_6") (pintype "passive"))
    )
    (net (code "112") (name "Net-(R25-77)") (class "Default")
      (node (ref "R25") (pin "7") (pinfunction "77_7") (pintype "passive"))
      (node (ref "U7") (pin "J3") (pinfunction "LCD_DATA6_J3") (pintype "bidirectional"))
    )
    (net (code "113") (name "Net-(R25-99)") (class "Default")
      (node (ref "JP108") (pin "1") (pinfunction "1_1") (pintype "passive"))
      (node (ref "R25") (pin "9") (pinfunction "99_9") (pintype "passive"))
    )
    (net (code "114") (name "Net-(R26-11)") (class "Default")
      (node (ref "R26") (pin "1") (pinfunction "11_1") (pintype "passive"))
      (node (ref "U7") (pin "M3") (pinfunction "LCD_DATA15_M3") (pintype "bidirectional"))
    )
    (net (code "115") (name "Net-(R26-22)") (class "Default")
      (node (ref "R26") (pin "2") (pinfunction "22_2") (pintype "passive"))
      (node (ref "U7") (pin "L3") (pinfunction "LCD_DATA12_L3") (pintype "bidirectional"))
    )
    (net (code "116") (name "Net-(R26-33)") (class "Default")
      (node (ref "R26") (pin "3") (pinfunction "33_3") (pintype "passive"))
      (node (ref "U7") (pin "K2") (pinfunction "LCD_DATA10_K2") (pintype "bidirectional"))
    )
    (net (code "117") (name "Net-(R26-44)") (class "Default")
      (node (ref "R26") (pin "4") (pinfunction "44_4") (pintype "passive"))
      (node (ref "U7") (pin "J1") (pinfunction "LCD_DATA8_J1") (pintype "bidirectional"))
    )
    (net (code "118") (name "Net-(R26-66)") (class "Default")
      (node (ref "R26") (pin "6") (pinfunction "66_6") (pintype "passive"))
      (node (ref "U7") (pin "J2") (pinfunction "LCD_DATA7_J2") (pintype "bidirectional"))
    )
    (net (code "119") (name "Net-(R26-77)") (class "Default")
      (node (ref "R26") (pin "7") (pinfunction "77_7") (pintype "passive"))
      (node (ref "U7") (pin "K3") (pinfunction "LCD_DATA9_K3") (pintype "bidirectional"))
    )
    (net (code "120") (name "Net-(R26-88)") (class "Default")
      (node (ref "R26") (pin "8") (pinfunction "88_8") (pintype "passive"))
      (node (ref "U7") (pin "K1") (pinfunction "LCD_DATA11_K1") (pintype "bidirectional"))
    )
    (net (code "121") (name "Net-(R26-99)") (class "Default")
      (node (ref "R26") (pin "9") (pinfunction "99_9") (pintype "passive"))
      (node (ref "U7") (pin "L2") (pinfunction "LCD_DATA13_L2") (pintype "bidirectional"))
    )
    (net (code "122") (name "Net-(TP30-1)") (class "Default")
      (node (ref "TP30") (pin "P$1") (pinfunction "1_P$1") (pintype "bidirectional"))
      (node (ref "U7") (pin "A4") (pinfunction "XDMA_EVENT_INTR0_A4") (pintype "bidirectional"))
    )
    (net (code "123") (name "Net-(TP31-1)") (class "Default")
      (node (ref "R19") (pin "2") (pinfunction "2_2") (pintype "passive"))
      (node (ref "TP31") (pin "P$1") (pinfunction "1_P$1") (pintype "bidirectional"))
      (node (ref "U7") (pin "D3") (pinfunction "TRSTN_D3") (pintype "bidirectional"))
    )
    (net (code "124") (name "Net-(TP35-1)") (class "Default")
      (node (ref "TP35") (pin "P$1") (pinfunction "1_P$1") (pintype "bidirectional"))
      (node (ref "U11") (pin "5") (pinfunction "SHDN_5") (pintype "input"))
    )
    (net (code "125") (name "Net-(TP38-1)") (class "Default")
      (node (ref "TP38") (pin "P$1") (pinfunction "1_P$1") (pintype "bidirectional"))
      (node (ref "U7") (pin "B8") (pinfunction "AIN1_B8") (pintype "bidirectional"))
    )
    (net (code "126") (name "Net-(TP39-1)") (class "Default")
      (node (ref "TP39") (pin "P$1") (pinfunction "1_P$1") (pintype "bidirectional"))
      (node (ref "U7") (pin "A8") (pinfunction "AIN0_A8") (pintype "bidirectional"))
    )
    (net (code "127") (name "Net-(TP40-1)") (class "Default")
      (node (ref "TP40") (pin "P$1") (pinfunction "1_P$1") (pintype "bidirectional"))
      (node (ref "U11") (pin "8") (pinfunction "S_8") (pintype "input"))
    )
    (net (code "128") (name "Net-(TP69-1)") (class "Default")
      (node (ref "TP69") (pin "P$1") (pinfunction "1_P$1") (pintype "bidirectional"))
      (node (ref "U17") (pin "7") (pinfunction "~{HOLD}_7") (pintype "input"))
    )
    (net (code "129") (name "Net-(TP100-1)") (class "Default")
      (node (ref "TP100") (pin "P$1") (pinfunction "1_P$1") (pintype "bidirectional"))
      (node (ref "U7") (pin "T12") (pinfunction "GPMC_A0_T12") (pintype "bidirectional"))
    )
    (net (code "130") (name "Net-(TP101-1)") (class "Default")
      (node (ref "TP101") (pin "P$1") (pinfunction "1_P$1") (pintype "bidirectional"))
      (node (ref "U7") (pin "T13") (pinfunction "GPMC_A3_T13") (pintype "bidirectional"))
    )
    (net (code "131") (name "Net-(TP102-1)") (class "Default")
      (node (ref "TP102") (pin "P$1") (pinfunction "1_P$1") (pintype "bidirectional"))
      (node (ref "U7") (pin "T11") (pinfunction "PMIC_PB_IN_T11") (pintype "bidirectional"))
    )
    (net (code "132") (name "Net-(TP103-1)") (class "Default")
      (node (ref "TP103") (pin "P$1") (pinfunction "1_P$1") (pintype "bidirectional"))
      (node (ref "U7") (pin "T16") (pinfunction "GPMC_A11_T16") (pintype "bidirectional"))
    )
    (net (code "133") (name "Net-(TP104-1)") (class "Default")
      (node (ref "TP104") (pin "P$1") (pinfunction "1_P$1") (pintype "bidirectional"))
      (node (ref "U7") (pin "T4") (pinfunction "GPMC_AD8_T4") (pintype "bidirectional"))
    )
    (net (code "134") (name "Net-(TP105-1)") (class "Default")
      (node (ref "TP105") (pin "P$1") (pinfunction "1_P$1") (pintype "bidirectional"))
      (node (ref "U7") (pin "T5") (pinfunction "GPMC_AD11_T5") (pintype "bidirectional"))
    )
    (net (code "135") (name "Net-(TP106-1)") (class "Default")
      (node (ref "TP106") (pin "P$1") (pinfunction "1_P$1") (pintype "bidirectional"))
      (node (ref "U7") (pin "T7") (pinfunction "GPMC_CLK_T7") (pintype "bidirectional"))
    )
    (net (code "136") (name "Net-(TP107-1)") (class "Default")
      (node (ref "TP107") (pin "P$1") (pinfunction "1_P$1") (pintype "bidirectional"))
      (node (ref "U7") (pin "R7") (pinfunction "GPMC_CSN3_R7") (pintype "bidirectional"))
    )
    (net (code "137") (name "Net-(TP108-1)") (class "Default")
      (node (ref "TP108") (pin "P$1") (pinfunction "1_P$1") (pintype "bidirectional"))
      (node (ref "U7") (pin "T15") (pinfunction "GPMC_A9_T15") (pintype "bidirectional"))
    )
    (net (code "138") (name "Net-(TP111-1)") (class "Default")
      (node (ref "TP111") (pin "P$1") (pinfunction "1_P$1") (pintype "bidirectional"))
      (node (ref "U7") (pin "R16") (pinfunction "GPMC_WPN_R16") (pintype "bidirectional"))
    )
    (net (code "139") (name "Net-(TP114-1)") (class "Default")
      (node (ref "TP114") (pin "P$1") (pinfunction "1_P$1") (pintype "bidirectional"))
      (node (ref "U7") (pin "P15") (pinfunction "GPMC_WAIT0_P15") (pintype "bidirectional"))
    )
    (net (code "140") (name "Net-(TP115-1)") (class "Default")
      (node (ref "TP115") (pin "P$1") (pinfunction "1_P$1") (pintype "bidirectional"))
      (node (ref "U7") (pin "R5") (pinfunction "GPMC_AD10_R5") (pintype "bidirectional"))
    )
    (net (code "141") (name "Net-(TP117-1)") (class "Default")
      (node (ref "TP117") (pin "P$1") (pinfunction "1_P$1") (pintype "bidirectional"))
      (node (ref "U7") (pin "R15") (pinfunction "GPMC_A10_R15") (pintype "bidirectional"))
    )
    (net (code "142") (name "Net-(TP118-1)") (class "Default")
      (node (ref "TP118") (pin "P$1") (pinfunction "1_P$1") (pintype "bidirectional"))
      (node (ref "U7") (pin "R12") (pinfunction "GPMC_A1_R12") (pintype "bidirectional"))
    )
    (net (code "143") (name "Net-(TP120-1)") (class "Default")
      (node (ref "TP120") (pin "P$1") (pinfunction "1_P$1") (pintype "bidirectional"))
      (node (ref "U7") (pin "R6") (pinfunction "GPMC_AD13_R6") (pintype "bidirectional"))
    )
    (net (code "144") (name "Net-(TP121-1)") (class "Default")
      (node (ref "TP121") (pin "P$1") (pinfunction "1_P$1") (pintype "bidirectional"))
      (node (ref "U7") (pin "N10") (pinfunction "PMIC_POWER_EN_N10") (pintype "output"))
      (node (ref "U7") (pin "N11") (pinfunction "PMIC_PWR_EN_N11") (pintype "input"))
    )
    (net (code "145") (name "Net-(TP122-1)") (class "Default")
      (node (ref "TP122") (pin "P$1") (pinfunction "1_P$1") (pintype "bidirectional"))
      (node (ref "U7") (pin "P3") (pinfunction "GPMC_CSN0_P3") (pintype "bidirectional"))
    )
    (net (code "146") (name "Net-(TP123-1)") (class "Default")
      (node (ref "TP123") (pin "P$1") (pinfunction "1_P$1") (pintype "bidirectional"))
      (node (ref "U7") (pin "P5") (pinfunction "GPMC_AD9_P5") (pintype "bidirectional"))
    )
    (net (code "147") (name "Net-(TP124-1)") (class "Default")
      (node (ref "TP124") (pin "P$1") (pinfunction "1_P$1") (pintype "bidirectional"))
      (node (ref "U7") (pin "P6") (pinfunction "GPMC_AD12_P6") (pintype "bidirectional"))
    )
    (net (code "148") (name "Net-(TP125-1)") (class "Default")
      (node (ref "TP125") (pin "P$1") (pinfunction "1_P$1") (pintype "bidirectional"))
      (node (ref "U7") (pin "N14") (pinfunction "GPMC_BEN1_N14") (pintype "bidirectional"))
    )
    (net (code "149") (name "Net-(TP126-1)") (class "Default")
      (node (ref "TP126") (pin "P$1") (pinfunction "1_P$1") (pintype "bidirectional"))
      (node (ref "U7") (pin "P12") (pinfunction "GPMC_A2_P12") (pintype "bidirectional"))
    )
    (net (code "150") (name "Net-(TP127-1)") (class "Default")
      (node (ref "TP127") (pin "P$1") (pinfunction "1_P$1") (pintype "bidirectional"))
      (node (ref "U7") (pin "N2") (pinfunction "GPMC_WEN_N2") (pintype "bidirectional"))
    )
    (net (code "151") (name "Net-(TP128-1)") (class "Default")
      (node (ref "TP128") (pin "P$1") (pinfunction "1_P$1") (pintype "bidirectional"))
      (node (ref "U7") (pin "N1") (pinfunction "GPMC_OEN_REN_N1") (pintype "bidirectional"))
    )
    (net (code "152") (name "Net-(TP129-1)") (class "Default")
      (node (ref "TP129") (pin "P$1") (pinfunction "1_P$1") (pintype "bidirectional"))
      (node (ref "U7") (pin "N6") (pinfunction "PMIC_TS_N6") (pintype "bidirectional"))
    )
    (net (code "153") (name "Net-(TP130-1)") (class "Default")
      (node (ref "TP130") (pin "P$1") (pinfunction "1_P$1") (pintype "bidirectional"))
      (node (ref "TP4") (pin "P$1") (pinfunction "1_P$1") (pintype "bidirectional"))
      (node (ref "U7") (pin "N7") (pinfunction "PMIC_BAT_SENSE_N7") (pintype "bidirectional"))
      (node (ref "U7") (pin "P8") (pinfunction "VIN_BAT_P8") (pintype "power_in"))
      (node (ref "U7") (pin "R8") (pinfunction "VIN_BAT_R8") (pintype "power_in"))
      (node (ref "U7") (pin "T8") (pinfunction "VIN_BAT_T8") (pintype "power_in"))
    )
    (net (code "154") (name "Net-(TP131-1)") (class "Default")
      (node (ref "TP131") (pin "P$1") (pinfunction "1_P$1") (pintype "bidirectional"))
      (node (ref "U7") (pin "N3") (pinfunction "GPMC_BEN0_CLE_N3") (pintype "bidirectional"))
    )
    (net (code "155") (name "Net-(TP132-1)") (class "Default")
      (node (ref "TP132") (pin "P$1") (pinfunction "1_P$1") (pintype "bidirectional"))
      (node (ref "U7") (pin "N4") (pinfunction "PMIC_LDO_PGOOD_N4") (pintype "output"))
      (node (ref "U7") (pin "N5") (pinfunction "RTC_PWRONRSTN_N5") (pintype "bidirectional"))
    )
    (net (code "156") (name "Net-(TP133-1)") (class "Default")
      (node (ref "TP133") (pin "P$1") (pinfunction "1_P$1") (pintype "bidirectional"))
      (node (ref "U7") (pin "N13") (pinfunction "PMIC_MUX_IN_N13") (pintype "bidirectional"))
    )
    (net (code "157") (name "Net-(TP134-1)") (class "Default")
      (node (ref "TP134") (pin "P$1") (pinfunction "1_P$1") (pintype "bidirectional"))
      (node (ref "U7") (pin "M1") (pinfunction "GPMC_ADVN_ALE_M1") (pintype "bidirectional"))
    )
    (net (code "158") (name "Net-(TP135-1)") (class "Default")
      (node (ref "TP135") (pin "P$1") (pinfunction "1_P$1") (pintype "bidirectional"))
      (node (ref "U7") (pin "G16") (pinfunction "MII1_TXD2_G16") (pintype "bidirectional"))
    )
    (net (code "159") (name "Net-(TP136-1)") (class "Default")
      (node (ref "TP136") (pin "P$1") (pinfunction "1_P$1") (pintype "bidirectional"))
      (node (ref "U7") (pin "M13") (pinfunction "PMIC_NRESET_M13") (pintype "bidirectional"))
    )
    (net (code "160") (name "Net-(TP137-1)") (class "Default")
      (node (ref "TP137") (pin "P$1") (pinfunction "1_P$1") (pintype "bidirectional"))
      (node (ref "U7") (pin "H15") (pinfunction "MII1_TXD0_H15") (pintype "bidirectional"))
    )
    (net (code "161") (name "Net-(TP138-1)") (class "Default")
      (node (ref "TP138") (pin "P$1") (pinfunction "1_P$1") (pintype "bidirectional"))
      (node (ref "U7") (pin "K14") (pinfunction "USB0_ID_K14") (pintype "bidirectional"))
    )
    (net (code "162") (name "Net-(TP139-1)") (class "Default")
      (node (ref "TP139") (pin "P$1") (pinfunction "1_P$1") (pintype "bidirectional"))
      (node (ref "U7") (pin "J15") (pinfunction "USB0_DRVVBUS_J15") (pintype "bidirectional"))
    )
    (net (code "163") (name "Net-(TP140-1)") (class "Default")
      (node (ref "TP140") (pin "P$1") (pinfunction "1_P$1") (pintype "bidirectional"))
      (node (ref "U7") (pin "L4") (pinfunction "PMIC_NWAKEUP_L4") (pintype "output"))
      (node (ref "U7") (pin "M4") (pinfunction "EXT_WAKEUP_M4") (pintype "bidirectional"))
    )
    (net (code "164") (name "Net-(TP141-1)") (class "Default")
      (node (ref "TP141") (pin "P$1") (pinfunction "1_P$1") (pintype "bidirectional"))
      (node (ref "U7") (pin "K13") (pinfunction "USB0_CE_K13") (pintype "bidirectional"))
    )
    (net (code "165") (name "Net-(TP143-1)") (class "Default")
      (node (ref "TP143") (pin "P$1") (pinfunction "1_P$1") (pintype "bidirectional"))
      (node (ref "U7") (pin "J14") (pinfunction "RMII1_REF_CLK_J14") (pintype "bidirectional"))
    )
    (net (code "166") (name "Net-(TP144-1)") (class "Default")
      (node (ref "TP144") (pin "P$1") (pinfunction "1_P$1") (pintype "bidirectional"))
      (node (ref "U7") (pin "L13") (pinfunction "USB1_CE_L13") (pintype "bidirectional"))
    )
    (net (code "167") (name "Net-(TP145-1)") (class "Default")
      (node (ref "TP145") (pin "P$1") (pinfunction "1_P$1") (pintype "bidirectional"))
      (node (ref "U7") (pin "K4") (pinfunction "NC_K4") (pintype "bidirectional"))
    )
    (net (code "168") (name "Net-(TP147-1)") (class "Default")
      (node (ref "TP147") (pin "P$1") (pinfunction "1_P$1") (pintype "bidirectional"))
      (node (ref "U7") (pin "H16") (pinfunction "MII1_TX_CLK_H16") (pintype "bidirectional"))
    )
    (net (code "169") (name "Net-(TP148-1)") (class "Default")
      (node (ref "TP148") (pin "P$1") (pinfunction "1_P$1") (pintype "bidirectional"))
      (node (ref "U7") (pin "G14") (pinfunction "MII1_TX_EN_G14") (pintype "bidirectional"))
    )
    (net (code "170") (name "Net-(TP149-1)") (class "Default")
      (node (ref "TP149") (pin "P$1") (pinfunction "1_P$1") (pintype "bidirectional"))
      (node (ref "U7") (pin "H14") (pinfunction "MII1_TXD1_H14") (pintype "bidirectional"))
    )
    (net (code "171") (name "Net-(TP150-1)") (class "Default")
      (node (ref "TP150") (pin "P$1") (pinfunction "1_P$1") (pintype "bidirectional"))
      (node (ref "U7") (pin "J6") (pinfunction "NC_J6") (pintype "bidirectional"))
    )
    (net (code "172") (name "Net-(TP152-1)") (class "Default")
      (node (ref "TP152") (pin "P$1") (pinfunction "1_P$1") (pintype "bidirectional"))
      (node (ref "U7") (pin "F2") (pinfunction "LCD_HSYNC_F2") (pintype "bidirectional"))
    )
    (net (code "173") (name "Net-(TP153-1)") (class "Default")
      (node (ref "TP153") (pin "P$1") (pinfunction "1_P$1") (pintype "bidirectional"))
      (node (ref "U7") (pin "F3") (pinfunction "LCD_VSYNC_F3") (pintype "bidirectional"))
    )
    (net (code "174") (name "Net-(TP154-1)") (class "Default")
      (node (ref "TP154") (pin "P$1") (pinfunction "1_P$1") (pintype "bidirectional"))
      (node (ref "U7") (pin "G4") (pinfunction "VDD_CORE_G4") (pintype "bidirectional"))
    )
    (net (code "175") (name "Net-(TP156-1)") (class "Default")
      (node (ref "TP156") (pin "P$1") (pinfunction "1_P$1") (pintype "bidirectional"))
      (node (ref "U7") (pin "F4") (pinfunction "VDDS_DDR_F4") (pintype "bidirectional"))
    )
    (net (code "176") (name "Net-(TP157-1)") (class "Default")
      (node (ref "TP157") (pin "P$1") (pinfunction "1_P$1") (pintype "bidirectional"))
      (node (ref "U7") (pin "H6") (pinfunction "VPP_H6") (pintype "bidirectional"))
    )
    (net (code "177") (name "Net-(TP158-1)") (class "Default")
      (node (ref "TP158") (pin "P$1") (pinfunction "1_P$1") (pintype "bidirectional"))
      (node (ref "U7") (pin "E13") (pinfunction "MDIO_E13") (pintype "bidirectional"))
    )
    (net (code "178") (name "Net-(TP159-1)") (class "Default")
      (node (ref "TP159") (pin "P$1") (pinfunction "1_P$1") (pintype "bidirectional"))
      (node (ref "U7") (pin "E1") (pinfunction "LCD_AC_BIAS_EN_E1") (pintype "bidirectional"))
    )
    (net (code "179") (name "Net-(TP160-1)") (class "Default")
      (node (ref "TP160") (pin "P$1") (pinfunction "1_P$1") (pintype "bidirectional"))
      (node (ref "U7") (pin "F13") (pinfunction "VDD_MPU_F13") (pintype "bidirectional"))
    )
    (net (code "180") (name "Net-(TP161-1)") (class "Default")
      (node (ref "TP161") (pin "P$1") (pinfunction "1_P$1") (pintype "bidirectional"))
      (node (ref "U7") (pin "F11") (pinfunction "SYS_VDD2_3P3V_F11") (pintype "power_in"))
      (node (ref "U7") (pin "G11") (pinfunction "SYS_VDD2_3P3V_G11") (pintype "power_in"))
    )
    (net (code "181") (name "Net-(TP162-1)") (class "Default")
      (node (ref "TP162") (pin "P$1") (pinfunction "1_P$1") (pintype "bidirectional"))
      (node (ref "U7") (pin "F1") (pinfunction "LCD_PCLK_F1") (pintype "bidirectional"))
    )
    (net (code "182") (name "Net-(TP163-1)") (class "Default")
      (node (ref "TP163") (pin "P$1") (pinfunction "1_P$1") (pintype "bidirectional"))
      (node (ref "U7") (pin "F10") (pinfunction "SYS_VDD_1P8V_F10") (pintype "power_in"))
      (node (ref "U7") (pin "G10") (pinfunction "SYS_VDD_1P8V_G10") (pintype "power_in"))
      (node (ref "U7") (pin "H10") (pinfunction "SYS_VDD_1P8V_H10") (pintype "power_in"))
      (node (ref "U7") (pin "H11") (pinfunction "SYS_VDD_1P8V_H11") (pintype "power_in"))
      (node (ref "U7") (pin "J10") (pinfunction "SYS_VDD_1P8V_J10") (pintype "power_in"))
      (node (ref "U7") (pin "J11") (pinfunction "SYS_VDD_1P8V_J11") (pintype "power_in"))
      (node (ref "U7") (pin "K10") (pinfunction "SYS_VDD_1P8V_K10") (pintype "power_in"))
      (node (ref "U7") (pin "L10") (pinfunction "SYS_VDD_1P8V_L10") (pintype "power_in"))
    )
    (net (code "183") (name "Net-(TP165-1)") (class "Default")
      (node (ref "JP101") (pin "1") (pinfunction "1_1") (pintype "passive"))
      (node (ref "TP165") (pin "P$1") (pinfunction "1_P$1") (pintype "bidirectional"))
      (node (ref "U7") (pin "F8") (pinfunction "SYS_VDD3_3P3V_F8") (pintype "power_in"))
      (node (ref "U7") (pin "F9") (pinfunction "VDDSHV4_F9") (pintype "power_in"))
      (node (ref "U7") (pin "G8") (pinfunction "SYS_VDD3_3P3V_G8") (pintype "power_in"))
      (node (ref "U7") (pin "G9") (pinfunction "VDDSHV5_G9") (pintype "power_in"))
      (node (ref "U7") (pin "H7") (pinfunction "SYS_VDD3_3P3V_H7") (pintype "power_in"))
      (node (ref "U7") (pin "H8") (pinfunction "SYS_VDD3_3P3V_H8") (pintype "power_in"))
      (node (ref "U7") (pin "H9") (pinfunction "VDDSHV6_H9") (pintype "power_in"))
      (node (ref "U7") (pin "J7") (pinfunction "SYS_VDD3_3P3V_J7") (pintype "power_in"))
      (node (ref "U7") (pin "J8") (pinfunction "SYS_VDD3_3P3V_J8") (pintype "power_in"))
      (node (ref "U7") (pin "J9") (pinfunction "VDDSHV1_J9") (pintype "power_in"))
      (node (ref "U7") (pin "K8") (pinfunction "SYS_VDD3_3P3V_K8") (pintype "power_in"))
      (node (ref "U7") (pin "K9") (pinfunction "VDDSHV2_K9") (pintype "power_in"))
      (node (ref "U7") (pin "L8") (pinfunction "SYS_VDD3_3P3V_L8") (pintype "power_in"))
      (node (ref "U7") (pin "L9") (pinfunction "VDDSHV3_L9") (pintype "power_in"))
    )
    (net (code "184") (name "Net-(TP166-1)") (class "Default")
      (node (ref "TP166") (pin "P$1") (pinfunction "1_P$1") (pintype "bidirectional"))
      (node (ref "U7") (pin "G13") (pinfunction "VDDS_PLL_G13") (pintype "bidirectional"))
    )
    (net (code "185") (name "Net-(TP167-1)") (class "Default")
      (node (ref "TP167") (pin "P$1") (pinfunction "1_P$1") (pintype "bidirectional"))
      (node (ref "U7") (pin "D4") (pinfunction "EXTINTN_D4") (pintype "bidirectional"))
      (node (ref "U7") (pin "E4") (pinfunction "PMIC_NINT_E4") (pintype "output"))
    )
    (net (code "186") (name "Net-(TP168-1)") (class "Default")
      (node (ref "TP168") (pin "P$1") (pinfunction "1_P$1") (pintype "bidirectional"))
      (node (ref "U7") (pin "D6") (pinfunction "PMIC_MUX_OUT_D6") (pintype "bidirectional"))
    )
    (net (code "187") (name "Net-(TP169-1)") (class "Default")
      (node (ref "TP169") (pin "P$1") (pinfunction "1_P$1") (pintype "bidirectional"))
      (node (ref "U7") (pin "C8") (pinfunction "AIN5_C8") (pintype "bidirectional"))
    )
    (net (code "188") (name "Net-(TP170-1)") (class "Default")
      (node (ref "TP170") (pin "P$1") (pinfunction "1_P$1") (pintype "bidirectional"))
      (node (ref "U7") (pin "D7") (pinfunction "AIN7_D7") (pintype "bidirectional"))
    )
    (net (code "189") (name "Net-(TP171-1)") (class "Default")
      (node (ref "TP171") (pin "P$1") (pinfunction "1_P$1") (pintype "bidirectional"))
      (node (ref "U7") (pin "A9") (pinfunction "AGND_ADC_A9") (pintype "bidirectional"))
      (node (ref "U7") (pin "B7") (pinfunction "VREFP_B7") (pintype "bidirectional"))
      (node (ref "U7") (pin "B9") (pinfunction "VREFN_B9") (pintype "bidirectional"))
    )
    (net (code "190") (name "Net-(TP172-1)") (class "Default")
      (node (ref "TP172") (pin "P$1") (pinfunction "1_P$1") (pintype "bidirectional"))
      (node (ref "U7") (pin "D12") (pinfunction "NC_D12") (pintype "bidirectional"))
    )
    (net (code "191") (name "Net-(TP173-1)") (class "Default")
      (node (ref "TP173") (pin "P$1") (pinfunction "1_P$1") (pintype "bidirectional"))
      (node (ref "U7") (pin "D5") (pinfunction "CAP_VDD_RTC_D5") (pintype "bidirectional"))
    )
    (net (code "192") (name "Net-(TP174-1)") (class "Default")
      (node (ref "TP174") (pin "P$1") (pinfunction "1_P$1") (pintype "bidirectional"))
      (node (ref "U7") (pin "D13") (pinfunction "MDC_D13") (pintype "bidirectional"))
    )
    (net (code "193") (name "Net-(TP175-1)") (class "Default")
      (node (ref "TP175") (pin "P$1") (pinfunction "1_P$1") (pintype "bidirectional"))
      (node (ref "U7") (pin "C6") (pinfunction "AIN3_C6") (pintype "bidirectional"))
    )
    (net (code "194") (name "Net-(TP176-1)") (class "Default")
      (node (ref "TP176") (pin "P$1") (pinfunction "1_P$1") (pintype "bidirectional"))
      (node (ref "U7") (pin "C7") (pinfunction "AIN4_C7") (pintype "bidirectional"))
    )
    (net (code "195") (name "Net-(TP177-1)") (class "Default")
      (node (ref "TP177") (pin "P$1") (pinfunction "1_P$1") (pintype "bidirectional"))
      (node (ref "U7") (pin "C12") (pinfunction "UART0_CTSN_C12") (pintype "bidirectional"))
    )
    (net (code "196") (name "Net-(TP178-1)") (class "Default")
      (node (ref "TP178") (pin "P$1") (pinfunction "1_P$1") (pintype "bidirectional"))
      (node (ref "U7") (pin "C13") (pinfunction "UART0_RTSN_C13") (pintype "bidirectional"))
    )
    (net (code "197") (name "Net-(TP179-1)") (class "Default")
      (node (ref "TP179") (pin "P$1") (pinfunction "1_P$1") (pintype "bidirectional"))
      (node (ref "U7") (pin "C9") (pinfunction "AIN6_C9") (pintype "bidirectional"))
    )
    (net (code "198") (name "Net-(TP180-1)") (class "Default")
      (node (ref "TP180") (pin "P$1") (pinfunction "1_P$1") (pintype "bidirectional"))
      (node (ref "U7") (pin "C5") (pinfunction "ECAP0_IN_PWM0_OUT_C5") (pintype "bidirectional"))
    )
    (net (code "199") (name "Net-(TP181-1)") (class "Default")
      (node (ref "TP181") (pin "P$1") (pinfunction "1_P$1") (pintype "bidirectional"))
      (node (ref "U7") (pin "B6") (pinfunction "AIN2_B6") (pintype "bidirectional"))
    )
    (net (code "200") (name "Net-(TP182-1)") (class "Default")
      (node (ref "TP182") (pin "P$1") (pinfunction "1_P$1") (pintype "bidirectional"))
      (node (ref "U7") (pin "A7") (pinfunction "SYS_ADC_1P8V_A7") (pintype "bidirectional"))
    )
    (net (code "201") (name "Net-(U2-EN)") (class "Default")
      (node (ref "R6") (pin "2") (pinfunction "2_2") (pintype "passive"))
      (node (ref "U2") (pin "4") (pinfunction "EN_4") (pintype "input"))
      (node (ref "U7") (pin "M14") (pinfunction "USB1_DRVVBUS_M14") (pintype "bidirectional"))
    )
    (net (code "202") (name "Net-(U2-~{FLT})") (class "Default")
      (node (ref "R7") (pin "1") (pinfunction "1_1") (pintype "passive"))
      (node (ref "U2") (pin "3") (pinfunction "~{FLT}_3") (pintype "output"))
    )
    (net (code "203") (name "Net-(U3-VDDI)") (class "Default")
      (node (ref "C10") (pin "1") (pinfunction "1_1") (pintype "passive"))
      (node (ref "C12") (pin "1") (pinfunction "1_1") (pintype "passive"))
      (node (ref "U3") (pin "C2") (pinfunction "VDDI_C2") (pintype "power_in"))
    )
    (net (code "204") (name "Net-(U5-DIR)") (class "Default")
      (node (ref "R14") (pin "1") (pinfunction "1_1") (pintype "passive"))
      (node (ref "U5") (pin "2") (pinfunction "DIR_2") (pintype "input"))
    )
    (net (code "205") (name "Net-(U6-1DIR)") (class "Default")
      (node (ref "R16") (pin "1") (pinfunction "1_1") (pintype "passive"))
      (node (ref "U6") (pin "1") (pinfunction "1DIR_1") (pintype "input"))
      (node (ref "U6") (pin "24") (pinfunction "2DIR_24") (pintype "input"))
    )
    (net (code "206") (name "Net-(U7A-EEPROM_WP)") (class "Default")
      (node (ref "R75") (pin "2") (pinfunction "2_2") (pintype "passive"))
      (node (ref "U7") (pin "M2") (pinfunction "EEPROM_WP_M2") (pintype "bidirectional"))
    )
    (net (code "207") (name "Net-(U7A-I2C0_SCL)") (class "Default")
      (node (ref "R73") (pin "2") (pinfunction "2_2") (pintype "passive"))
      (node (ref "U7") (pin "C10") (pinfunction "I2C0_SCL_C10") (pintype "bidirectional"))
      (node (ref "U7") (pin "D10") (pinfunction "PMIC_SCL_D10") (pintype "bidirectional"))
    )
    (net (code "208") (name "Net-(U7A-I2C0_SDA)") (class "Default")
      (node (ref "R74") (pin "2") (pinfunction "2_2") (pintype "passive"))
      (node (ref "U7") (pin "C11") (pinfunction "I2C0_SDA_C11") (pintype "bidirectional"))
      (node (ref "U7") (pin "D11") (pinfunction "PMIC_SDA_D11") (pintype "bidirectional"))
    )
    (net (code "209") (name "Net-(U7A-RTC_KALDO_ENN)") (class "Default")
      (node (ref "R15") (pin "2") (pinfunction "2_2") (pintype "passive"))
      (node (ref "U7") (pin "M16") (pinfunction "RTC_KALDO_ENN_M16") (pintype "bidirectional"))
    )
    (net (code "210") (name "Net-(U7B-EMU0)") (class "Default")
      (node (ref "R22") (pin "1") (pinfunction "1_1") (pintype "passive"))
      (node (ref "U7") (pin "E2") (pinfunction "EMU0_E2") (pintype "bidirectional"))
    )
    (net (code "211") (name "Net-(U7B-EMU1)") (class "Default")
      (node (ref "R20") (pin "1") (pinfunction "1_1") (pintype "passive"))
      (node (ref "U7") (pin "E3") (pinfunction "EMU1_E3") (pintype "bidirectional"))
    )
    (net (code "212") (name "Net-(U7B-OSC1_GND)") (class "Default")
      (node (ref "C29") (pin "2") (pinfunction "2_2") (pintype "passive"))
      (node (ref "C30") (pin "2") (pinfunction "2_2") (pintype "passive"))
      (node (ref "U7") (pin "B5") (pinfunction "OSC1_GND_B5") (pintype "bidirectional"))
    )
    (net (code "213") (name "Net-(U7B-OSC1_IN)") (class "Default")
      (node (ref "C30") (pin "1") (pinfunction "1_1") (pintype "passive"))
      (node (ref "R27") (pin "2") (pinfunction "2_2") (pintype "passive"))
      (node (ref "U7") (pin "A6") (pinfunction "OSC1_IN_A6") (pintype "bidirectional"))
      (node (ref "Y2") (pin "P$2") (pinfunction "P$2_P$2") (pintype "passive"))
    )
    (net (code "214") (name "Net-(U7B-OSC1_OUT)") (class "Default")
      (node (ref "C29") (pin "1") (pinfunction "1_1") (pintype "passive"))
      (node (ref "R27") (pin "1") (pinfunction "1_1") (pintype "passive"))
      (node (ref "U7") (pin "A5") (pinfunction "OSC1_OUT_A5") (pintype "bidirectional"))
      (node (ref "Y2") (pin "P$1") (pinfunction "P$1_P$1") (pintype "passive"))
    )
    (net (code "215") (name "Net-(U7B-USB1_ID)") (class "Default")
      (node (ref "JP100") (pin "1") (pinfunction "1_1") (pintype "passive"))
      (node (ref "U7") (pin "L14") (pinfunction "USB1_ID_L14") (pintype "bidirectional"))
    )
    (net (code "216") (name "Net-(U7C-GPMC_A5)") (class "Default")
      (node (ref "R2") (pin "1") (pinfunction "1_1") (pintype "passive"))
      (node (ref "U7") (pin "P13") (pinfunction "GPMC_A5_P13") (pintype "bidirectional"))
    )
    (net (code "217") (name "Net-(U7C-GPMC_A6)") (class "Default")
      (node (ref "R3") (pin "1") (pinfunction "1_1") (pintype "passive"))
      (node (ref "U7") (pin "T14") (pinfunction "GPMC_A6_T14") (pintype "bidirectional"))
    )
    (net (code "218") (name "Net-(U7C-GPMC_A7)") (class "Default")
      (node (ref "R4") (pin "1") (pinfunction "1_1") (pintype "passive"))
      (node (ref "U7") (pin "R14") (pinfunction "GPMC_A7_R14") (pintype "bidirectional"))
    )
    (net (code "219") (name "Net-(U7C-GPMC_A8)") (class "Default")
      (node (ref "R5") (pin "1") (pinfunction "1_1") (pintype "passive"))
      (node (ref "U7") (pin "P14") (pinfunction "GPMC_A8_P14") (pintype "bidirectional"))
    )
    (net (code "220") (name "Net-(U7C-MMC0_DAT0)") (class "Default")
      (node (ref "JP111") (pin "2") (pinfunction "2_2") (pintype "passive"))
      (node (ref "U7") (pin "A16") (pinfunction "MMC0_DAT0_A16") (pintype "bidirectional"))
    )
    (net (code "221") (name "Net-(U7C-MMC0_DAT1)") (class "Default")
      (node (ref "JP110") (pin "2") (pinfunction "2_2") (pintype "passive"))
      (node (ref "U7") (pin "A15") (pinfunction "MMC0_DAT1_A15") (pintype "bidirectional"))
    )
    (net (code "222") (name "Net-(U7C-MMC0_DAT2)") (class "Default")
      (node (ref "JP103") (pin "2") (pinfunction "2_2") (pintype "passive"))
      (node (ref "U7") (pin "C16") (pinfunction "MMC0_DAT2_C16") (pintype "bidirectional"))
    )
    (net (code "223") (name "Net-(U7C-MMC0_DAT3)") (class "Default")
      (node (ref "JP102") (pin "2") (pinfunction "2_2") (pintype "passive"))
      (node (ref "U7") (pin "C15") (pinfunction "MMC0_DAT3_C15") (pintype "bidirectional"))
    )
    (net (code "224") (name "Net-(U7D-LCD_DATA0)") (class "Default")
      (node (ref "JP105") (pin "2") (pinfunction "2_2") (pintype "passive"))
      (node (ref "U7") (pin "G3") (pinfunction "LCD_DATA0_G3") (pintype "bidirectional"))
    )
    (net (code "225") (name "Net-(U7D-LCD_DATA1)") (class "Default")
      (node (ref "JP106") (pin "2") (pinfunction "2_2") (pintype "passive"))
      (node (ref "U7") (pin "G2") (pinfunction "LCD_DATA1_G2") (pintype "bidirectional"))
    )
    (net (code "226") (name "Net-(U7D-LCD_DATA2)") (class "Default")
      (node (ref "J3") (pin "2") (pinfunction "2_2") (pintype "passive"))
      (node (ref "JP107") (pin "2") (pinfunction "2_2") (pintype "passive"))
      (node (ref "U7") (pin "G1") (pinfunction "LCD_DATA2_G1") (pintype "bidirectional"))
    )
    (net (code "227") (name "Net-(U7D-LCD_DATA3)") (class "Default")
      (node (ref "JP108") (pin "2") (pinfunction "2_2") (pintype "passive"))
      (node (ref "U7") (pin "H3") (pinfunction "LCD_DATA3_H3") (pintype "bidirectional"))
    )
    (net (code "228") (name "Net-(U7D-LCD_DATA4)") (class "Default")
      (node (ref "JP109") (pin "2") (pinfunction "2_2") (pintype "passive"))
      (node (ref "U7") (pin "H2") (pinfunction "LCD_DATA4_H2") (pintype "bidirectional"))
    )
    (net (code "229") (name "Net-(U9-EN)") (class "Default")
      (node (ref "R21") (pin "1") (pinfunction "1_1") (pintype "passive"))
      (node (ref "U9") (pin "5") (pinfunction "EN_5") (pintype "input"))
    )
    (net (code "230") (name "Net-(U10-ANODE)") (class "Default")
      (node (ref "JP104") (pin "2") (pinfunction "2_2") (pintype "passive"))
      (node (ref "Q1") (pin "C") (pinfunction "C_C") (pintype "passive"))
      (node (ref "R31") (pin "1") (pinfunction "1_1") (pintype "passive"))
      (node (ref "U10") (pin "3") (pinfunction "ANODE_3") (pintype "bidirectional"))
    )
    (net (code "231") (name "Net-(U10-CATHODE)") (class "Default")
      (node (ref "Q1") (pin "B") (pinfunction "B_B") (pintype "passive"))
      (node (ref "R23") (pin "1") (pinfunction "1_1") (pintype "passive"))
      (node (ref "U10") (pin "2") (pinfunction "CATHODE_2") (pintype "bidirectional"))
    )
    (net (code "232") (name "Net-(U10-REF)") (class "Default")
      (node (ref "R28") (pin "1") (pinfunction "1_1") (pintype "passive"))
      (node (ref "R31") (pin "2") (pinfunction "2_2") (pintype "passive"))
      (node (ref "U10") (pin "1") (pinfunction "REF_1") (pintype "bidirectional"))
    )
    (net (code "233") (name "Net-(U11-RXD)") (class "Default")
      (node (ref "U11") (pin "4") (pinfunction "RXD_4") (pintype "output"))
      (node (ref "U7") (pin "B11") (pinfunction "UART1_TXD_B11") (pintype "bidirectional"))
    )
    (net (code "234") (name "Net-(U11-TXD)") (class "Default")
      (node (ref "U11") (pin "1") (pinfunction "TXD_1") (pintype "input"))
      (node (ref "U7") (pin "A11") (pinfunction "UART1_RXD_A11") (pintype "bidirectional"))
    )
    (net (code "235") (name "Net-(U12-INP)") (class "Default")
      (node (ref "C32") (pin "1") (pinfunction "1_1") (pintype "passive"))
      (node (ref "R36") (pin "1") (pinfunction "1_1") (pintype "passive"))
      (node (ref "R37") (pin "1") (pinfunction "1_1") (pintype "passive"))
      (node (ref "U12") (pin "1") (pinfunction "INP_1") (pintype "input"))
    )
    (net (code "236") (name "Net-(U12-OUT)") (class "Default")
      (node (ref "R35") (pin "1") (pinfunction "1_1") (pintype "passive"))
      (node (ref "TP44") (pin "1") (pinfunction "1_1") (pintype "passive"))
      (node (ref "U12") (pin "4") (pinfunction "OUT_4") (pintype "output"))
    )
    (net (code "237") (name "Net-(U13-INP)") (class "Default")
      (node (ref "C35") (pin "1") (pinfunction "1_1") (pintype "passive"))
      (node (ref "R44") (pin "1") (pinfunction "1_1") (pintype "passive"))
      (node (ref "R45") (pin "1") (pinfunction "1_1") (pintype "passive"))
      (node (ref "U13") (pin "1") (pinfunction "INP_1") (pintype "input"))
    )
    (net (code "238") (name "Net-(U13-OUT)") (class "Default")
      (node (ref "R43") (pin "1") (pinfunction "1_1") (pintype "passive"))
      (node (ref "TP43") (pin "1") (pinfunction "1_1") (pintype "passive"))
      (node (ref "U13") (pin "4") (pinfunction "OUT_4") (pintype "output"))
    )
    (net (code "239") (name "Net-(U14-CIN1+)") (class "Default")
      (node (ref "R50") (pin "1") (pinfunction "1_1") (pintype "passive"))
      (node (ref "R51") (pin "2") (pinfunction "2_2") (pintype "passive"))
      (node (ref "TP57") (pin "1") (pinfunction "1_1") (pintype "passive"))
      (node (ref "U14") (pin "10") (pinfunction "CIN1+_10") (pintype "input"))
    )
    (net (code "240") (name "Net-(U14-CIN1-)") (class "Default")
      (node (ref "R42") (pin "2") (pinfunction "2_2") (pintype "passive"))
      (node (ref "R47") (pin "1") (pinfunction "1_1") (pintype "passive"))
      (node (ref "TP47") (pin "1") (pinfunction "1_1") (pintype "passive"))
      (node (ref "U14") (pin "11") (pinfunction "CIN1-_11") (pintype "input"))
    )
    (net (code "241") (name "Net-(U14-CIN2+)") (class "Default")
      (node (ref "R47") (pin "2") (pinfunction "2_2") (pintype "passive"))
      (node (ref "U14") (pin "12") (pinfunction "REF_12") (pintype "output"))
      (node (ref "U14") (pin "8") (pinfunction "CIN2+_8") (pintype "input"))
    )
    (net (code "242") (name "Net-(U14-INHIBIT)") (class "Default")
      (node (ref "R38") (pin "1") (pinfunction "1_1") (pintype "passive"))
      (node (ref "U14") (pin "5") (pinfunction "INHIBIT_5") (pintype "input"))
    )
    (net (code "243") (name "Net-(U14-IOUT)") (class "Default")
      (node (ref "R50") (pin "2") (pinfunction "2_2") (pintype "passive"))
      (node (ref "U14") (pin "14") (pinfunction "IOUT_14") (pintype "output"))
    )
    (net (code "244") (name "Net-(U14-RS+)") (class "Default")
      (node (ref "C44") (pin "1") (pinfunction "1_1") (pintype "passive"))
      (node (ref "Q6") (pin "1") (pinfunction "D_1") (pintype "passive"))
      (node (ref "Q6") (pin "2") (pinfunction "D_2") (pintype "passive"))
      (node (ref "Q6") (pin "5") (pinfunction "D_5") (pintype "passive"))
      (node (ref "Q6") (pin "6") (pinfunction "D_6") (pintype "passive"))
      (node (ref "R63") (pin "1") (pinfunction "1_1") (pintype "passive"))
      (node (ref "U14") (pin "16") (pinfunction "RS+_16") (pintype "passive"))
    )
    (net (code "245") (name "Net-(U15-PG)") (class "Default")
      (node (ref "TP48") (pin "1") (pinfunction "1_1") (pintype "passive"))
      (node (ref "U15") (pin "13") (pinfunction "PG_13") (pintype "open_collector"))
    )
    (net (code "246") (name "Net-(U15-SYNC)") (class "Default")
      (node (ref "R34") (pin "1") (pinfunction "1_1") (pintype "passive"))
      (node (ref "R40") (pin "2") (pinfunction "2_2") (pintype "passive"))
      (node (ref "TP46") (pin "1") (pinfunction "1_1") (pintype "passive"))
      (node (ref "U15") (pin "5") (pinfunction "SYNC_5") (pintype "input"))
    )
    (net (code "247") (name "Net-(U16-IO6)") (class "Default")
      (node (ref "TP53") (pin "1") (pinfunction "1_1") (pintype "passive"))
      (node (ref "U16") (pin "11") (pinfunction "IO6_11") (pintype "bidirectional"))
    )
    (net (code "248") (name "Net-(U16-IO7)") (class "Default")
      (node (ref "TP56") (pin "1") (pinfunction "1_1") (pintype "passive"))
      (node (ref "U16") (pin "12") (pinfunction "IO7_12") (pintype "bidirectional"))
    )
    (net (code "249") (name "Net-(U16-~{RESET})") (class "Default")
      (node (ref "R72") (pin "1") (pinfunction "1_1") (pintype "passive"))
      (node (ref "U16") (pin "13") (pinfunction "~{RESET}_13") (pintype "input"))
    )
    (net (code "250") (name "Net-(U17-MISO)") (class "Default")
      (node (ref "U17") (pin "2") (pinfunction "MISO_2") (pintype "output"))
      (node (ref "U7") (pin "B13") (pinfunction "SPI0_D0_B13") (pintype "bidirectional"))
    )
    (net (code "251") (name "Net-(U17-MOSI)") (class "Default")
      (node (ref "U17") (pin "5") (pinfunction "MOSI_5") (pintype "input"))
      (node (ref "U7") (pin "B14") (pinfunction "SPI0_D1_B14") (pintype "bidirectional"))
    )
    (net (code "252") (name "Net-(U17-SCK)") (class "Default")
      (node (ref "U17") (pin "6") (pinfunction "SCK_6") (pintype "input"))
      (node (ref "U7") (pin "A13") (pinfunction "SPI0_SCLK_A13") (pintype "bidirectional"))
    )
    (net (code "253") (name "Net-(U17-~{CS})") (class "Default")
      (node (ref "U17") (pin "1") (pinfunction "~{CS}_1") (pintype "input"))
      (node (ref "U7") (pin "A14") (pinfunction "SPI0_CS0_A14") (pintype "bidirectional"))
    )
    (net (code "254") (name "Net-(U17-~{WP})") (class "Default")
      (node (ref "R59") (pin "1") (pinfunction "1_1") (pintype "passive"))
      (node (ref "R60") (pin "2") (pinfunction "2_2") (pintype "passive"))
      (node (ref "U17") (pin "3") (pinfunction "~{WP}_3") (pintype "input"))
    )
    (net (code "255") (name "ON{slash}~{OFF}") (class "Default")
      (node (ref "C34") (pin "1") (pinfunction "1_1") (pintype "passive"))
      (node (ref "Q4") (pin "1") (pinfunction "G_1") (pintype "passive"))
      (node (ref "R46") (pin "2") (pinfunction "2_2") (pintype "passive"))
      (node (ref "R49") (pin "2") (pinfunction "2_2") (pintype "passive"))
      (node (ref "TP50") (pin "1") (pinfunction "1_1") (pintype "passive"))
      (node (ref "U14") (pin "1") (pinfunction "VCC_1") (pintype "power_in"))
      (node (ref "U16") (pin "8") (pinfunction "IO3_8") (pintype "bidirectional"))
    )
    (net (code "256") (name "OPD_PWR") (class "Default")
      (node (ref "J4") (pin "15") (pinfunction "15_15") (pintype "passive"))
      (node (ref "J4") (pin "16") (pinfunction "16_16") (pintype "passive"))
      (node (ref "R71") (pin "1") (pinfunction "1_1") (pintype "passive"))
    )
    (net (code "257") (name "OPD_SCL") (class "Default")
      (node (ref "J4") (pin "13") (pinfunction "13_13") (pintype "passive"))
      (node (ref "J4") (pin "14") (pinfunction "14_14") (pintype "passive"))
      (node (ref "R48") (pin "1") (pinfunction "1_1") (pintype "passive"))
    )
    (net (code "258") (name "OPD_SDA") (class "Default")
      (node (ref "J4") (pin "11") (pinfunction "11_11") (pintype "passive"))
      (node (ref "J4") (pin "12") (pinfunction "12_12") (pintype "passive"))
      (node (ref "R41") (pin "1") (pinfunction "1_1") (pintype "passive"))
    )
    (net (code "259") (name "OSC0_GND") (class "Default")
      (node (ref "C19") (pin "1") (pinfunction "1_1") (pintype "passive"))
      (node (ref "C22") (pin "1") (pinfunction "1_1") (pintype "passive"))
      (node (ref "U7") (pin "N15") (pinfunction "OSC0_GND_N15") (pintype "bidirectional"))
    )
    (net (code "260") (name "OSC0_IN") (class "Default")
      (node (ref "C19") (pin "2") (pinfunction "2_2") (pintype "passive"))
      (node (ref "R13") (pin "2") (pinfunction "2_2") (pintype "passive"))
      (node (ref "U7") (pin "P16") (pinfunction "OSC0_IN_P16") (pintype "bidirectional"))
      (node (ref "Y1") (pin "1") (pinfunction "X1_1") (pintype "passive"))
    )
    (net (code "261") (name "OSC0_OUT") (class "Default")
      (node (ref "C22") (pin "2") (pinfunction "2_2") (pintype "passive"))
      (node (ref "R13") (pin "1") (pinfunction "1_1") (pintype "passive"))
      (node (ref "U7") (pin "N16") (pinfunction "OSC0_OUT_N16") (pintype "bidirectional"))
      (node (ref "Y1") (pin "3") (pinfunction "X2_3") (pintype "passive"))
    )
    (net (code "262") (name "PB6{slash}SCL") (class "Default")
      (node (ref "TP67") (pin "1") (pinfunction "1_1") (pintype "passive"))
      (node (ref "U16") (pin "4") (pinfunction "IO0_4") (pintype "bidirectional"))
    )
    (net (code "263") (name "PB7{slash}SDA") (class "Default")
      (node (ref "TP68") (pin "1") (pinfunction "1_1") (pintype "passive"))
      (node (ref "U16") (pin "5") (pinfunction "IO1_5") (pintype "bidirectional"))
    )
    (net (code "264") (name "PEN-SCL-FILT") (class "Default")
      (node (ref "Q3") (pin "6") (pinfunction "D_6") (pintype "passive"))
      (node (ref "R37") (pin "2") (pinfunction "2_2") (pintype "passive"))
      (node (ref "R65") (pin "1") (pinfunction "1_1") (pintype "passive"))
      (node (ref "R67") (pin "1") (pinfunction "1_1") (pintype "passive"))
      (node (ref "R69") (pin "1") (pinfunction "1_1") (pintype "passive"))
      (node (ref "TP42") (pin "1") (pinfunction "1_1") (pintype "passive"))
      (node (ref "TP66") (pin "1") (pinfunction "1_1") (pintype "passive"))
      (node (ref "U16") (pin "15") (pinfunction "SCL_15") (pintype "input"))
    )
    (net (code "265") (name "PEN-SDA-FILT") (class "Default")
      (node (ref "Q3") (pin "4") (pinfunction "D_4") (pintype "passive"))
      (node (ref "R45") (pin "2") (pinfunction "2_2") (pintype "passive"))
      (node (ref "R66") (pin "2") (pinfunction "2_2") (pintype "passive"))
      (node (ref "R68") (pin "2") (pinfunction "2_2") (pintype "passive"))
      (node (ref "R70") (pin "2") (pinfunction "2_2") (pintype "passive"))
      (node (ref "TP41") (pin "1") (pinfunction "1_1") (pintype "passive"))
      (node (ref "TP65") (pin "1") (pinfunction "1_1") (pintype "passive"))
      (node (ref "U16") (pin "16") (pinfunction "SDA_16") (pintype "bidirectional"))
    )
    (net (code "266") (name "PIXCLK_E") (class "Default")
      (node (ref "J101") (pin "5") (pinfunction "5_5") (pintype "passive"))
      (node (ref "U6") (pin "20") (pinfunction "2B6_20") (pintype "bidirectional"))
    )
    (net (code "267") (name "PIXCLK_I") (class "Default")
      (node (ref "TP28") (pin "P$1") (pinfunction "1_P$1") (pintype "bidirectional"))
      (node (ref "U6") (pin "29") (pinfunction "2A6_29") (pintype "bidirectional"))
      (node (ref "U7") (pin "B4") (pinfunction "XDMA_EVENT_INTR1_B4") (pintype "bidirectional"))
    )
    (net (code "268") (name "PMIC_PGOOD") (class "Default")
      (node (ref "TP110") (pin "P$1") (pinfunction "1_P$1") (pintype "bidirectional"))
      (node (ref "U4") (pin "2") (pinfunction "A_2") (pintype "bidirectional"))
      (node (ref "U7") (pin "N12") (pinfunction "PMIC_PGOOD_N12") (pintype "output"))
      (node (ref "U7") (pin "P11") (pinfunction "PWRONRSTN_P11") (pintype "bidirectional"))
    )
    (net (code "269") (name "POUT") (class "Default")
      (node (ref "TP64") (pin "1") (pinfunction "1_1") (pintype "passive"))
      (node (ref "U14") (pin "13") (pinfunction "POUT_13") (pintype "output"))
    )
    (net (code "270") (name "RESET") (class "Default")
      (node (ref "TP10") (pin "P$1") (pinfunction "1_P$1") (pintype "bidirectional"))
      (node (ref "U5") (pin "19") (pinfunction "B3_19") (pintype "bidirectional"))
      (node (ref "U7") (pin "D16") (pinfunction "MII1_RXD1_D16") (pintype "bidirectional"))
    )
    (net (code "271") (name "RESET#") (class "Default")
      (node (ref "JP1") (pin "1") (pinfunction "1_1") (pintype "passive"))
      (node (ref "TP109") (pin "P$1") (pinfunction "1_P$1") (pintype "bidirectional"))
      (node (ref "U4") (pin "4") (pinfunction "Y_4") (pintype "bidirectional"))
      (node (ref "U7") (pin "R11") (pinfunction "WARMRSTN_R11") (pintype "bidirectional"))
    )
    (net (code "272") (name "SADDR") (class "Default")
      (node (ref "TP7") (pin "P$1") (pinfunction "1_P$1") (pintype "bidirectional"))
      (node (ref "U5") (pin "16") (pinfunction "B6_16") (pintype "bidirectional"))
      (node (ref "U7") (pin "D15") (pinfunction "MII1_RXD2_D15") (pintype "bidirectional"))
    )
    (net (code "273") (name "SADDR_E") (class "Default")
      (node (ref "J101") (pin "27") (pinfunction "27_27") (pintype "passive"))
      (node (ref "U5") (pin "8") (pinfunction "A6_8") (pintype "bidirectional"))
    )
    (net (code "274") (name "SCL_2") (class "Default")
      (node (ref "R30") (pin "2") (pinfunction "2_2") (pintype "passive"))
      (node (ref "TP37") (pin "P$1") (pinfunction "1_P$1") (pintype "bidirectional"))
      (node (ref "U7") (pin "A10") (pinfunction "UART1_RTSN_A10") (pintype "bidirectional"))
      (node (ref "U9") (pin "2") (pinfunction "SCLA_2") (pintype "bidirectional"))
    )
    (net (code "275") (name "SDA_2") (class "Default")
      (node (ref "R29") (pin "2") (pinfunction "2_2") (pintype "passive"))
      (node (ref "TP36") (pin "P$1") (pinfunction "1_P$1") (pintype "bidirectional"))
      (node (ref "U7") (pin "B10") (pinfunction "UART1_CTSN_B10") (pintype "bidirectional"))
      (node (ref "U9") (pin "3") (pinfunction "SDAA_3") (pintype "bidirectional"))
    )
    (net (code "276") (name "SPARE1") (class "Default")
      (node (ref "J4") (pin "10") (pinfunction "10_10") (pintype "passive"))
      (node (ref "J4") (pin "9") (pinfunction "9_9") (pintype "passive"))
      (node (ref "TP58") (pin "P$1") (pinfunction "1_P$1") (pintype "bidirectional"))
    )
    (net (code "277") (name "SPARE2") (class "Default")
      (node (ref "J4") (pin "7") (pinfunction "7_7") (pintype "passive"))
      (node (ref "J4") (pin "8") (pinfunction "8_8") (pintype "passive"))
      (node (ref "TP59") (pin "P$1") (pinfunction "1_P$1") (pintype "bidirectional"))
    )
    (net (code "278") (name "SPARE3") (class "Default")
      (node (ref "J4") (pin "5") (pinfunction "5_5") (pintype "passive"))
      (node (ref "J4") (pin "6") (pinfunction "6_6") (pintype "passive"))
      (node (ref "TP60") (pin "P$1") (pinfunction "1_P$1") (pintype "bidirectional"))
    )
    (net (code "279") (name "SPARE4") (class "Default")
      (node (ref "J4") (pin "3") (pinfunction "3_3") (pintype "passive"))
      (node (ref "J4") (pin "4") (pinfunction "4_4") (pintype "passive"))
      (node (ref "TP61") (pin "P$1") (pinfunction "1_P$1") (pintype "bidirectional"))
    )
    (net (code "280") (name "STANDBY") (class "Default")
      (node (ref "TP9") (pin "P$1") (pinfunction "1_P$1") (pintype "bidirectional"))
      (node (ref "U5") (pin "18") (pinfunction "B4_18") (pintype "bidirectional"))
      (node (ref "U7") (pin "D14") (pinfunction "MII1_RXD3_D14") (pintype "bidirectional"))
    )
    (net (code "281") (name "STANDBY_E") (class "Default")
      (node (ref "J101") (pin "25") (pinfunction "25_25") (pintype "passive"))
      (node (ref "U5") (pin "6") (pinfunction "A4_6") (pintype "bidirectional"))
    )
    (net (code "282") (name "TRIGGER") (class "Default")
      (node (ref "TP6") (pin "P$1") (pinfunction "1_P$1") (pintype "bidirectional"))
      (node (ref "U5") (pin "15") (pinfunction "B7_15") (pintype "bidirectional"))
      (node (ref "U7") (pin "E15") (pinfunction "MII1_RX_ER_E15") (pintype "bidirectional"))
    )
    (net (code "283") (name "TRIGGER_E") (class "Default")
      (node (ref "J101") (pin "29") (pinfunction "29_29") (pintype "passive"))
      (node (ref "U5") (pin "9") (pinfunction "A7_9") (pintype "bidirectional"))
    )
    (net (code "284") (name "UART0_RX") (class "Default")
      (node (ref "J1") (pin "12") (pinfunction "CARD-RX_12") (pintype "passive"))
      (node (ref "TP146") (pin "P$1") (pinfunction "1_P$1") (pintype "bidirectional"))
      (node (ref "U7") (pin "A12") (pinfunction "UART0_RXD_A12") (pintype "bidirectional"))
    )
    (net (code "285") (name "UART0_TX") (class "Default")
      (node (ref "J1") (pin "13") (pinfunction "CARD-TX_13") (pintype "passive"))
      (node (ref "TP142") (pin "P$1") (pinfunction "1_P$1") (pintype "bidirectional"))
      (node (ref "U7") (pin "B12") (pinfunction "UART0_TXD_B12") (pintype "bidirectional"))
    )
    (net (code "286") (name "USB_CLI_N") (class "Default")
      (node (ref "J1") (pin "5") (pinfunction "DEVICE-D-_5") (pintype "passive"))
      (node (ref "U1") (pin "1") (pinfunction "I1_1") (pintype "bidirectional"))
      (node (ref "U7") (pin "K16") (pinfunction "USB0_DM_K16") (pintype "bidirectional"))
    )
    (net (code "287") (name "USB_CLI_P") (class "Default")
      (node (ref "J1") (pin "4") (pinfunction "DEVICE-D+_4") (pintype "passive"))
      (node (ref "U1") (pin "3") (pinfunction "I2_3") (pintype "bidirectional"))
      (node (ref "U7") (pin "K15") (pinfunction "USB0_DP_K15") (pintype "bidirectional"))
    )
    (net (code "288") (name "USB_CLI_VBUS") (class "Default")
      (node (ref "FB2") (pin "1") (pinfunction "1_1") (pintype "passive"))
      (node (ref "J1") (pin "1") (pinfunction "VBUSP_1") (pintype "passive"))
      (node (ref "J1") (pin "2") (pinfunction "VBUSP_2") (pintype "passive"))
    )
    (net (code "289") (name "USB_HO_N") (class "Default")
      (node (ref "J1") (pin "8") (pinfunction "HOST-D-_8") (pintype "passive"))
      (node (ref "U1") (pin "6") (pinfunction "I4_6") (pintype "bidirectional"))
      (node (ref "U7") (pin "L16") (pinfunction "USB1_DM_L16") (pintype "bidirectional"))
    )
    (net (code "290") (name "USB_HO_PX") (class "Default")
      (node (ref "J1") (pin "7") (pinfunction "HOST-D+_7") (pintype "passive"))
      (node (ref "U1") (pin "4") (pinfunction "I3_4") (pintype "bidirectional"))
      (node (ref "U7") (pin "L15") (pinfunction "USB1_DP_L15") (pintype "bidirectional"))
    )
    (net (code "291") (name "USB_HO_VBUS") (class "Default")
      (node (ref "FB1") (pin "2") (pinfunction "2_2") (pintype "passive"))
      (node (ref "J1") (pin "17") (pinfunction "DEBUG-0_17") (pintype "passive"))
    )
    (net (code "292") (name "VBUS") (class "Default")
      (node (ref "J4") (pin "21") (pinfunction "21_21") (pintype "passive"))
      (node (ref "J4") (pin "22") (pinfunction "22_22") (pintype "passive"))
      (node (ref "J4") (pin "23") (pinfunction "23_23") (pintype "passive"))
      (node (ref "J4") (pin "24") (pinfunction "24_24") (pintype "passive"))
      (node (ref "J4") (pin "25") (pinfunction "25_25") (pintype "passive"))
      (node (ref "J4") (pin "26") (pinfunction "26_26") (pintype "passive"))
      (node (ref "Q6") (pin "4") (pinfunction "S_4") (pintype "passive"))
      (node (ref "R52") (pin "2") (pinfunction "2_2") (pintype "passive"))
    )
    (net (code "293") (name "VBUSP") (class "Default")
      (node (ref "C33") (pin "2") (pinfunction "2_2") (pintype "passive"))
      (node (ref "C37") (pin "1") (pinfunction "1_1") (pintype "passive"))
      (node (ref "C38") (pin "1") (pinfunction "1_1") (pintype "passive"))
      (node (ref "Q5") (pin "1") (pinfunction "D_1") (pintype "passive"))
      (node (ref "Q5") (pin "2") (pinfunction "D_2") (pintype "passive"))
      (node (ref "Q5") (pin "5") (pinfunction "D_5") (pintype "passive"))
      (node (ref "Q5") (pin "6") (pinfunction "D_6") (pintype "passive"))
      (node (ref "R34") (pin "2") (pinfunction "2_2") (pintype "passive"))
      (node (ref "R61") (pin "2") (pinfunction "2_2") (pintype "passive"))
      (node (ref "TP55") (pin "1") (pinfunction "1_1") (pintype "passive"))
      (node (ref "U15") (pin "2") (pinfunction "VIN_2") (pintype "power_in"))
      (node (ref "U15") (pin "3") (pinfunction "VIN_3") (pintype "power_in"))
      (node (ref "U15") (pin "4") (pinfunction "EN_4") (pintype "input"))
      (node (ref "U15") (pin "8") (pinfunction "VIN_8") (pintype "power_in"))
    )
    (net (code "294") (name "VDD") (class "Default")
      (node (ref "C15") (pin "1") (pinfunction "1_1") (pintype "passive"))
      (node (ref "C7") (pin "1") (pinfunction "1_1") (pintype "passive"))
      (node (ref "R7") (pin "2") (pinfunction "2_2") (pintype "passive"))
      (node (ref "TP3") (pin "P$1") (pinfunction "1_P$1") (pintype "bidirectional"))
      (node (ref "U2") (pin "5") (pinfunction "IN_5") (pintype "input"))
      (node (ref "U7") (pin "K6") (pinfunction "SYS_VOUT_K6") (pintype "power_in"))
      (node (ref "U7") (pin "K7") (pinfunction "SYS_VOUT_K7") (pintype "power_in"))
      (node (ref "U7") (pin "L6") (pinfunction "SYS_VOUT_L6") (pintype "power_in"))
      (node (ref "U7") (pin "L7") (pinfunction "SYS_VOUT_L7") (pintype "power_in"))
    )
    (net (code "295") (name "VIN_USB") (class "Default")
      (node (ref "C13") (pin "1") (pinfunction "1_1") (pintype "passive"))
      (node (ref "C4") (pin "1") (pinfunction "1_1") (pintype "passive"))
      (node (ref "FB2") (pin "2") (pinfunction "2_2") (pintype "passive"))
      (node (ref "TP2") (pin "P$1") (pinfunction "1_P$1") (pintype "bidirectional"))
      (node (ref "U1") (pin "5") (pinfunction "VCC_5") (pintype "power_in"))
      (node (ref "U7") (pin "J16") (pinfunction "USB0_VBUS_J16") (pintype "bidirectional"))
      (node (ref "U7") (pin "P9") (pinfunction "VIN_USB_P9") (pintype "power_in"))
      (node (ref "U7") (pin "R9") (pinfunction "VIN_USB_R9") (pintype "power_in"))
      (node (ref "U7") (pin "T9") (pinfunction "VIN_USB_T9") (pintype "power_in"))
    )
    (net (code "296") (name "VOUT_USB") (class "Default")
      (node (ref "C1") (pin "1") (pinfunction "1_1") (pintype "passive"))
      (node (ref "FB1") (pin "1") (pinfunction "1_1") (pintype "passive"))
      (node (ref "TP1") (pin "P$1") (pinfunction "1_P$1") (pintype "bidirectional"))
      (node (ref "U2") (pin "1") (pinfunction "OUT_1") (pintype "output"))
      (node (ref "U7") (pin "M15") (pinfunction "USB1_VBUS_M15") (pintype "bidirectional"))
    )
    (net (code "297") (name "VPD") (class "Default")
      (node (ref "C39") (pin "2") (pinfunction "2_2") (pintype "passive"))
      (node (ref "R32") (pin "2") (pinfunction "2_2") (pintype "passive"))
      (node (ref "R36") (pin "2") (pinfunction "2_2") (pintype "passive"))
      (node (ref "R44") (pin "2") (pinfunction "2_2") (pintype "passive"))
      (node (ref "R53") (pin "2") (pinfunction "2_2") (pintype "passive"))
      (node (ref "R55") (pin "2") (pinfunction "2_2") (pintype "passive"))
      (node (ref "R57") (pin "2") (pinfunction "2_2") (pintype "passive"))
      (node (ref "R71") (pin "2") (pinfunction "2_2") (pintype "passive"))
      (node (ref "R72") (pin "2") (pinfunction "2_2") (pintype "passive"))
      (node (ref "TP63") (pin "1") (pinfunction "1_1") (pintype "passive"))
      (node (ref "U12") (pin "5") (pinfunction "VDD_5") (pintype "power_in"))
      (node (ref "U13") (pin "5") (pinfunction "VDD_5") (pintype "power_in"))
      (node (ref "U16") (pin "14") (pinfunction "V+_14") (pintype "power_in"))
    )
    (net (code "298") (name "VREG_EN") (class "Default")
      (node (ref "TP5") (pin "P$1") (pinfunction "1_P$1") (pintype "bidirectional"))
      (node (ref "U5") (pin "14") (pinfunction "B8_14") (pintype "bidirectional"))
      (node (ref "U7") (pin "F16") (pinfunction "MII1_RX_DV_F16") (pintype "bidirectional"))
    )
    (net (code "299") (name "VREG_EN_E") (class "Default")
      (node (ref "J101") (pin "30") (pinfunction "30_30") (pintype "passive"))
      (node (ref "U5") (pin "10") (pinfunction "A8_10") (pintype "bidirectional"))
    )
    (net (code "300") (name "VSYNC_E") (class "Default")
      (node (ref "J101") (pin "3") (pinfunction "3_3") (pintype "passive"))
      (node (ref "U6") (pin "23") (pinfunction "2B8_23") (pintype "bidirectional"))
    )
    (net (code "301") (name "VSYNC_I") (class "Default")
      (node (ref "TP116") (pin "P$1") (pinfunction "1_P$1") (pintype "bidirectional"))
      (node (ref "U6") (pin "26") (pinfunction "2A8_26") (pintype "bidirectional"))
      (node (ref "U7") (pin "T6") (pinfunction "GPMC_AD14_T6") (pintype "bidirectional"))
    )
    (net (code "302") (name "unconnected-(J1-NRST-Pad10)") (class "Default")
      (node (ref "J1") (pin "10") (pinfunction "NRST_10") (pintype "passive"))
    )
    (net (code "303") (name "unconnected-(J1-SWCLK-Pad15)") (class "Default")
      (node (ref "J1") (pin "15") (pinfunction "SWCLK_15") (pintype "passive"))
    )
    (net (code "304") (name "unconnected-(J1-SWDIO-Pad14)") (class "Default")
      (node (ref "J1") (pin "14") (pinfunction "SWDIO_14") (pintype "passive"))
    )
    (net (code "305") (name "unconnected-(J1-SWO-Pad16)") (class "Default")
      (node (ref "J1") (pin "16") (pinfunction "SWO_16") (pintype "passive"))
    )
    (net (code "306") (name "unconnected-(J1-VTARGET-Pad11)") (class "Default")
      (node (ref "J1") (pin "11") (pinfunction "VTARGET_11") (pintype "passive"))
    )
    (net (code "307") (name "unconnected-(R8-11-Pad1)") (class "Default")
      (node (ref "R8") (pin "1") (pinfunction "11_1") (pintype "passive"))
    )
    (net (code "308") (name "unconnected-(R9-11-Pad1)") (class "Default")
      (node (ref "R9") (pin "1") (pinfunction "11_1") (pintype "passive"))
    )
    (net (code "309") (name "unconnected-(R9-99-Pad9)") (class "Default")
      (node (ref "R9") (pin "9") (pinfunction "99_9") (pintype "passive"))
    )
    (net (code "310") (name "unconnected-(R10-44-Pad4)") (class "Default")
      (node (ref "R10") (pin "4") (pinfunction "44_4") (pintype "passive"))
    )
    (net (code "311") (name "unconnected-(R10-66-Pad6)") (class "Default")
      (node (ref "R10") (pin "6") (pinfunction "66_6") (pintype "passive"))
    )
    (net (code "312") (name "unconnected-(R10-77-Pad7)") (class "Default")
      (node (ref "R10") (pin "7") (pinfunction "77_7") (pintype "passive"))
    )
    (net (code "313") (name "unconnected-(R24-11-Pad1)") (class "Default")
      (node (ref "R24") (pin "1") (pinfunction "11_1") (pintype "passive"))
    )
    (net (code "314") (name "unconnected-(R24-77-Pad7)") (class "Default")
      (node (ref "R24") (pin "7") (pinfunction "77_7") (pintype "passive"))
    )
    (net (code "315") (name "unconnected-(R25-88-Pad8)") (class "Default")
      (node (ref "R25") (pin "8") (pinfunction "88_8") (pintype "passive"))
    )
    (net (code "316") (name "unconnected-(U5-A1-Pad3)") (class "Default")
      (node (ref "U5") (pin "3") (pinfunction "A1_3") (pintype "bidirectional"))
    )
    (net (code "317") (name "unconnected-(U5-B1-Pad21)") (class "Default")
      (node (ref "U5") (pin "21") (pinfunction "B1_21") (pintype "bidirectional"))
    )
    (net (code "318") (name "unconnected-(U18-I3-Pad4)") (class "Default")
      (node (ref "U18") (pin "4") (pinfunction "I3_4") (pintype "bidirectional"))
    )
    (net (code "319") (name "~{FAULT}") (class "Default")
      (node (ref "Q2") (pin "3") (pinfunction "D_3") (pintype "passive"))
      (node (ref "R32") (pin "1") (pinfunction "1_1") (pintype "passive"))
      (node (ref "TP45") (pin "1") (pinfunction "1_1") (pintype "passive"))
      (node (ref "U16") (pin "7") (pinfunction "IO2_7") (pintype "bidirectional"))
    )
    (net (code "320") (name "~{OE_E}") (class "Default")
      (node (ref "J101") (pin "26") (pinfunction "26_26") (pintype "passive"))
      (node (ref "U5") (pin "7") (pinfunction "A5_7") (pintype "bidirectional"))
    )
    (net (code "321") (name "~{RESET_E}") (class "Default")
      (node (ref "J101") (pin "24") (pinfunction "24_24") (pintype "passive"))
      (node (ref "U5") (pin "5") (pinfunction "A3_5") (pintype "bidirectional"))
    )
    (net (code "322") (name "~{SD}") (class "Default")
      (node (ref "J4") (pin "39") (pinfunction "39_39") (pintype "passive"))
      (node (ref "J4") (pin "40") (pinfunction "40_40") (pintype "passive"))
    )
  )
)
